# SE423_F28379D.net
KiCad netlist of a schematic drawn in EAGLE
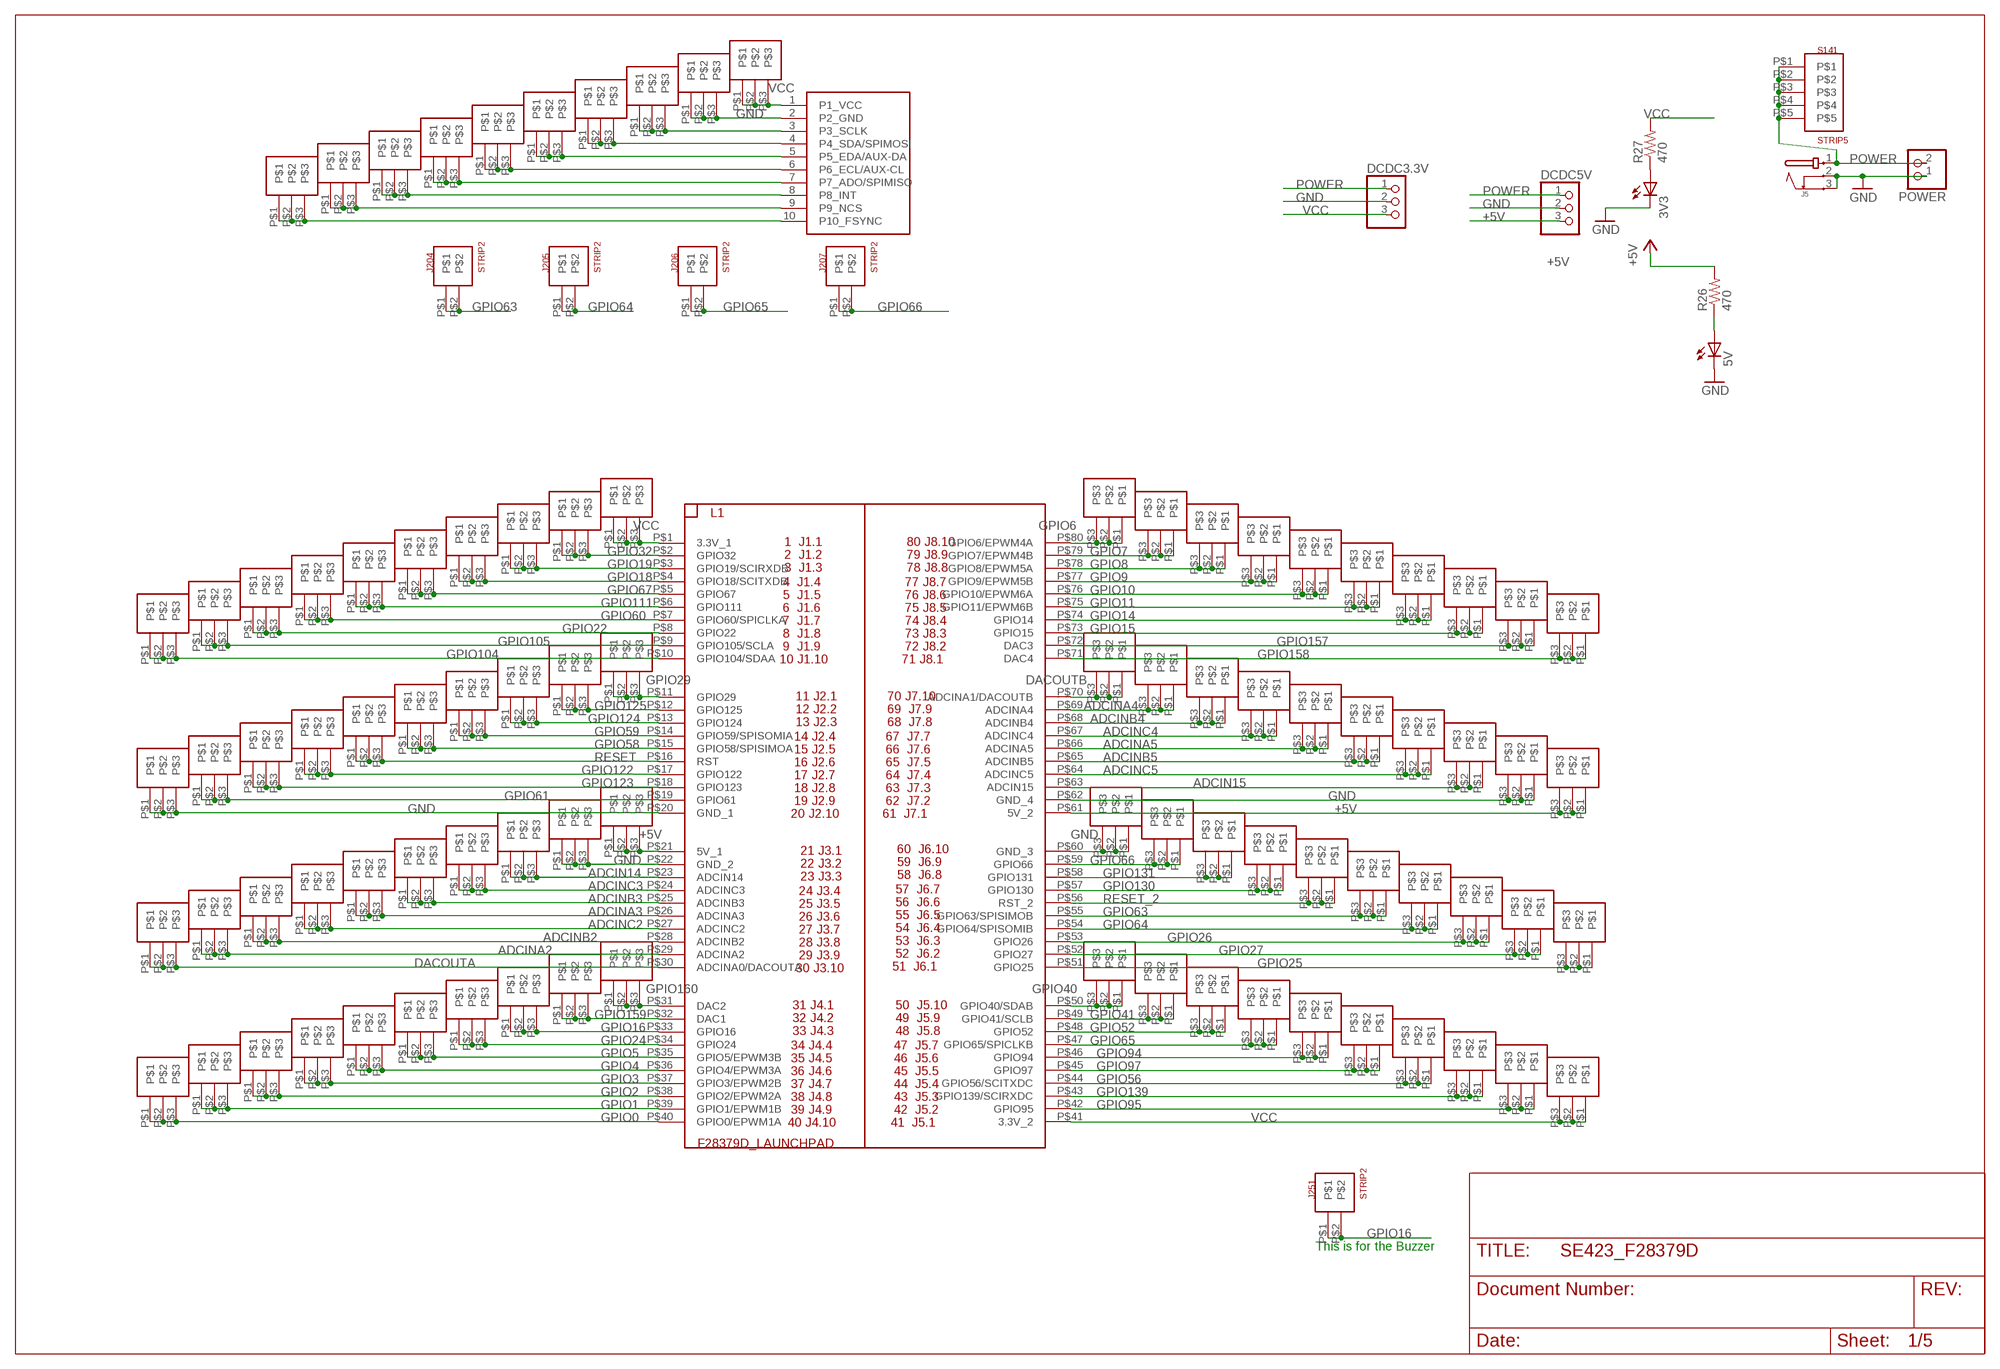
[diagram p0: schematic, sheet 1]
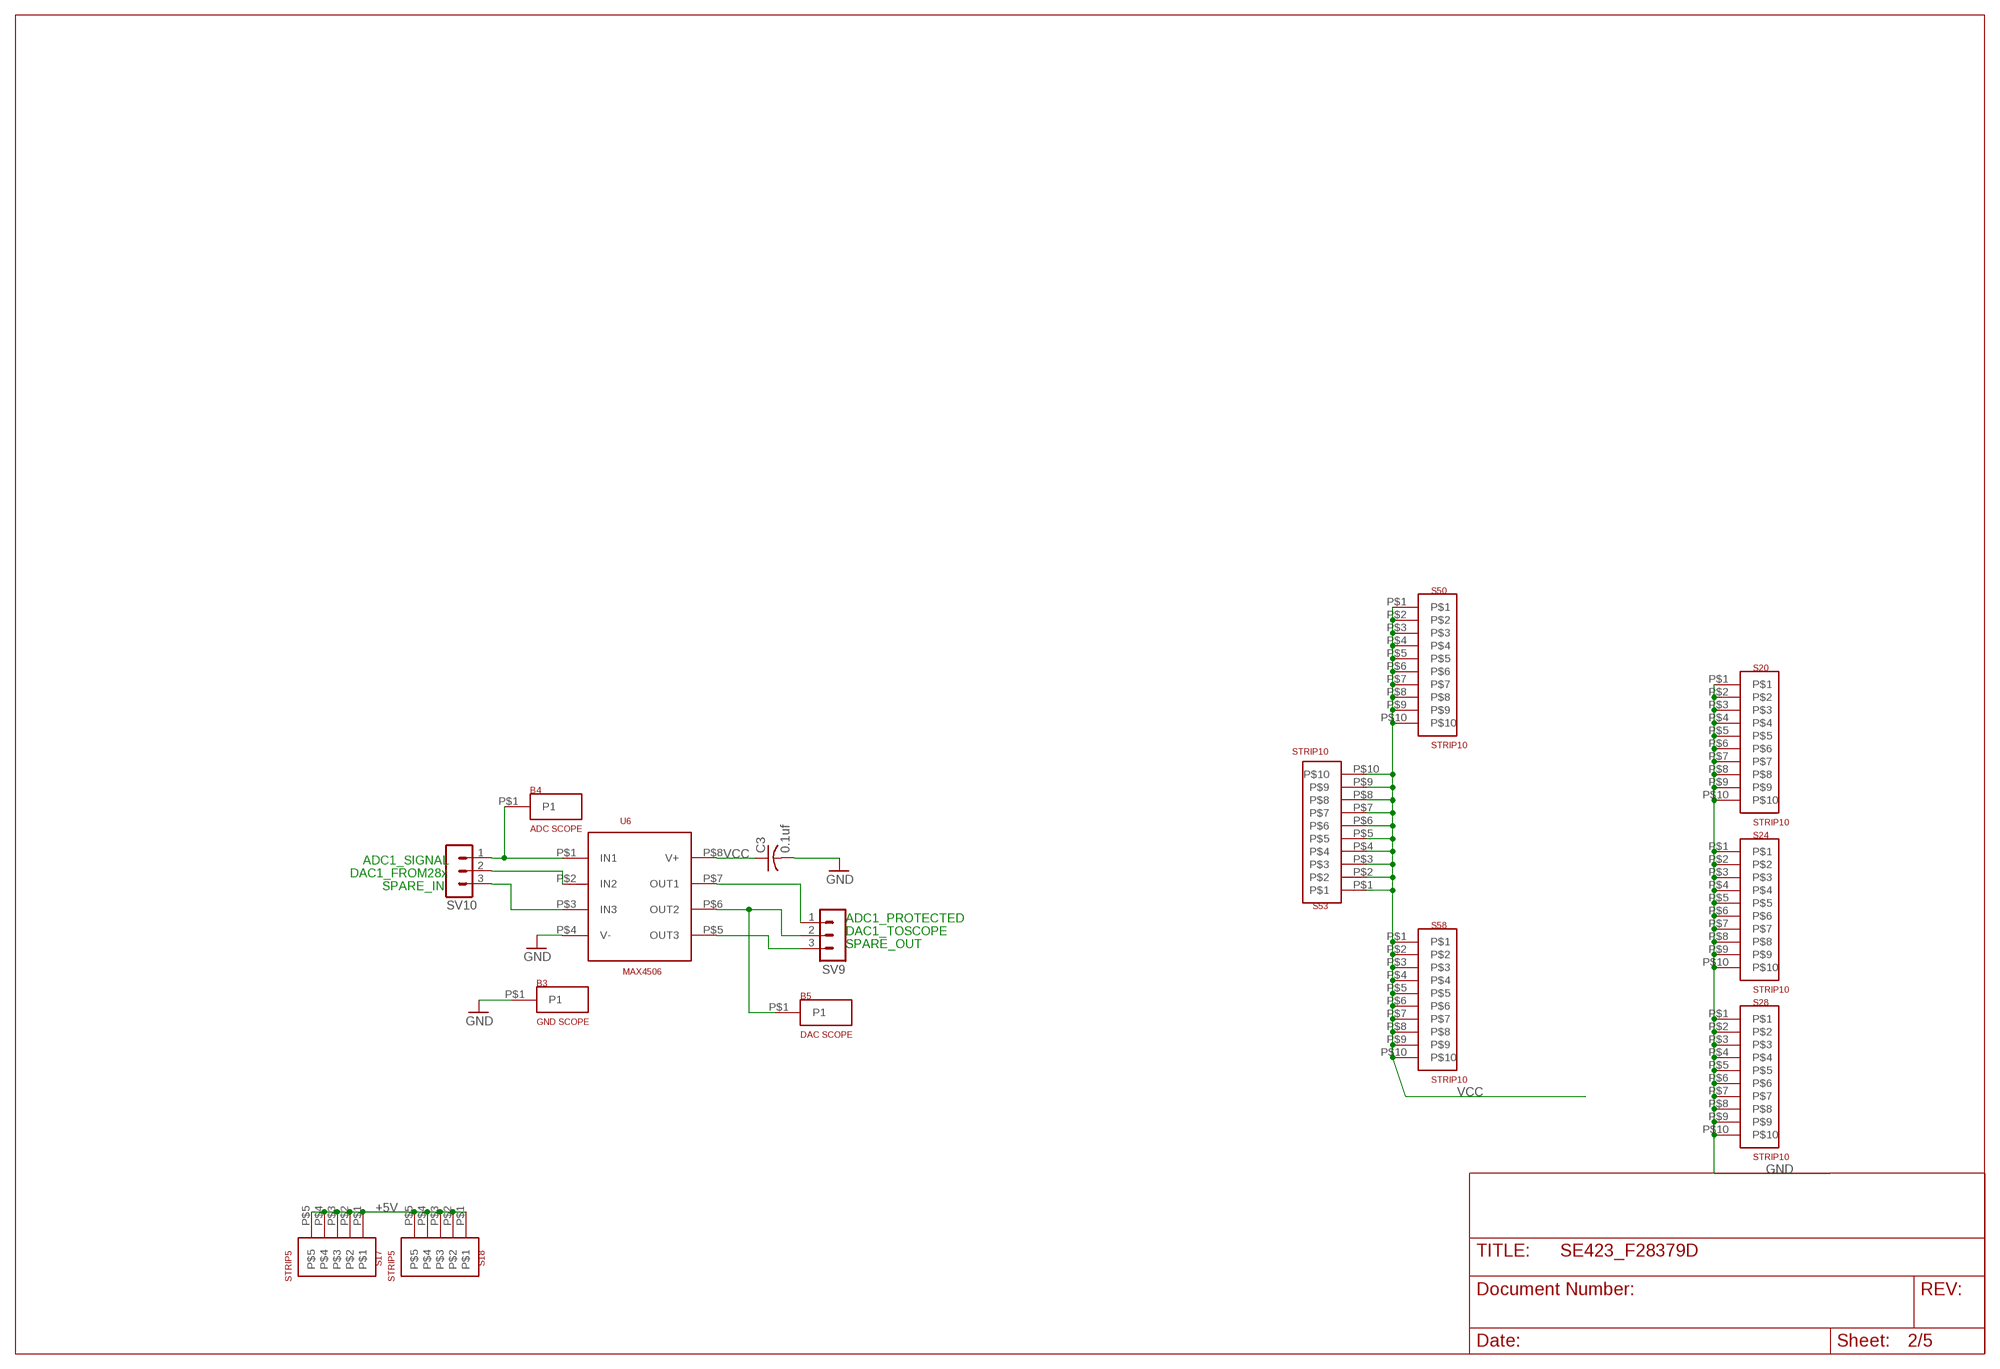
[diagram p1: schematic, sheet 2]
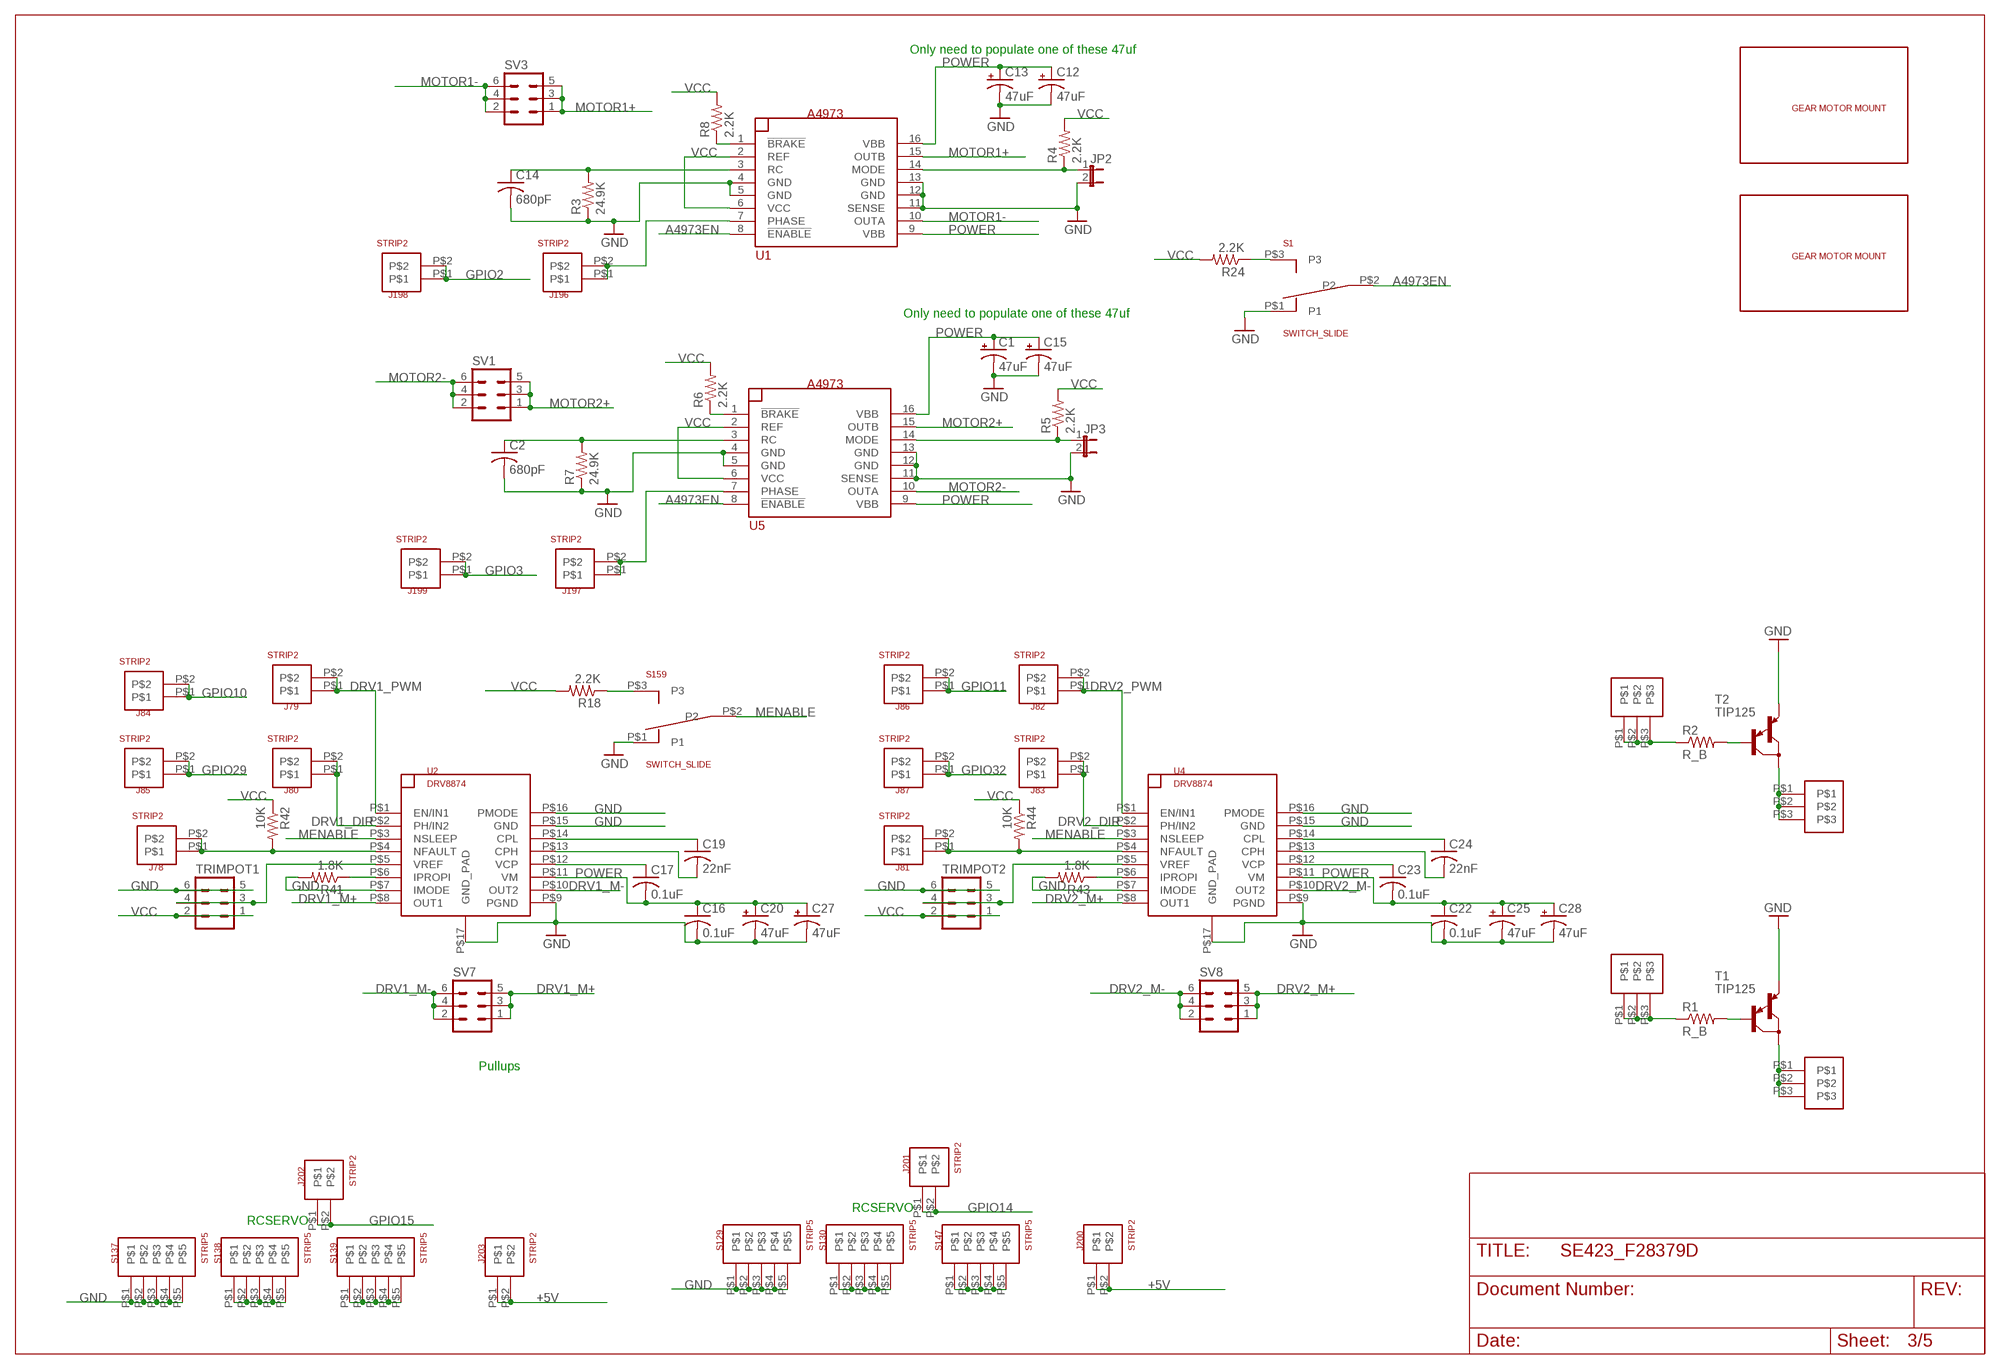
[diagram p2: schematic, sheet 3]
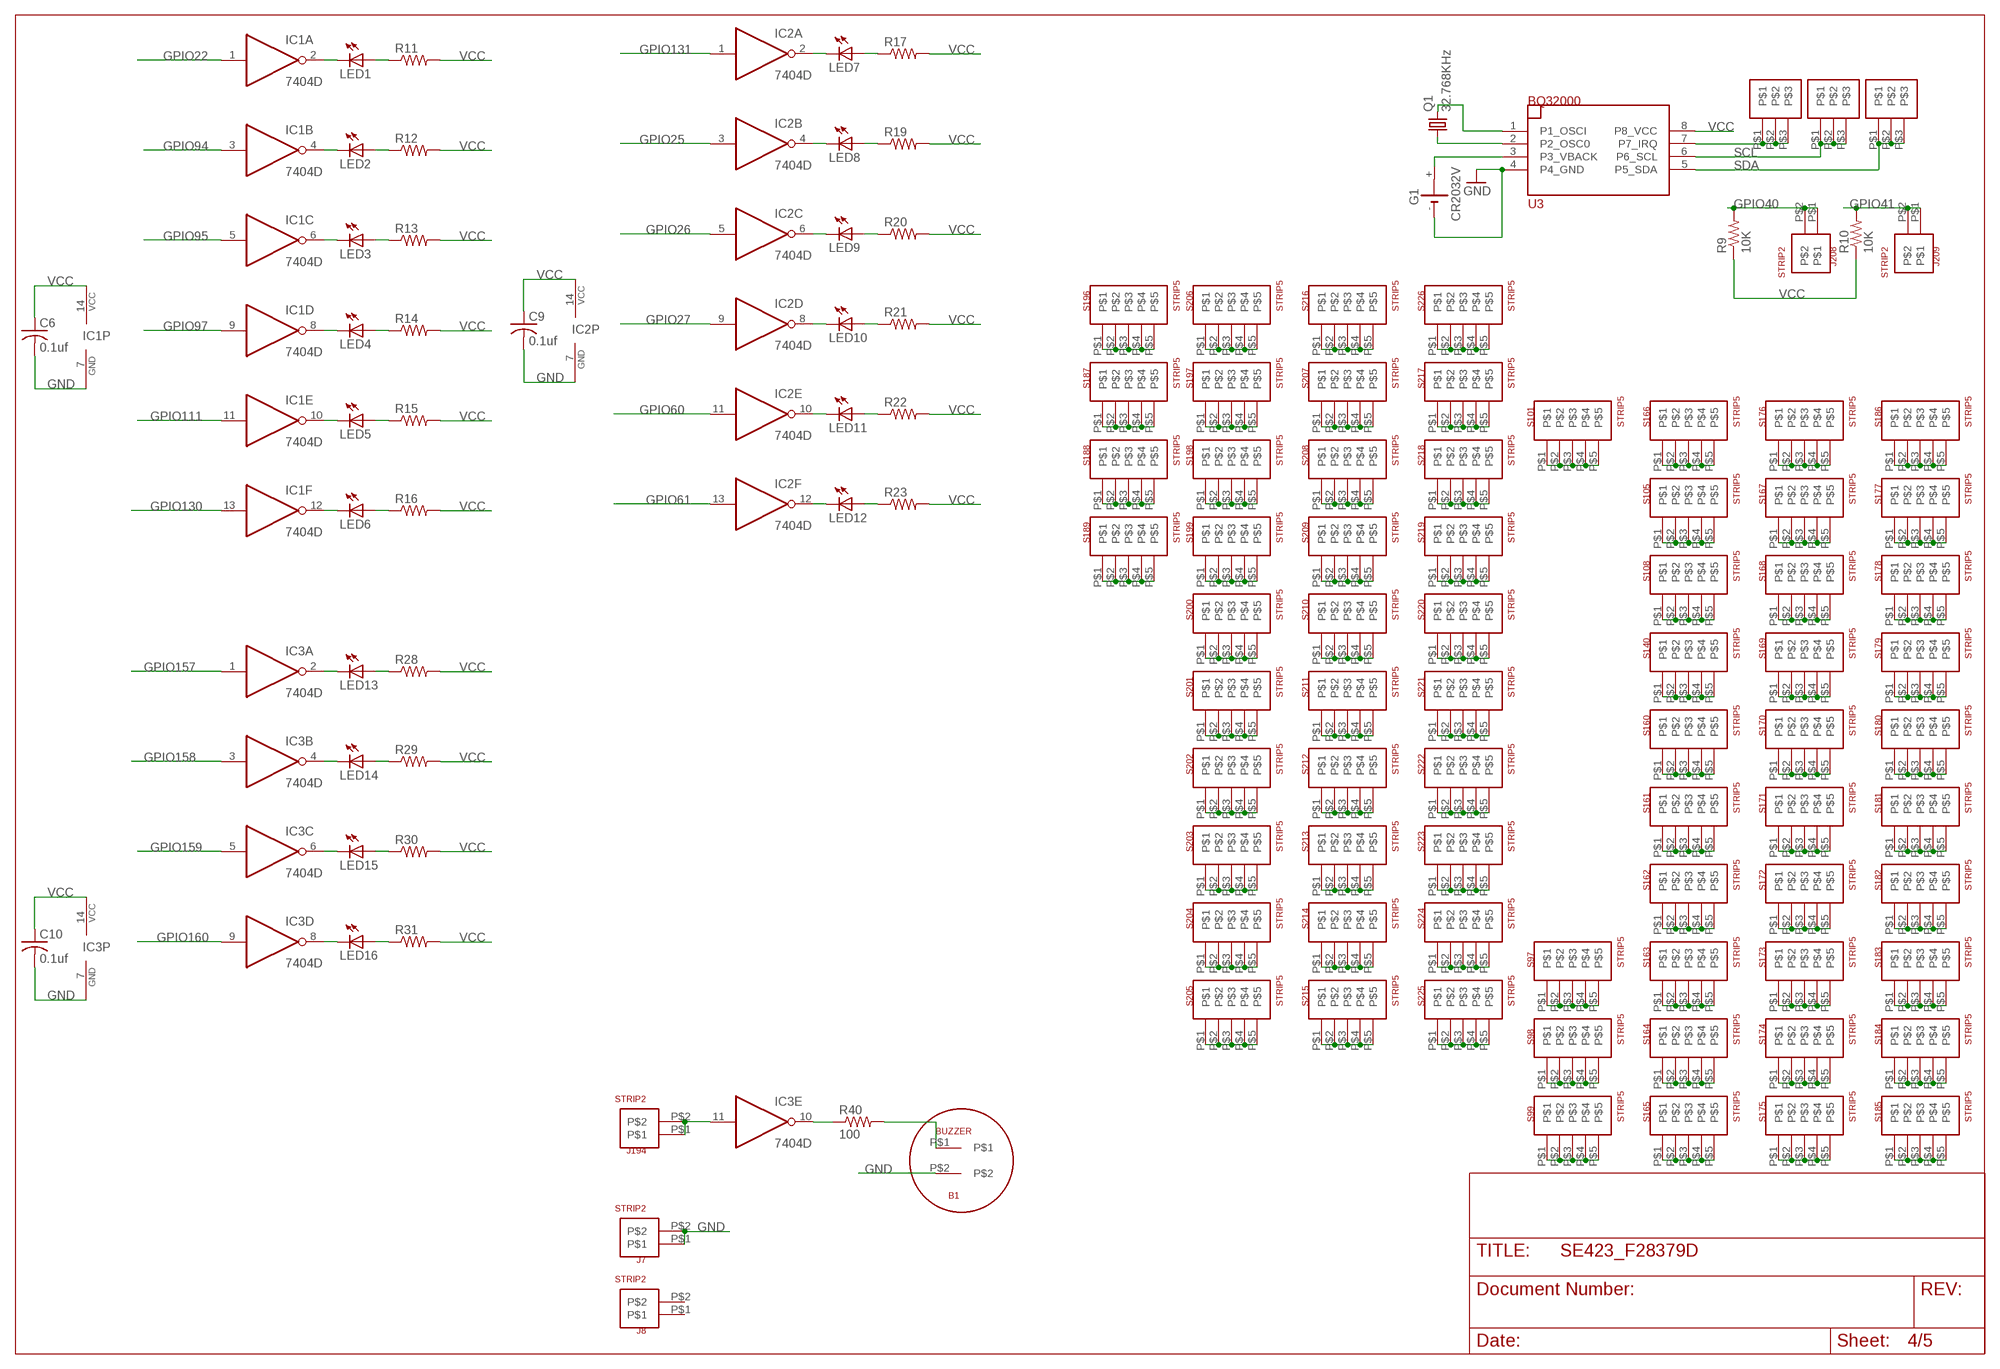
[diagram p3: schematic, sheet 4]
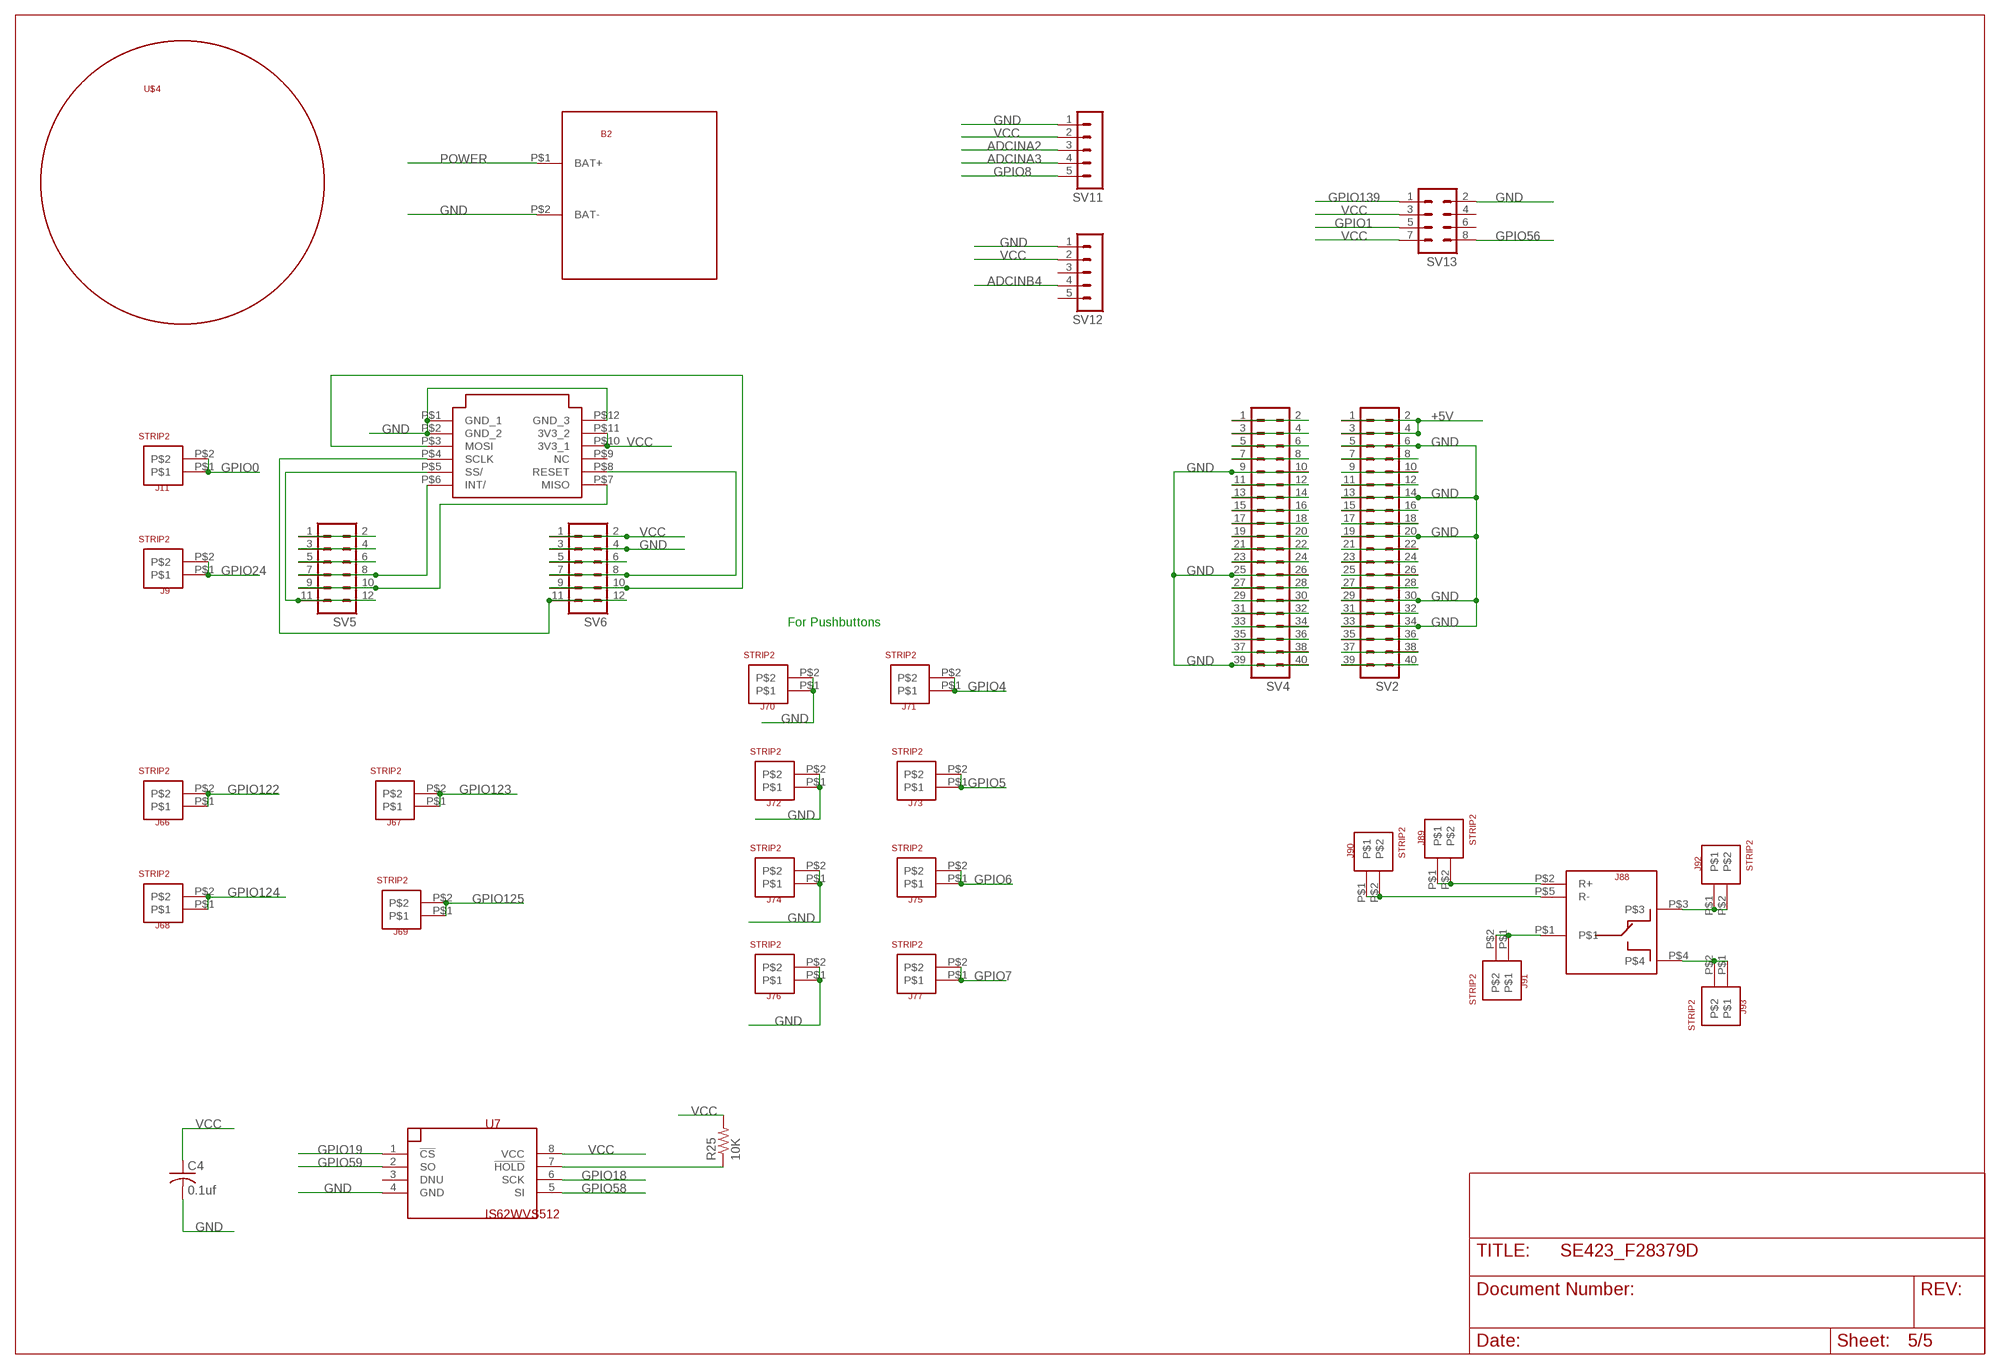
[diagram p4: schematic, sheet 5]

(export (version "E")
  (design (tool "Eeschema 10.0.6"))
  (components
    (comp (ref "B3")
      (value "GND SCOPE")
      (footprint "eagle-import:BANANA_MALE")
      (libsource (lib "eagle-import") (part "BANANA_MALE"))
    )
    (comp (ref "B4")
      (value "ADC SCOPE")
      (footprint "eagle-import:BANANA_MALE")
      (libsource (lib "eagle-import") (part "BANANA_MALE"))
    )
    (comp (ref "B5")
      (value "DAC SCOPE")
      (footprint "eagle-import:BANANA_MALE")
      (libsource (lib "eagle-import") (part "BANANA_MALE"))
    )
    (comp (ref "C3")
      (value "0.1uf")
      (footprint "eagle-import:C1206")
      (libsource (lib "eagle-import") (part "C-USC1206"))
    )
    (comp (ref "S17")
      (value "STRIP5")
      (footprint "eagle-import:STRIP5")
      (libsource (lib "eagle-import") (part "STRIP5"))
    )
    (comp (ref "S18")
      (value "STRIP5")
      (footprint "eagle-import:STRIP5")
      (libsource (lib "eagle-import") (part "STRIP5"))
    )
    (comp (ref "S20")
      (value "STRIP10")
      (footprint "eagle-import:STRIP10")
      (libsource (lib "eagle-import") (part "STRIP10"))
    )
    (comp (ref "S24")
      (value "STRIP10")
      (footprint "eagle-import:STRIP10")
      (libsource (lib "eagle-import") (part "STRIP10"))
    )
    (comp (ref "S28")
      (value "STRIP10")
      (footprint "eagle-import:STRIP10")
      (libsource (lib "eagle-import") (part "STRIP10"))
    )
    (comp (ref "S50")
      (value "STRIP10")
      (footprint "eagle-import:STRIP10")
      (libsource (lib "eagle-import") (part "STRIP10"))
    )
    (comp (ref "S53")
      (value "STRIP10")
      (footprint "eagle-import:STRIP10")
      (libsource (lib "eagle-import") (part "STRIP10"))
    )
    (comp (ref "S58")
      (value "STRIP10")
      (footprint "eagle-import:STRIP10")
      (libsource (lib "eagle-import") (part "STRIP10"))
    )
    (comp (ref "SV9")
      (value "MA03-1")
      (footprint "eagle-import:MA03-1")
      (libsource (lib "eagle-import") (part "MA03-1"))
    )
    (comp (ref "SV10")
      (value "MA03-1")
      (footprint "eagle-import:MA03-1")
      (libsource (lib "eagle-import") (part "MA03-1"))
    )
    (comp (ref "U6")
      (value "MAX4506")
      (footprint "eagle-import:SOIC-8")
      (libsource (lib "eagle-import") (part "MAX4506-SOIC8"))
    )
    (comp (ref "B1")
      (value "BUZZER")
      (footprint "eagle-import:BUZZER")
      (libsource (lib "eagle-import") (part "BUZZER"))
    )
    (comp (ref "C6")
      (value "0.1uf")
      (footprint "eagle-import:C1206")
      (libsource (lib "eagle-import") (part "C-USC1206"))
    )
    (comp (ref "C9")
      (value "0.1uf")
      (footprint "eagle-import:C1206")
      (libsource (lib "eagle-import") (part "C-USC1206"))
    )
    (comp (ref "C10")
      (value "0.1uf")
      (footprint "eagle-import:C1206")
      (libsource (lib "eagle-import") (part "C-USC1206"))
    )
    (comp (ref "G1")
      (value "CR2032V")
      (footprint "eagle-import:CR2032V")
      (libsource (lib "eagle-import") (part "CR2032V"))
    )
    (comp (ref "IC1")
      (value "7404D")
      (footprint "eagle-import:SO14")
      (libsource (lib "eagle-import") (part "7404D"))
    )
    (comp (ref "IC2")
      (value "7404D")
      (footprint "eagle-import:SO14")
      (libsource (lib "eagle-import") (part "7404D"))
    )
    (comp (ref "IC3")
      (value "7404D")
      (footprint "eagle-import:SO14")
      (libsource (lib "eagle-import") (part "7404D"))
    )
    (comp (ref "J1")
      (value "STRIP3")
      (footprint "eagle-import:STRIP3")
      (libsource (lib "eagle-import") (part "STRIP3"))
    )
    (comp (ref "J2")
      (value "STRIP3")
      (footprint "eagle-import:STRIP3")
      (libsource (lib "eagle-import") (part "STRIP3"))
    )
    (comp (ref "J3")
      (value "STRIP3")
      (footprint "eagle-import:STRIP3")
      (libsource (lib "eagle-import") (part "STRIP3"))
    )
    (comp (ref "J7")
      (value "STRIP2")
      (footprint "eagle-import:STRIP2")
      (libsource (lib "eagle-import") (part "STRIP2"))
    )
    (comp (ref "J8")
      (value "STRIP2")
      (footprint "eagle-import:STRIP2")
      (libsource (lib "eagle-import") (part "STRIP2"))
    )
    (comp (ref "J194")
      (value "STRIP2")
      (footprint "eagle-import:STRIP2")
      (libsource (lib "eagle-import") (part "STRIP2"))
    )
    (comp (ref "J208")
      (value "STRIP2")
      (footprint "eagle-import:STRIP2")
      (libsource (lib "eagle-import") (part "STRIP2"))
    )
    (comp (ref "J209")
      (value "STRIP2")
      (footprint "eagle-import:STRIP2")
      (libsource (lib "eagle-import") (part "STRIP2"))
    )
    (comp (ref "LED1")
      (value "LEDCHIPLED_1206")
      (footprint "eagle-import:CHIPLED_1206")
      (libsource (lib "eagle-import") (part "LEDCHIPLED_1206"))
    )
    (comp (ref "LED2")
      (value "LEDCHIPLED_1206")
      (footprint "eagle-import:CHIPLED_1206")
      (libsource (lib "eagle-import") (part "LEDCHIPLED_1206"))
    )
    (comp (ref "LED3")
      (value "LEDCHIPLED_1206")
      (footprint "eagle-import:CHIPLED_1206")
      (libsource (lib "eagle-import") (part "LEDCHIPLED_1206"))
    )
    (comp (ref "LED4")
      (value "LEDCHIPLED_1206")
      (footprint "eagle-import:CHIPLED_1206")
      (libsource (lib "eagle-import") (part "LEDCHIPLED_1206"))
    )
    (comp (ref "LED5")
      (value "LEDCHIPLED_1206")
      (footprint "eagle-import:CHIPLED_1206")
      (libsource (lib "eagle-import") (part "LEDCHIPLED_1206"))
    )
    (comp (ref "LED6")
      (value "LEDCHIPLED_1206")
      (footprint "eagle-import:CHIPLED_1206")
      (libsource (lib "eagle-import") (part "LEDCHIPLED_1206"))
    )
    (comp (ref "LED7")
      (value "LEDCHIPLED_1206")
      (footprint "eagle-import:CHIPLED_1206")
      (libsource (lib "eagle-import") (part "LEDCHIPLED_1206"))
    )
    (comp (ref "LED8")
      (value "LEDCHIPLED_1206")
      (footprint "eagle-import:CHIPLED_1206")
      (libsource (lib "eagle-import") (part "LEDCHIPLED_1206"))
    )
    (comp (ref "LED9")
      (value "LEDCHIPLED_1206")
      (footprint "eagle-import:CHIPLED_1206")
      (libsource (lib "eagle-import") (part "LEDCHIPLED_1206"))
    )
    (comp (ref "LED10")
      (value "LEDCHIPLED_1206")
      (footprint "eagle-import:CHIPLED_1206")
      (libsource (lib "eagle-import") (part "LEDCHIPLED_1206"))
    )
    (comp (ref "LED11")
      (value "LEDCHIPLED_1206")
      (footprint "eagle-import:CHIPLED_1206")
      (libsource (lib "eagle-import") (part "LEDCHIPLED_1206"))
    )
    (comp (ref "LED12")
      (value "LEDCHIPLED_1206")
      (footprint "eagle-import:CHIPLED_1206")
      (libsource (lib "eagle-import") (part "LEDCHIPLED_1206"))
    )
    (comp (ref "LED13")
      (value "LEDCHIPLED_1206")
      (footprint "eagle-import:CHIPLED_1206")
      (libsource (lib "eagle-import") (part "LEDCHIPLED_1206"))
    )
    (comp (ref "LED14")
      (value "LEDCHIPLED_1206")
      (footprint "eagle-import:CHIPLED_1206")
      (libsource (lib "eagle-import") (part "LEDCHIPLED_1206"))
    )
    (comp (ref "LED15")
      (value "LEDCHIPLED_1206")
      (footprint "eagle-import:CHIPLED_1206")
      (libsource (lib "eagle-import") (part "LEDCHIPLED_1206"))
    )
    (comp (ref "LED16")
      (value "LEDCHIPLED_1206")
      (footprint "eagle-import:CHIPLED_1206")
      (libsource (lib "eagle-import") (part "LEDCHIPLED_1206"))
    )
    (comp (ref "Q1")
      (value "32.768KHz")
      (footprint "eagle-import:TC26H")
      (libsource (lib "eagle-import") (part "CRYTALTC26H"))
    )
    (comp (ref "R9")
      (value "10K")
      (footprint "eagle-import:R1206")
      (libsource (lib "eagle-import") (part "R-US_R1206"))
    )
    (comp (ref "R10")
      (value "10K")
      (footprint "eagle-import:R1206")
      (libsource (lib "eagle-import") (part "R-US_R1206"))
    )
    (comp (ref "R11")
      (value "R-US_R1206")
      (footprint "eagle-import:R1206")
      (libsource (lib "eagle-import") (part "R-US_R1206"))
    )
    (comp (ref "R12")
      (value "R-US_R1206")
      (footprint "eagle-import:R1206")
      (libsource (lib "eagle-import") (part "R-US_R1206"))
    )
    (comp (ref "R13")
      (value "R-US_R1206")
      (footprint "eagle-import:R1206")
      (libsource (lib "eagle-import") (part "R-US_R1206"))
    )
    (comp (ref "R14")
      (value "R-US_R1206")
      (footprint "eagle-import:R1206")
      (libsource (lib "eagle-import") (part "R-US_R1206"))
    )
    (comp (ref "R15")
      (value "R-US_R1206")
      (footprint "eagle-import:R1206")
      (libsource (lib "eagle-import") (part "R-US_R1206"))
    )
    (comp (ref "R16")
      (value "R-US_R1206")
      (footprint "eagle-import:R1206")
      (libsource (lib "eagle-import") (part "R-US_R1206"))
    )
    (comp (ref "R17")
      (value "R-US_R1206")
      (footprint "eagle-import:R1206")
      (libsource (lib "eagle-import") (part "R-US_R1206"))
    )
    (comp (ref "R19")
      (value "R-US_R1206")
      (footprint "eagle-import:R1206")
      (libsource (lib "eagle-import") (part "R-US_R1206"))
    )
    (comp (ref "R20")
      (value "R-US_R1206")
      (footprint "eagle-import:R1206")
      (libsource (lib "eagle-import") (part "R-US_R1206"))
    )
    (comp (ref "R21")
      (value "R-US_R1206")
      (footprint "eagle-import:R1206")
      (libsource (lib "eagle-import") (part "R-US_R1206"))
    )
    (comp (ref "R22")
      (value "R-US_R1206")
      (footprint "eagle-import:R1206")
      (libsource (lib "eagle-import") (part "R-US_R1206"))
    )
    (comp (ref "R23")
      (value "R-US_R1206")
      (footprint "eagle-import:R1206")
      (libsource (lib "eagle-import") (part "R-US_R1206"))
    )
    (comp (ref "R28")
      (value "R-US_R1206")
      (footprint "eagle-import:R1206")
      (libsource (lib "eagle-import") (part "R-US_R1206"))
    )
    (comp (ref "R29")
      (value "R-US_R1206")
      (footprint "eagle-import:R1206")
      (libsource (lib "eagle-import") (part "R-US_R1206"))
    )
    (comp (ref "R30")
      (value "R-US_R1206")
      (footprint "eagle-import:R1206")
      (libsource (lib "eagle-import") (part "R-US_R1206"))
    )
    (comp (ref "R31")
      (value "R-US_R1206")
      (footprint "eagle-import:R1206")
      (libsource (lib "eagle-import") (part "R-US_R1206"))
    )
    (comp (ref "R40")
      (value "100")
      (footprint "eagle-import:R1206")
      (libsource (lib "eagle-import") (part "R-US_R1206"))
    )
    (comp (ref "S97")
      (value "STRIP5")
      (footprint "eagle-import:STRIP5")
      (libsource (lib "eagle-import") (part "STRIP5"))
    )
    (comp (ref "S98")
      (value "STRIP5")
      (footprint "eagle-import:STRIP5")
      (libsource (lib "eagle-import") (part "STRIP5"))
    )
    (comp (ref "S99")
      (value "STRIP5")
      (footprint "eagle-import:STRIP5")
      (libsource (lib "eagle-import") (part "STRIP5"))
    )
    (comp (ref "S101")
      (value "STRIP5")
      (footprint "eagle-import:STRIP5")
      (libsource (lib "eagle-import") (part "STRIP5"))
    )
    (comp (ref "S105")
      (value "STRIP5")
      (footprint "eagle-import:STRIP5")
      (libsource (lib "eagle-import") (part "STRIP5"))
    )
    (comp (ref "S108")
      (value "STRIP5")
      (footprint "eagle-import:STRIP5")
      (libsource (lib "eagle-import") (part "STRIP5"))
    )
    (comp (ref "S140")
      (value "STRIP5")
      (footprint "eagle-import:STRIP5")
      (libsource (lib "eagle-import") (part "STRIP5"))
    )
    (comp (ref "S160")
      (value "STRIP5")
      (footprint "eagle-import:STRIP5")
      (libsource (lib "eagle-import") (part "STRIP5"))
    )
    (comp (ref "S161")
      (value "STRIP5")
      (footprint "eagle-import:STRIP5")
      (libsource (lib "eagle-import") (part "STRIP5"))
    )
    (comp (ref "S162")
      (value "STRIP5")
      (footprint "eagle-import:STRIP5")
      (libsource (lib "eagle-import") (part "STRIP5"))
    )
    (comp (ref "S163")
      (value "STRIP5")
      (footprint "eagle-import:STRIP5")
      (libsource (lib "eagle-import") (part "STRIP5"))
    )
    (comp (ref "S164")
      (value "STRIP5")
      (footprint "eagle-import:STRIP5")
      (libsource (lib "eagle-import") (part "STRIP5"))
    )
    (comp (ref "S165")
      (value "STRIP5")
      (footprint "eagle-import:STRIP5")
      (libsource (lib "eagle-import") (part "STRIP5"))
    )
    (comp (ref "S166")
      (value "STRIP5")
      (footprint "eagle-import:STRIP5")
      (libsource (lib "eagle-import") (part "STRIP5"))
    )
    (comp (ref "S167")
      (value "STRIP5")
      (footprint "eagle-import:STRIP5")
      (libsource (lib "eagle-import") (part "STRIP5"))
    )
    (comp (ref "S168")
      (value "STRIP5")
      (footprint "eagle-import:STRIP5")
      (libsource (lib "eagle-import") (part "STRIP5"))
    )
    (comp (ref "S169")
      (value "STRIP5")
      (footprint "eagle-import:STRIP5")
      (libsource (lib "eagle-import") (part "STRIP5"))
    )
    (comp (ref "S170")
      (value "STRIP5")
      (footprint "eagle-import:STRIP5")
      (libsource (lib "eagle-import") (part "STRIP5"))
    )
    (comp (ref "S171")
      (value "STRIP5")
      (footprint "eagle-import:STRIP5")
      (libsource (lib "eagle-import") (part "STRIP5"))
    )
    (comp (ref "S172")
      (value "STRIP5")
      (footprint "eagle-import:STRIP5")
      (libsource (lib "eagle-import") (part "STRIP5"))
    )
    (comp (ref "S173")
      (value "STRIP5")
      (footprint "eagle-import:STRIP5")
      (libsource (lib "eagle-import") (part "STRIP5"))
    )
    (comp (ref "S174")
      (value "STRIP5")
      (footprint "eagle-import:STRIP5")
      (libsource (lib "eagle-import") (part "STRIP5"))
    )
    (comp (ref "S175")
      (value "STRIP5")
      (footprint "eagle-import:STRIP5")
      (libsource (lib "eagle-import") (part "STRIP5"))
    )
    (comp (ref "S176")
      (value "STRIP5")
      (footprint "eagle-import:STRIP5")
      (libsource (lib "eagle-import") (part "STRIP5"))
    )
    (comp (ref "S177")
      (value "STRIP5")
      (footprint "eagle-import:STRIP5")
      (libsource (lib "eagle-import") (part "STRIP5"))
    )
    (comp (ref "S178")
      (value "STRIP5")
      (footprint "eagle-import:STRIP5")
      (libsource (lib "eagle-import") (part "STRIP5"))
    )
    (comp (ref "S179")
      (value "STRIP5")
      (footprint "eagle-import:STRIP5")
      (libsource (lib "eagle-import") (part "STRIP5"))
    )
    (comp (ref "S180")
      (value "STRIP5")
      (footprint "eagle-import:STRIP5")
      (libsource (lib "eagle-import") (part "STRIP5"))
    )
    (comp (ref "S181")
      (value "STRIP5")
      (footprint "eagle-import:STRIP5")
      (libsource (lib "eagle-import") (part "STRIP5"))
    )
    (comp (ref "S182")
      (value "STRIP5")
      (footprint "eagle-import:STRIP5")
      (libsource (lib "eagle-import") (part "STRIP5"))
    )
    (comp (ref "S183")
      (value "STRIP5")
      (footprint "eagle-import:STRIP5")
      (libsource (lib "eagle-import") (part "STRIP5"))
    )
    (comp (ref "S184")
      (value "STRIP5")
      (footprint "eagle-import:STRIP5")
      (libsource (lib "eagle-import") (part "STRIP5"))
    )
    (comp (ref "S185")
      (value "STRIP5")
      (footprint "eagle-import:STRIP5")
      (libsource (lib "eagle-import") (part "STRIP5"))
    )
    (comp (ref "S186")
      (value "STRIP5")
      (footprint "eagle-import:STRIP5")
      (libsource (lib "eagle-import") (part "STRIP5"))
    )
    (comp (ref "S187")
      (value "STRIP5")
      (footprint "eagle-import:STRIP5")
      (libsource (lib "eagle-import") (part "STRIP5"))
    )
    (comp (ref "S188")
      (value "STRIP5")
      (footprint "eagle-import:STRIP5")
      (libsource (lib "eagle-import") (part "STRIP5"))
    )
    (comp (ref "S189")
      (value "STRIP5")
      (footprint "eagle-import:STRIP5")
      (libsource (lib "eagle-import") (part "STRIP5"))
    )
    (comp (ref "S196")
      (value "STRIP5")
      (footprint "eagle-import:STRIP5")
      (libsource (lib "eagle-import") (part "STRIP5"))
    )
    (comp (ref "S197")
      (value "STRIP5")
      (footprint "eagle-import:STRIP5")
      (libsource (lib "eagle-import") (part "STRIP5"))
    )
    (comp (ref "S198")
      (value "STRIP5")
      (footprint "eagle-import:STRIP5")
      (libsource (lib "eagle-import") (part "STRIP5"))
    )
    (comp (ref "S199")
      (value "STRIP5")
      (footprint "eagle-import:STRIP5")
      (libsource (lib "eagle-import") (part "STRIP5"))
    )
    (comp (ref "S200")
      (value "STRIP5")
      (footprint "eagle-import:STRIP5")
      (libsource (lib "eagle-import") (part "STRIP5"))
    )
    (comp (ref "S201")
      (value "STRIP5")
      (footprint "eagle-import:STRIP5")
      (libsource (lib "eagle-import") (part "STRIP5"))
    )
    (comp (ref "S202")
      (value "STRIP5")
      (footprint "eagle-import:STRIP5")
      (libsource (lib "eagle-import") (part "STRIP5"))
    )
    (comp (ref "S203")
      (value "STRIP5")
      (footprint "eagle-import:STRIP5")
      (libsource (lib "eagle-import") (part "STRIP5"))
    )
    (comp (ref "S204")
      (value "STRIP5")
      (footprint "eagle-import:STRIP5")
      (libsource (lib "eagle-import") (part "STRIP5"))
    )
    (comp (ref "S205")
      (value "STRIP5")
      (footprint "eagle-import:STRIP5")
      (libsource (lib "eagle-import") (part "STRIP5"))
    )
    (comp (ref "S206")
      (value "STRIP5")
      (footprint "eagle-import:STRIP5")
      (libsource (lib "eagle-import") (part "STRIP5"))
    )
    (comp (ref "S207")
      (value "STRIP5")
      (footprint "eagle-import:STRIP5")
      (libsource (lib "eagle-import") (part "STRIP5"))
    )
    (comp (ref "S208")
      (value "STRIP5")
      (footprint "eagle-import:STRIP5")
      (libsource (lib "eagle-import") (part "STRIP5"))
    )
    (comp (ref "S209")
      (value "STRIP5")
      (footprint "eagle-import:STRIP5")
      (libsource (lib "eagle-import") (part "STRIP5"))
    )
    (comp (ref "S210")
      (value "STRIP5")
      (footprint "eagle-import:STRIP5")
      (libsource (lib "eagle-import") (part "STRIP5"))
    )
    (comp (ref "S211")
      (value "STRIP5")
      (footprint "eagle-import:STRIP5")
      (libsource (lib "eagle-import") (part "STRIP5"))
    )
    (comp (ref "S212")
      (value "STRIP5")
      (footprint "eagle-import:STRIP5")
      (libsource (lib "eagle-import") (part "STRIP5"))
    )
    (comp (ref "S213")
      (value "STRIP5")
      (footprint "eagle-import:STRIP5")
      (libsource (lib "eagle-import") (part "STRIP5"))
    )
    (comp (ref "S214")
      (value "STRIP5")
      (footprint "eagle-import:STRIP5")
      (libsource (lib "eagle-import") (part "STRIP5"))
    )
    (comp (ref "S215")
      (value "STRIP5")
      (footprint "eagle-import:STRIP5")
      (libsource (lib "eagle-import") (part "STRIP5"))
    )
    (comp (ref "S216")
      (value "STRIP5")
      (footprint "eagle-import:STRIP5")
      (libsource (lib "eagle-import") (part "STRIP5"))
    )
    (comp (ref "S217")
      (value "STRIP5")
      (footprint "eagle-import:STRIP5")
      (libsource (lib "eagle-import") (part "STRIP5"))
    )
    (comp (ref "S218")
      (value "STRIP5")
      (footprint "eagle-import:STRIP5")
      (libsource (lib "eagle-import") (part "STRIP5"))
    )
    (comp (ref "S219")
      (value "STRIP5")
      (footprint "eagle-import:STRIP5")
      (libsource (lib "eagle-import") (part "STRIP5"))
    )
    (comp (ref "S220")
      (value "STRIP5")
      (footprint "eagle-import:STRIP5")
      (libsource (lib "eagle-import") (part "STRIP5"))
    )
    (comp (ref "S221")
      (value "STRIP5")
      (footprint "eagle-import:STRIP5")
      (libsource (lib "eagle-import") (part "STRIP5"))
    )
    (comp (ref "S222")
      (value "STRIP5")
      (footprint "eagle-import:STRIP5")
      (libsource (lib "eagle-import") (part "STRIP5"))
    )
    (comp (ref "S223")
      (value "STRIP5")
      (footprint "eagle-import:STRIP5")
      (libsource (lib "eagle-import") (part "STRIP5"))
    )
    (comp (ref "S224")
      (value "STRIP5")
      (footprint "eagle-import:STRIP5")
      (libsource (lib "eagle-import") (part "STRIP5"))
    )
    (comp (ref "S225")
      (value "STRIP5")
      (footprint "eagle-import:STRIP5")
      (libsource (lib "eagle-import") (part "STRIP5"))
    )
    (comp (ref "S226")
      (value "STRIP5")
      (footprint "eagle-import:STRIP5")
      (libsource (lib "eagle-import") (part "STRIP5"))
    )
    (comp (ref "U3")
      (value "BQ32000")
      (footprint "eagle-import:SO08")
      (libsource (lib "eagle-import") (part "BQ32000"))
    )
    (comp (ref "B2")
      (value "BATTERY_4AA_HOLDER")
      (footprint "eagle-import:BATTERY_4AA_HOLDER")
      (libsource (lib "eagle-import") (part "BATTERY_4AA_HOLDER"))
    )
    (comp (ref "C4")
      (value "0.1uf")
      (footprint "eagle-import:C1206")
      (libsource (lib "eagle-import") (part "C-USC1206"))
    )
    (comp (ref "ETH1")
      (value "USR_ES1_W5500")
      (footprint "eagle-import:USR_ES1_W5500")
      (libsource (lib "eagle-import") (part "USR_ES1_W5500"))
    )
    (comp (ref "J9")
      (value "STRIP2")
      (footprint "eagle-import:STRIP2")
      (libsource (lib "eagle-import") (part "STRIP2"))
    )
    (comp (ref "J11")
      (value "STRIP2")
      (footprint "eagle-import:STRIP2")
      (libsource (lib "eagle-import") (part "STRIP2"))
    )
    (comp (ref "J66")
      (value "STRIP2")
      (footprint "eagle-import:STRIP2")
      (libsource (lib "eagle-import") (part "STRIP2"))
    )
    (comp (ref "J67")
      (value "STRIP2")
      (footprint "eagle-import:STRIP2")
      (libsource (lib "eagle-import") (part "STRIP2"))
    )
    (comp (ref "J68")
      (value "STRIP2")
      (footprint "eagle-import:STRIP2")
      (libsource (lib "eagle-import") (part "STRIP2"))
    )
    (comp (ref "J69")
      (value "STRIP2")
      (footprint "eagle-import:STRIP2")
      (libsource (lib "eagle-import") (part "STRIP2"))
    )
    (comp (ref "J70")
      (value "STRIP2")
      (footprint "eagle-import:STRIP2")
      (libsource (lib "eagle-import") (part "STRIP2"))
    )
    (comp (ref "J71")
      (value "STRIP2")
      (footprint "eagle-import:STRIP2")
      (libsource (lib "eagle-import") (part "STRIP2"))
    )
    (comp (ref "J72")
      (value "STRIP2")
      (footprint "eagle-import:STRIP2")
      (libsource (lib "eagle-import") (part "STRIP2"))
    )
    (comp (ref "J73")
      (value "STRIP2")
      (footprint "eagle-import:STRIP2")
      (libsource (lib "eagle-import") (part "STRIP2"))
    )
    (comp (ref "J74")
      (value "STRIP2")
      (footprint "eagle-import:STRIP2")
      (libsource (lib "eagle-import") (part "STRIP2"))
    )
    (comp (ref "J75")
      (value "STRIP2")
      (footprint "eagle-import:STRIP2")
      (libsource (lib "eagle-import") (part "STRIP2"))
    )
    (comp (ref "J76")
      (value "STRIP2")
      (footprint "eagle-import:STRIP2")
      (libsource (lib "eagle-import") (part "STRIP2"))
    )
    (comp (ref "J77")
      (value "STRIP2")
      (footprint "eagle-import:STRIP2")
      (libsource (lib "eagle-import") (part "STRIP2"))
    )
    (comp (ref "J88")
      (value "RELAY_JQC-3F_5V")
      (footprint "eagle-import:RELAY_JQC-3F_5V")
      (libsource (lib "eagle-import") (part "RELAY_JQC-3F_5V"))
    )
    (comp (ref "J89")
      (value "STRIP2")
      (footprint "eagle-import:STRIP2")
      (libsource (lib "eagle-import") (part "STRIP2"))
    )
    (comp (ref "J90")
      (value "STRIP2")
      (footprint "eagle-import:STRIP2")
      (libsource (lib "eagle-import") (part "STRIP2"))
    )
    (comp (ref "J91")
      (value "STRIP2")
      (footprint "eagle-import:STRIP2")
      (libsource (lib "eagle-import") (part "STRIP2"))
    )
    (comp (ref "J92")
      (value "STRIP2")
      (footprint "eagle-import:STRIP2")
      (libsource (lib "eagle-import") (part "STRIP2"))
    )
    (comp (ref "J93")
      (value "STRIP2")
      (footprint "eagle-import:STRIP2")
      (libsource (lib "eagle-import") (part "STRIP2"))
    )
    (comp (ref "R25")
      (value "10K")
      (footprint "eagle-import:M1206")
      (libsource (lib "eagle-import") (part "R-US_M1206"))
    )
    (comp (ref "SV2")
      (value "MA20-2")
      (footprint "eagle-import:MA20-2")
      (libsource (lib "eagle-import") (part "MA20-2"))
    )
    (comp (ref "SV4")
      (value "MA20-2")
      (footprint "eagle-import:MA20-2")
      (libsource (lib "eagle-import") (part "MA20-2"))
    )
    (comp (ref "SV5")
      (value "MA06-2")
      (footprint "eagle-import:MA06-2")
      (libsource (lib "eagle-import") (part "MA06-2"))
    )
    (comp (ref "SV6")
      (value "MA06-2")
      (footprint "eagle-import:MA06-2")
      (libsource (lib "eagle-import") (part "MA06-2"))
    )
    (comp (ref "SV11")
      (value "MA05-1")
      (footprint "eagle-import:MA05-1")
      (libsource (lib "eagle-import") (part "MA05-1"))
    )
    (comp (ref "SV12")
      (value "MA05-1")
      (footprint "eagle-import:MA05-1")
      (libsource (lib "eagle-import") (part "MA05-1"))
    )
    (comp (ref "SV13")
      (value "MA04-2")
      (footprint "eagle-import:MA04-2")
      (libsource (lib "eagle-import") (part "MA04-2"))
    )
    (comp (ref "U$4")
      (value "CASTERWHEEL")
      (footprint "eagle-import:CASTERWHEEL")
      (libsource (lib "eagle-import") (part "CASTERWHEEL"))
    )
    (comp (ref "U7")
      (value "IS62WVS512")
      (footprint "eagle-import:SO08")
      (libsource (lib "eagle-import") (part "IS62WVS512"))
    )
    (comp (ref "C1")
      (value "47uF")
      (footprint "eagle-import:153CLV-0810")
      (libsource (lib "eagle-import") (part "CPOL-US153CLV-0810"))
    )
    (comp (ref "C2")
      (value "680pF")
      (footprint "eagle-import:C1206")
      (libsource (lib "eagle-import") (part "C-USC1206"))
    )
    (comp (ref "C12")
      (value "47uF")
      (footprint "eagle-import:153CLV-0810")
      (libsource (lib "eagle-import") (part "CPOL-US153CLV-0810"))
    )
    (comp (ref "C13")
      (value "47uF")
      (footprint "eagle-import:153CLV-0810")
      (libsource (lib "eagle-import") (part "CPOL-US153CLV-0810"))
    )
    (comp (ref "C14")
      (value "680pF")
      (footprint "eagle-import:C1206")
      (libsource (lib "eagle-import") (part "C-USC1206"))
    )
    (comp (ref "C15")
      (value "47uF")
      (footprint "eagle-import:153CLV-0810")
      (libsource (lib "eagle-import") (part "CPOL-US153CLV-0810"))
    )
    (comp (ref "C16")
      (value "0.1uF")
      (footprint "eagle-import:C1206")
      (libsource (lib "eagle-import") (part "C-USC1206"))
    )
    (comp (ref "C17")
      (value "0.1uF")
      (footprint "eagle-import:C1206")
      (libsource (lib "eagle-import") (part "C-USC1206"))
    )
    (comp (ref "C19")
      (value "22nF")
      (footprint "eagle-import:C1206")
      (libsource (lib "eagle-import") (part "C-USC1206"))
    )
    (comp (ref "C20")
      (value "47uF")
      (footprint "eagle-import:153CLV-0810")
      (libsource (lib "eagle-import") (part "CPOL-US153CLV-0810"))
    )
    (comp (ref "C22")
      (value "0.1uF")
      (footprint "eagle-import:C1206")
      (libsource (lib "eagle-import") (part "C-USC1206"))
    )
    (comp (ref "C23")
      (value "0.1uF")
      (footprint "eagle-import:C1206")
      (libsource (lib "eagle-import") (part "C-USC1206"))
    )
    (comp (ref "C24")
      (value "22nF")
      (footprint "eagle-import:C1206")
      (libsource (lib "eagle-import") (part "C-USC1206"))
    )
    (comp (ref "C25")
      (value "47uF")
      (footprint "eagle-import:153CLV-0810")
      (libsource (lib "eagle-import") (part "CPOL-US153CLV-0810"))
    )
    (comp (ref "C27")
      (value "47uF")
      (footprint "eagle-import:153CLV-0810")
      (libsource (lib "eagle-import") (part "CPOL-US153CLV-0810"))
    )
    (comp (ref "C28")
      (value "47uF")
      (footprint "eagle-import:153CLV-0810")
      (libsource (lib "eagle-import") (part "CPOL-US153CLV-0810"))
    )
    (comp (ref "J4")
      (value "STRIP3")
      (footprint "eagle-import:STRIP3")
      (libsource (lib "eagle-import") (part "STRIP3"))
    )
    (comp (ref "J6")
      (value "STRIP3")
      (footprint "eagle-import:STRIP3")
      (libsource (lib "eagle-import") (part "STRIP3"))
    )
    (comp (ref "J23")
      (value "STRIP3")
      (footprint "eagle-import:STRIP3")
      (libsource (lib "eagle-import") (part "STRIP3"))
    )
    (comp (ref "J24")
      (value "STRIP3")
      (footprint "eagle-import:STRIP3")
      (libsource (lib "eagle-import") (part "STRIP3"))
    )
    (comp (ref "J78")
      (value "STRIP2")
      (footprint "eagle-import:STRIP2")
      (libsource (lib "eagle-import") (part "STRIP2"))
    )
    (comp (ref "J79")
      (value "STRIP2")
      (footprint "eagle-import:STRIP2")
      (libsource (lib "eagle-import") (part "STRIP2"))
    )
    (comp (ref "J80")
      (value "STRIP2")
      (footprint "eagle-import:STRIP2")
      (libsource (lib "eagle-import") (part "STRIP2"))
    )
    (comp (ref "J81")
      (value "STRIP2")
      (footprint "eagle-import:STRIP2")
      (libsource (lib "eagle-import") (part "STRIP2"))
    )
    (comp (ref "J82")
      (value "STRIP2")
      (footprint "eagle-import:STRIP2")
      (libsource (lib "eagle-import") (part "STRIP2"))
    )
    (comp (ref "J83")
      (value "STRIP2")
      (footprint "eagle-import:STRIP2")
      (libsource (lib "eagle-import") (part "STRIP2"))
    )
    (comp (ref "J84")
      (value "STRIP2")
      (footprint "eagle-import:STRIP2")
      (libsource (lib "eagle-import") (part "STRIP2"))
    )
    (comp (ref "J85")
      (value "STRIP2")
      (footprint "eagle-import:STRIP2")
      (libsource (lib "eagle-import") (part "STRIP2"))
    )
    (comp (ref "J86")
      (value "STRIP2")
      (footprint "eagle-import:STRIP2")
      (libsource (lib "eagle-import") (part "STRIP2"))
    )
    (comp (ref "J87")
      (value "STRIP2")
      (footprint "eagle-import:STRIP2")
      (libsource (lib "eagle-import") (part "STRIP2"))
    )
    (comp (ref "J196")
      (value "STRIP2")
      (footprint "eagle-import:STRIP2")
      (libsource (lib "eagle-import") (part "STRIP2"))
    )
    (comp (ref "J197")
      (value "STRIP2")
      (footprint "eagle-import:STRIP2")
      (libsource (lib "eagle-import") (part "STRIP2"))
    )
    (comp (ref "J198")
      (value "STRIP2")
      (footprint "eagle-import:STRIP2")
      (libsource (lib "eagle-import") (part "STRIP2"))
    )
    (comp (ref "J199")
      (value "STRIP2")
      (footprint "eagle-import:STRIP2")
      (libsource (lib "eagle-import") (part "STRIP2"))
    )
    (comp (ref "J200")
      (value "STRIP2")
      (footprint "eagle-import:STRIP2")
      (libsource (lib "eagle-import") (part "STRIP2"))
    )
    (comp (ref "J201")
      (value "STRIP2")
      (footprint "eagle-import:STRIP2")
      (libsource (lib "eagle-import") (part "STRIP2"))
    )
    (comp (ref "J202")
      (value "STRIP2")
      (footprint "eagle-import:STRIP2")
      (libsource (lib "eagle-import") (part "STRIP2"))
    )
    (comp (ref "J203")
      (value "STRIP2")
      (footprint "eagle-import:STRIP2")
      (libsource (lib "eagle-import") (part "STRIP2"))
    )
    (comp (ref "JP2")
      (value "JP1E")
      (footprint "eagle-import:JP1")
      (libsource (lib "eagle-import") (part "JP1E"))
    )
    (comp (ref "JP3")
      (value "JP1E")
      (footprint "eagle-import:JP1")
      (libsource (lib "eagle-import") (part "JP1E"))
    )
    (comp (ref "R1")
      (value "R_B")
      (footprint "eagle-import:0207_10")
      (libsource (lib "eagle-import") (part "R-US_0207/10"))
    )
    (comp (ref "R2")
      (value "R_B")
      (footprint "eagle-import:0207_10")
      (libsource (lib "eagle-import") (part "R-US_0207/10"))
    )
    (comp (ref "R3")
      (value "24.9K")
      (footprint "eagle-import:M1206")
      (libsource (lib "eagle-import") (part "R-US_M1206"))
    )
    (comp (ref "R4")
      (value "2.2K")
      (footprint "eagle-import:M1206")
      (libsource (lib "eagle-import") (part "R-US_M1206"))
    )
    (comp (ref "R5")
      (value "2.2K")
      (footprint "eagle-import:M1206")
      (libsource (lib "eagle-import") (part "R-US_M1206"))
    )
    (comp (ref "R6")
      (value "2.2K")
      (footprint "eagle-import:M1206")
      (libsource (lib "eagle-import") (part "R-US_M1206"))
    )
    (comp (ref "R7")
      (value "24.9K")
      (footprint "eagle-import:M1206")
      (libsource (lib "eagle-import") (part "R-US_M1206"))
    )
    (comp (ref "R8")
      (value "2.2K")
      (footprint "eagle-import:M1206")
      (libsource (lib "eagle-import") (part "R-US_M1206"))
    )
    (comp (ref "R18")
      (value "2.2K")
      (footprint "eagle-import:M1206")
      (libsource (lib "eagle-import") (part "R-US_M1206"))
    )
    (comp (ref "R24")
      (value "2.2K")
      (footprint "eagle-import:M1206")
      (libsource (lib "eagle-import") (part "R-US_M1206"))
    )
    (comp (ref "R41")
      (value "1.8K")
      (footprint "eagle-import:M1206")
      (libsource (lib "eagle-import") (part "R-US_M1206"))
    )
    (comp (ref "R42")
      (value "10K")
      (footprint "eagle-import:M1206")
      (libsource (lib "eagle-import") (part "R-US_M1206"))
    )
    (comp (ref "R43")
      (value "1.8K")
      (footprint "eagle-import:M1206")
      (libsource (lib "eagle-import") (part "R-US_M1206"))
    )
    (comp (ref "R44")
      (value "10K")
      (footprint "eagle-import:M1206")
      (libsource (lib "eagle-import") (part "R-US_M1206"))
    )
    (comp (ref "S1")
      (value "SWITCH_SLIDE")
      (footprint "eagle-import:SWITCH_SLIDE")
      (libsource (lib "eagle-import") (part "SWITCH_SLIDE"))
    )
    (comp (ref "S129")
      (value "STRIP5")
      (footprint "eagle-import:STRIP5")
      (libsource (lib "eagle-import") (part "STRIP5"))
    )
    (comp (ref "S130")
      (value "STRIP5")
      (footprint "eagle-import:STRIP5")
      (libsource (lib "eagle-import") (part "STRIP5"))
    )
    (comp (ref "S137")
      (value "STRIP5")
      (footprint "eagle-import:STRIP5")
      (libsource (lib "eagle-import") (part "STRIP5"))
    )
    (comp (ref "S138")
      (value "STRIP5")
      (footprint "eagle-import:STRIP5")
      (libsource (lib "eagle-import") (part "STRIP5"))
    )
    (comp (ref "S139")
      (value "STRIP5")
      (footprint "eagle-import:STRIP5")
      (libsource (lib "eagle-import") (part "STRIP5"))
    )
    (comp (ref "S147")
      (value "STRIP5")
      (footprint "eagle-import:STRIP5")
      (libsource (lib "eagle-import") (part "STRIP5"))
    )
    (comp (ref "S159")
      (value "SWITCH_SLIDE")
      (footprint "eagle-import:SWITCH_SLIDE")
      (libsource (lib "eagle-import") (part "SWITCH_SLIDE"))
    )
    (comp (ref "SV1")
      (value "MA03-2")
      (footprint "eagle-import:MA03-2")
      (libsource (lib "eagle-import") (part "MA03-2"))
    )
    (comp (ref "SV3")
      (value "MA03-2")
      (footprint "eagle-import:MA03-2")
      (libsource (lib "eagle-import") (part "MA03-2"))
    )
    (comp (ref "SV7")
      (value "MA03-2")
      (footprint "eagle-import:MA03-2")
      (libsource (lib "eagle-import") (part "MA03-2"))
    )
    (comp (ref "SV8")
      (value "MA03-2")
      (footprint "eagle-import:MA03-2")
      (libsource (lib "eagle-import") (part "MA03-2"))
    )
    (comp (ref "T1")
      (value "TIP125")
      (footprint "eagle-import:TO220")
      (libsource (lib "eagle-import") (part "TIP125"))
    )
    (comp (ref "T2")
      (value "TIP125")
      (footprint "eagle-import:TO220")
      (libsource (lib "eagle-import") (part "TIP125"))
    )
    (comp (ref "TRIMPOT1")
      (value "MA03-2")
      (footprint "eagle-import:MA03-2")
      (libsource (lib "eagle-import") (part "MA03-2"))
    )
    (comp (ref "TRIMPOT2")
      (value "MA03-2")
      (footprint "eagle-import:MA03-2")
      (libsource (lib "eagle-import") (part "MA03-2"))
    )
    (comp (ref "U$2")
      (value "GEARMOTOR_MOUNT")
      (footprint "eagle-import:GEARMOTOR_MOUNT")
      (libsource (lib "eagle-import") (part "GEARMOTOR_MOUNT"))
    )
    (comp (ref "U$3")
      (value "GEARMOTOR_MOUNT")
      (footprint "eagle-import:GEARMOTOR_MOUNT")
      (libsource (lib "eagle-import") (part "GEARMOTOR_MOUNT"))
    )
    (comp (ref "U1")
      (value "A4973")
      (footprint "eagle-import:SO16W")
      (libsource (lib "eagle-import") (part "A3953"))
    )
    (comp (ref "U2")
      (value "DRV8874")
      (footprint "eagle-import:HTSSOP16")
      (libsource (lib "eagle-import") (part "DRV8874"))
    )
    (comp (ref "U4")
      (value "DRV8874")
      (footprint "eagle-import:HTSSOP16")
      (libsource (lib "eagle-import") (part "DRV8874"))
    )
    (comp (ref "U5")
      (value "A4973")
      (footprint "eagle-import:SO16W")
      (libsource (lib "eagle-import") (part "A3953"))
    )
    (comp (ref "3V3")
      (value "LEDCHIPLED_1206")
      (footprint "eagle-import:CHIPLED_1206")
      (libsource (lib "eagle-import") (part "LEDCHIPLED_1206"))
    )
    (comp (ref "5V")
      (value "LEDCHIPLED_1206")
      (footprint "eagle-import:CHIPLED_1206")
      (libsource (lib "eagle-import") (part "LEDCHIPLED_1206"))
    )
    (comp (ref "DCDC3.3V")
      (value "PINHD-1X3")
      (footprint "eagle-import:1X03")
      (libsource (lib "eagle-import") (part "PINHD-1X3"))
    )
    (comp (ref "DCDC5V")
      (value "PINHD-1X3")
      (footprint "eagle-import:1X03")
      (libsource (lib "eagle-import") (part "PINHD-1X3"))
    )
    (comp (ref "J5")
      (value "JACK-PMS")
      (footprint "eagle-import:JACK-PMS")
      (libsource (lib "eagle-import") (part "JACK-PMS"))
    )
    (comp (ref "J10")
      (value "STRIP3")
      (footprint "eagle-import:STRIP3")
      (libsource (lib "eagle-import") (part "STRIP3"))
    )
    (comp (ref "J14")
      (value "STRIP3")
      (footprint "eagle-import:STRIP3")
      (libsource (lib "eagle-import") (part "STRIP3"))
    )
    (comp (ref "J15")
      (value "STRIP3")
      (footprint "eagle-import:STRIP3")
      (libsource (lib "eagle-import") (part "STRIP3"))
    )
    (comp (ref "J16")
      (value "STRIP3")
      (footprint "eagle-import:STRIP3")
      (libsource (lib "eagle-import") (part "STRIP3"))
    )
    (comp (ref "J17")
      (value "STRIP3")
      (footprint "eagle-import:STRIP3")
      (libsource (lib "eagle-import") (part "STRIP3"))
    )
    (comp (ref "J18")
      (value "STRIP3")
      (footprint "eagle-import:STRIP3")
      (libsource (lib "eagle-import") (part "STRIP3"))
    )
    (comp (ref "J19")
      (value "STRIP3")
      (footprint "eagle-import:STRIP3")
      (libsource (lib "eagle-import") (part "STRIP3"))
    )
    (comp (ref "J20")
      (value "STRIP3")
      (footprint "eagle-import:STRIP3")
      (libsource (lib "eagle-import") (part "STRIP3"))
    )
    (comp (ref "J21")
      (value "STRIP3")
      (footprint "eagle-import:STRIP3")
      (libsource (lib "eagle-import") (part "STRIP3"))
    )
    (comp (ref "J28")
      (value "STRIP3")
      (footprint "eagle-import:STRIP3")
      (libsource (lib "eagle-import") (part "STRIP3"))
    )
    (comp (ref "J29")
      (value "STRIP3")
      (footprint "eagle-import:STRIP3")
      (libsource (lib "eagle-import") (part "STRIP3"))
    )
    (comp (ref "J30")
      (value "STRIP3")
      (footprint "eagle-import:STRIP3")
      (libsource (lib "eagle-import") (part "STRIP3"))
    )
    (comp (ref "J31")
      (value "STRIP3")
      (footprint "eagle-import:STRIP3")
      (libsource (lib "eagle-import") (part "STRIP3"))
    )
    (comp (ref "J32")
      (value "STRIP3")
      (footprint "eagle-import:STRIP3")
      (libsource (lib "eagle-import") (part "STRIP3"))
    )
    (comp (ref "J33")
      (value "STRIP3")
      (footprint "eagle-import:STRIP3")
      (libsource (lib "eagle-import") (part "STRIP3"))
    )
    (comp (ref "J98")
      (value "STRIP3")
      (footprint "eagle-import:STRIP3")
      (libsource (lib "eagle-import") (part "STRIP3"))
    )
    (comp (ref "J99")
      (value "STRIP3")
      (footprint "eagle-import:STRIP3")
      (libsource (lib "eagle-import") (part "STRIP3"))
    )
    (comp (ref "J100")
      (value "STRIP3")
      (footprint "eagle-import:STRIP3")
      (libsource (lib "eagle-import") (part "STRIP3"))
    )
    (comp (ref "J101")
      (value "STRIP3")
      (footprint "eagle-import:STRIP3")
      (libsource (lib "eagle-import") (part "STRIP3"))
    )
    (comp (ref "J102")
      (value "STRIP3")
      (footprint "eagle-import:STRIP3")
      (libsource (lib "eagle-import") (part "STRIP3"))
    )
    (comp (ref "J103")
      (value "STRIP3")
      (footprint "eagle-import:STRIP3")
      (libsource (lib "eagle-import") (part "STRIP3"))
    )
    (comp (ref "J104")
      (value "STRIP3")
      (footprint "eagle-import:STRIP3")
      (libsource (lib "eagle-import") (part "STRIP3"))
    )
    (comp (ref "J105")
      (value "STRIP3")
      (footprint "eagle-import:STRIP3")
      (libsource (lib "eagle-import") (part "STRIP3"))
    )
    (comp (ref "J106")
      (value "STRIP3")
      (footprint "eagle-import:STRIP3")
      (libsource (lib "eagle-import") (part "STRIP3"))
    )
    (comp (ref "J107")
      (value "STRIP3")
      (footprint "eagle-import:STRIP3")
      (libsource (lib "eagle-import") (part "STRIP3"))
    )
    (comp (ref "J108")
      (value "STRIP3")
      (footprint "eagle-import:STRIP3")
      (libsource (lib "eagle-import") (part "STRIP3"))
    )
    (comp (ref "J109")
      (value "STRIP3")
      (footprint "eagle-import:STRIP3")
      (libsource (lib "eagle-import") (part "STRIP3"))
    )
    (comp (ref "J110")
      (value "STRIP3")
      (footprint "eagle-import:STRIP3")
      (libsource (lib "eagle-import") (part "STRIP3"))
    )
    (comp (ref "J111")
      (value "STRIP3")
      (footprint "eagle-import:STRIP3")
      (libsource (lib "eagle-import") (part "STRIP3"))
    )
    (comp (ref "J112")
      (value "STRIP3")
      (footprint "eagle-import:STRIP3")
      (libsource (lib "eagle-import") (part "STRIP3"))
    )
    (comp (ref "J113")
      (value "STRIP3")
      (footprint "eagle-import:STRIP3")
      (libsource (lib "eagle-import") (part "STRIP3"))
    )
    (comp (ref "J114")
      (value "STRIP3")
      (footprint "eagle-import:STRIP3")
      (libsource (lib "eagle-import") (part "STRIP3"))
    )
    (comp (ref "J115")
      (value "STRIP3")
      (footprint "eagle-import:STRIP3")
      (libsource (lib "eagle-import") (part "STRIP3"))
    )
    (comp (ref "J116")
      (value "STRIP3")
      (footprint "eagle-import:STRIP3")
      (libsource (lib "eagle-import") (part "STRIP3"))
    )
    (comp (ref "J117")
      (value "STRIP3")
      (footprint "eagle-import:STRIP3")
      (libsource (lib "eagle-import") (part "STRIP3"))
    )
    (comp (ref "J118")
      (value "STRIP3")
      (footprint "eagle-import:STRIP3")
      (libsource (lib "eagle-import") (part "STRIP3"))
    )
    (comp (ref "J119")
      (value "STRIP3")
      (footprint "eagle-import:STRIP3")
      (libsource (lib "eagle-import") (part "STRIP3"))
    )
    (comp (ref "J120")
      (value "STRIP3")
      (footprint "eagle-import:STRIP3")
      (libsource (lib "eagle-import") (part "STRIP3"))
    )
    (comp (ref "J121")
      (value "STRIP3")
      (footprint "eagle-import:STRIP3")
      (libsource (lib "eagle-import") (part "STRIP3"))
    )
    (comp (ref "J122")
      (value "STRIP3")
      (footprint "eagle-import:STRIP3")
      (libsource (lib "eagle-import") (part "STRIP3"))
    )
    (comp (ref "J123")
      (value "STRIP3")
      (footprint "eagle-import:STRIP3")
      (libsource (lib "eagle-import") (part "STRIP3"))
    )
    (comp (ref "J124")
      (value "STRIP3")
      (footprint "eagle-import:STRIP3")
      (libsource (lib "eagle-import") (part "STRIP3"))
    )
    (comp (ref "J125")
      (value "STRIP3")
      (footprint "eagle-import:STRIP3")
      (libsource (lib "eagle-import") (part "STRIP3"))
    )
    (comp (ref "J126")
      (value "STRIP3")
      (footprint "eagle-import:STRIP3")
      (libsource (lib "eagle-import") (part "STRIP3"))
    )
    (comp (ref "J127")
      (value "STRIP3")
      (footprint "eagle-import:STRIP3")
      (libsource (lib "eagle-import") (part "STRIP3"))
    )
    (comp (ref "J128")
      (value "STRIP3")
      (footprint "eagle-import:STRIP3")
      (libsource (lib "eagle-import") (part "STRIP3"))
    )
    (comp (ref "J129")
      (value "STRIP3")
      (footprint "eagle-import:STRIP3")
      (libsource (lib "eagle-import") (part "STRIP3"))
    )
    (comp (ref "J130")
      (value "STRIP3")
      (footprint "eagle-import:STRIP3")
      (libsource (lib "eagle-import") (part "STRIP3"))
    )
    (comp (ref "J131")
      (value "STRIP3")
      (footprint "eagle-import:STRIP3")
      (libsource (lib "eagle-import") (part "STRIP3"))
    )
    (comp (ref "J132")
      (value "STRIP3")
      (footprint "eagle-import:STRIP3")
      (libsource (lib "eagle-import") (part "STRIP3"))
    )
    (comp (ref "J133")
      (value "STRIP3")
      (footprint "eagle-import:STRIP3")
      (libsource (lib "eagle-import") (part "STRIP3"))
    )
    (comp (ref "J134")
      (value "STRIP3")
      (footprint "eagle-import:STRIP3")
      (libsource (lib "eagle-import") (part "STRIP3"))
    )
    (comp (ref "J135")
      (value "STRIP3")
      (footprint "eagle-import:STRIP3")
      (libsource (lib "eagle-import") (part "STRIP3"))
    )
    (comp (ref "J136")
      (value "STRIP3")
      (footprint "eagle-import:STRIP3")
      (libsource (lib "eagle-import") (part "STRIP3"))
    )
    (comp (ref "J137")
      (value "STRIP3")
      (footprint "eagle-import:STRIP3")
      (libsource (lib "eagle-import") (part "STRIP3"))
    )
    (comp (ref "J138")
      (value "STRIP3")
      (footprint "eagle-import:STRIP3")
      (libsource (lib "eagle-import") (part "STRIP3"))
    )
    (comp (ref "J139")
      (value "STRIP3")
      (footprint "eagle-import:STRIP3")
      (libsource (lib "eagle-import") (part "STRIP3"))
    )
    (comp (ref "J140")
      (value "STRIP3")
      (footprint "eagle-import:STRIP3")
      (libsource (lib "eagle-import") (part "STRIP3"))
    )
    (comp (ref "J141")
      (value "STRIP3")
      (footprint "eagle-import:STRIP3")
      (libsource (lib "eagle-import") (part "STRIP3"))
    )
    (comp (ref "J142")
      (value "STRIP3")
      (footprint "eagle-import:STRIP3")
      (libsource (lib "eagle-import") (part "STRIP3"))
    )
    (comp (ref "J143")
      (value "STRIP3")
      (footprint "eagle-import:STRIP3")
      (libsource (lib "eagle-import") (part "STRIP3"))
    )
    (comp (ref "J144")
      (value "STRIP3")
      (footprint "eagle-import:STRIP3")
      (libsource (lib "eagle-import") (part "STRIP3"))
    )
    (comp (ref "J145")
      (value "STRIP3")
      (footprint "eagle-import:STRIP3")
      (libsource (lib "eagle-import") (part "STRIP3"))
    )
    (comp (ref "J146")
      (value "STRIP3")
      (footprint "eagle-import:STRIP3")
      (libsource (lib "eagle-import") (part "STRIP3"))
    )
    (comp (ref "J147")
      (value "STRIP3")
      (footprint "eagle-import:STRIP3")
      (libsource (lib "eagle-import") (part "STRIP3"))
    )
    (comp (ref "J148")
      (value "STRIP3")
      (footprint "eagle-import:STRIP3")
      (libsource (lib "eagle-import") (part "STRIP3"))
    )
    (comp (ref "J149")
      (value "STRIP3")
      (footprint "eagle-import:STRIP3")
      (libsource (lib "eagle-import") (part "STRIP3"))
    )
    (comp (ref "J150")
      (value "STRIP3")
      (footprint "eagle-import:STRIP3")
      (libsource (lib "eagle-import") (part "STRIP3"))
    )
    (comp (ref "J151")
      (value "STRIP3")
      (footprint "eagle-import:STRIP3")
      (libsource (lib "eagle-import") (part "STRIP3"))
    )
    (comp (ref "J152")
      (value "STRIP3")
      (footprint "eagle-import:STRIP3")
      (libsource (lib "eagle-import") (part "STRIP3"))
    )
    (comp (ref "J153")
      (value "STRIP3")
      (footprint "eagle-import:STRIP3")
      (libsource (lib "eagle-import") (part "STRIP3"))
    )
    (comp (ref "J154")
      (value "STRIP3")
      (footprint "eagle-import:STRIP3")
      (libsource (lib "eagle-import") (part "STRIP3"))
    )
    (comp (ref "J155")
      (value "STRIP3")
      (footprint "eagle-import:STRIP3")
      (libsource (lib "eagle-import") (part "STRIP3"))
    )
    (comp (ref "J156")
      (value "STRIP3")
      (footprint "eagle-import:STRIP3")
      (libsource (lib "eagle-import") (part "STRIP3"))
    )
    (comp (ref "J157")
      (value "STRIP3")
      (footprint "eagle-import:STRIP3")
      (libsource (lib "eagle-import") (part "STRIP3"))
    )
    (comp (ref "J158")
      (value "STRIP3")
      (footprint "eagle-import:STRIP3")
      (libsource (lib "eagle-import") (part "STRIP3"))
    )
    (comp (ref "J159")
      (value "STRIP3")
      (footprint "eagle-import:STRIP3")
      (libsource (lib "eagle-import") (part "STRIP3"))
    )
    (comp (ref "J160")
      (value "STRIP3")
      (footprint "eagle-import:STRIP3")
      (libsource (lib "eagle-import") (part "STRIP3"))
    )
    (comp (ref "J161")
      (value "STRIP3")
      (footprint "eagle-import:STRIP3")
      (libsource (lib "eagle-import") (part "STRIP3"))
    )
    (comp (ref "J162")
      (value "STRIP3")
      (footprint "eagle-import:STRIP3")
      (libsource (lib "eagle-import") (part "STRIP3"))
    )
    (comp (ref "J163")
      (value "STRIP3")
      (footprint "eagle-import:STRIP3")
      (libsource (lib "eagle-import") (part "STRIP3"))
    )
    (comp (ref "J164")
      (value "STRIP3")
      (footprint "eagle-import:STRIP3")
      (libsource (lib "eagle-import") (part "STRIP3"))
    )
    (comp (ref "J165")
      (value "STRIP3")
      (footprint "eagle-import:STRIP3")
      (libsource (lib "eagle-import") (part "STRIP3"))
    )
    (comp (ref "J166")
      (value "STRIP3")
      (footprint "eagle-import:STRIP3")
      (libsource (lib "eagle-import") (part "STRIP3"))
    )
    (comp (ref "J167")
      (value "STRIP3")
      (footprint "eagle-import:STRIP3")
      (libsource (lib "eagle-import") (part "STRIP3"))
    )
    (comp (ref "J168")
      (value "STRIP3")
      (footprint "eagle-import:STRIP3")
      (libsource (lib "eagle-import") (part "STRIP3"))
    )
    (comp (ref "J169")
      (value "STRIP3")
      (footprint "eagle-import:STRIP3")
      (libsource (lib "eagle-import") (part "STRIP3"))
    )
    (comp (ref "J170")
      (value "STRIP3")
      (footprint "eagle-import:STRIP3")
      (libsource (lib "eagle-import") (part "STRIP3"))
    )
    (comp (ref "J176")
      (value "STRIP3")
      (footprint "eagle-import:STRIP3")
      (libsource (lib "eagle-import") (part "STRIP3"))
    )
    (comp (ref "J177")
      (value "STRIP3")
      (footprint "eagle-import:STRIP3")
      (libsource (lib "eagle-import") (part "STRIP3"))
    )
    (comp (ref "J204")
      (value "STRIP2")
      (footprint "eagle-import:STRIP2")
      (libsource (lib "eagle-import") (part "STRIP2"))
    )
    (comp (ref "J205")
      (value "STRIP2")
      (footprint "eagle-import:STRIP2")
      (libsource (lib "eagle-import") (part "STRIP2"))
    )
    (comp (ref "J206")
      (value "STRIP2")
      (footprint "eagle-import:STRIP2")
      (libsource (lib "eagle-import") (part "STRIP2"))
    )
    (comp (ref "J207")
      (value "STRIP2")
      (footprint "eagle-import:STRIP2")
      (libsource (lib "eagle-import") (part "STRIP2"))
    )
    (comp (ref "J251")
      (value "STRIP2")
      (footprint "eagle-import:STRIP2")
      (libsource (lib "eagle-import") (part "STRIP2"))
    )
    (comp (ref "L1")
      (value "F28379D_LAUNCHPAD")
      (footprint "eagle-import:F28379D_LAUNCHPAD")
      (libsource (lib "eagle-import") (part "F28379D_LAUNCHPAD"))
    )
    (comp (ref "POWER")
      (value "PINHD-1X2")
      (footprint "eagle-import:1X02")
      (libsource (lib "eagle-import") (part "PINHD-1X2"))
    )
    (comp (ref "R26")
      (value "470")
      (footprint "eagle-import:M1206")
      (libsource (lib "eagle-import") (part "R-US_M1206"))
    )
    (comp (ref "R27")
      (value "470")
      (footprint "eagle-import:M1206")
      (libsource (lib "eagle-import") (part "R-US_M1206"))
    )
    (comp (ref "S141")
      (value "STRIP5")
      (footprint "eagle-import:STRIP5")
      (libsource (lib "eagle-import") (part "STRIP5"))
    )
    (comp (ref "U$1")
      (value "MPU-9250-BB")
      (footprint "eagle-import:MPU-9250-BB")
      (libsource (lib "eagle-import") (part "MPU-9250-BB"))
    )
  )
  (nets
    (net (code "1") (name "+5V") (class "Default")
      (node (ref "DCDC5V") (pin "3") (pinfunction "3_3") (pintype "passive"))
      (node (ref "J103") (pin "P$1") (pinfunction "P$1_P$1") (pintype "bidirectional"))
      (node (ref "J103") (pin "P$2") (pinfunction "P$2_P$2") (pintype "bidirectional"))
      (node (ref "J103") (pin "P$3") (pinfunction "P$3_P$3") (pintype "bidirectional"))
      (node (ref "J152") (pin "P$1") (pinfunction "P$1_P$1") (pintype "bidirectional"))
      (node (ref "J152") (pin "P$2") (pinfunction "P$2_P$2") (pintype "bidirectional"))
      (node (ref "J152") (pin "P$3") (pinfunction "P$3_P$3") (pintype "bidirectional"))
      (node (ref "J200") (pin "P$1") (pinfunction "P$1_P$1") (pintype "bidirectional"))
      (node (ref "J200") (pin "P$2") (pinfunction "P$2_P$2") (pintype "bidirectional"))
      (node (ref "J203") (pin "P$1") (pinfunction "P$1_P$1") (pintype "bidirectional"))
      (node (ref "J203") (pin "P$2") (pinfunction "P$2_P$2") (pintype "bidirectional"))
      (node (ref "L1") (pin "P$21") (pinfunction "5V_1_P$21") (pintype "bidirectional"))
      (node (ref "L1") (pin "P$61") (pinfunction "5V_2_P$61") (pintype "bidirectional"))
      (node (ref "R26") (pin "2") (pinfunction "2_2") (pintype "passive"))
      (node (ref "S17") (pin "P$1") (pinfunction "P$1_P$1") (pintype "bidirectional"))
      (node (ref "S17") (pin "P$2") (pinfunction "P$2_P$2") (pintype "bidirectional"))
      (node (ref "S17") (pin "P$3") (pinfunction "P$3_P$3") (pintype "bidirectional"))
      (node (ref "S17") (pin "P$4") (pinfunction "P$4_P$4") (pintype "bidirectional"))
      (node (ref "S17") (pin "P$5") (pinfunction "P$5_P$5") (pintype "bidirectional"))
      (node (ref "S18") (pin "P$1") (pinfunction "P$1_P$1") (pintype "bidirectional"))
      (node (ref "S18") (pin "P$2") (pinfunction "P$2_P$2") (pintype "bidirectional"))
      (node (ref "S18") (pin "P$3") (pinfunction "P$3_P$3") (pintype "bidirectional"))
      (node (ref "S18") (pin "P$4") (pinfunction "P$4_P$4") (pintype "bidirectional"))
      (node (ref "S18") (pin "P$5") (pinfunction "P$5_P$5") (pintype "bidirectional"))
      (node (ref "SV2") (pin "1") (pinfunction "1_1") (pintype "passive"))
      (node (ref "SV2") (pin "2") (pinfunction "2_2") (pintype "passive"))
      (node (ref "SV2") (pin "3") (pinfunction "3_3") (pintype "passive"))
      (node (ref "SV2") (pin "4") (pinfunction "4_4") (pintype "passive"))
    )
    (net (code "2") (name "A4973EN") (class "Default")
      (node (ref "S1") (pin "P$2") (pinfunction "P2_P$2") (pintype "bidirectional"))
      (node (ref "U1") (pin "8") (pinfunction "~{ENABLE}_8") (pintype "bidirectional"))
      (node (ref "U5") (pin "8") (pinfunction "~{ENABLE}_8") (pintype "bidirectional"))
    )
    (net (code "3") (name "ADCIN14") (class "Default")
      (node (ref "J105") (pin "P$1") (pinfunction "P$1_P$1") (pintype "bidirectional"))
      (node (ref "J105") (pin "P$2") (pinfunction "P$2_P$2") (pintype "bidirectional"))
      (node (ref "J105") (pin "P$3") (pinfunction "P$3_P$3") (pintype "bidirectional"))
      (node (ref "L1") (pin "P$23") (pinfunction "ADCIN14_P$23") (pintype "bidirectional"))
    )
    (net (code "4") (name "ADCIN15") (class "Default")
      (node (ref "J150") (pin "P$1") (pinfunction "P$1_P$1") (pintype "bidirectional"))
      (node (ref "J150") (pin "P$2") (pinfunction "P$2_P$2") (pintype "bidirectional"))
      (node (ref "J150") (pin "P$3") (pinfunction "P$3_P$3") (pintype "bidirectional"))
      (node (ref "L1") (pin "P$63") (pinfunction "ADCIN15_P$63") (pintype "bidirectional"))
    )
    (net (code "5") (name "ADCINA2") (class "Default")
      (node (ref "J111") (pin "P$1") (pinfunction "P$1_P$1") (pintype "bidirectional"))
      (node (ref "J111") (pin "P$2") (pinfunction "P$2_P$2") (pintype "bidirectional"))
      (node (ref "J111") (pin "P$3") (pinfunction "P$3_P$3") (pintype "bidirectional"))
      (node (ref "L1") (pin "P$29") (pinfunction "ADCINA2_P$29") (pintype "bidirectional"))
      (node (ref "SV11") (pin "3") (pinfunction "3_3") (pintype "passive"))
    )
    (net (code "6") (name "ADCINA3") (class "Default")
      (node (ref "J108") (pin "P$1") (pinfunction "P$1_P$1") (pintype "bidirectional"))
      (node (ref "J108") (pin "P$2") (pinfunction "P$2_P$2") (pintype "bidirectional"))
      (node (ref "J108") (pin "P$3") (pinfunction "P$3_P$3") (pintype "bidirectional"))
      (node (ref "L1") (pin "P$26") (pinfunction "ADCINA3_P$26") (pintype "bidirectional"))
      (node (ref "SV11") (pin "4") (pinfunction "4_4") (pintype "passive"))
    )
    (net (code "7") (name "ADCINA4") (class "Default")
      (node (ref "J144") (pin "P$1") (pinfunction "P$1_P$1") (pintype "bidirectional"))
      (node (ref "J144") (pin "P$2") (pinfunction "P$2_P$2") (pintype "bidirectional"))
      (node (ref "J144") (pin "P$3") (pinfunction "P$3_P$3") (pintype "bidirectional"))
      (node (ref "L1") (pin "P$69") (pinfunction "ADCINA4_P$69") (pintype "bidirectional"))
    )
    (net (code "8") (name "ADCINA5") (class "Default")
      (node (ref "J147") (pin "P$1") (pinfunction "P$1_P$1") (pintype "bidirectional"))
      (node (ref "J147") (pin "P$2") (pinfunction "P$2_P$2") (pintype "bidirectional"))
      (node (ref "J147") (pin "P$3") (pinfunction "P$3_P$3") (pintype "bidirectional"))
      (node (ref "L1") (pin "P$66") (pinfunction "ADCINA5_P$66") (pintype "bidirectional"))
    )
    (net (code "9") (name "ADCINB2") (class "Default")
      (node (ref "J110") (pin "P$1") (pinfunction "P$1_P$1") (pintype "bidirectional"))
      (node (ref "J110") (pin "P$2") (pinfunction "P$2_P$2") (pintype "bidirectional"))
      (node (ref "J110") (pin "P$3") (pinfunction "P$3_P$3") (pintype "bidirectional"))
      (node (ref "L1") (pin "P$28") (pinfunction "ADCINB2_P$28") (pintype "bidirectional"))
    )
    (net (code "10") (name "ADCINB3") (class "Default")
      (node (ref "J107") (pin "P$1") (pinfunction "P$1_P$1") (pintype "bidirectional"))
      (node (ref "J107") (pin "P$2") (pinfunction "P$2_P$2") (pintype "bidirectional"))
      (node (ref "J107") (pin "P$3") (pinfunction "P$3_P$3") (pintype "bidirectional"))
      (node (ref "L1") (pin "P$25") (pinfunction "ADCINB3_P$25") (pintype "bidirectional"))
    )
    (net (code "11") (name "ADCINB4") (class "Default")
      (node (ref "J145") (pin "P$1") (pinfunction "P$1_P$1") (pintype "bidirectional"))
      (node (ref "J145") (pin "P$2") (pinfunction "P$2_P$2") (pintype "bidirectional"))
      (node (ref "J145") (pin "P$3") (pinfunction "P$3_P$3") (pintype "bidirectional"))
      (node (ref "L1") (pin "P$68") (pinfunction "ADCINB4_P$68") (pintype "bidirectional"))
      (node (ref "SV12") (pin "4") (pinfunction "4_4") (pintype "passive"))
    )
    (net (code "12") (name "ADCINB5") (class "Default")
      (node (ref "J148") (pin "P$1") (pinfunction "P$1_P$1") (pintype "bidirectional"))
      (node (ref "J148") (pin "P$2") (pinfunction "P$2_P$2") (pintype "bidirectional"))
      (node (ref "J148") (pin "P$3") (pinfunction "P$3_P$3") (pintype "bidirectional"))
      (node (ref "L1") (pin "P$65") (pinfunction "ADCINB5_P$65") (pintype "bidirectional"))
    )
    (net (code "13") (name "ADCINC2") (class "Default")
      (node (ref "J109") (pin "P$1") (pinfunction "P$1_P$1") (pintype "bidirectional"))
      (node (ref "J109") (pin "P$2") (pinfunction "P$2_P$2") (pintype "bidirectional"))
      (node (ref "J109") (pin "P$3") (pinfunction "P$3_P$3") (pintype "bidirectional"))
      (node (ref "L1") (pin "P$27") (pinfunction "ADCINC2_P$27") (pintype "bidirectional"))
    )
    (net (code "14") (name "ADCINC3") (class "Default")
      (node (ref "J106") (pin "P$1") (pinfunction "P$1_P$1") (pintype "bidirectional"))
      (node (ref "J106") (pin "P$2") (pinfunction "P$2_P$2") (pintype "bidirectional"))
      (node (ref "J106") (pin "P$3") (pinfunction "P$3_P$3") (pintype "bidirectional"))
      (node (ref "L1") (pin "P$24") (pinfunction "ADCINC3_P$24") (pintype "bidirectional"))
    )
    (net (code "15") (name "ADCINC4") (class "Default")
      (node (ref "J146") (pin "P$1") (pinfunction "P$1_P$1") (pintype "bidirectional"))
      (node (ref "J146") (pin "P$2") (pinfunction "P$2_P$2") (pintype "bidirectional"))
      (node (ref "J146") (pin "P$3") (pinfunction "P$3_P$3") (pintype "bidirectional"))
      (node (ref "L1") (pin "P$67") (pinfunction "ADCINC4_P$67") (pintype "bidirectional"))
    )
    (net (code "16") (name "ADCINC5") (class "Default")
      (node (ref "J149") (pin "P$1") (pinfunction "P$1_P$1") (pintype "bidirectional"))
      (node (ref "J149") (pin "P$2") (pinfunction "P$2_P$2") (pintype "bidirectional"))
      (node (ref "J149") (pin "P$3") (pinfunction "P$3_P$3") (pintype "bidirectional"))
      (node (ref "L1") (pin "P$64") (pinfunction "ADCINC5_P$64") (pintype "bidirectional"))
    )
    (net (code "17") (name "DACOUTA") (class "Default")
      (node (ref "J112") (pin "P$1") (pinfunction "P$1_P$1") (pintype "bidirectional"))
      (node (ref "J112") (pin "P$2") (pinfunction "P$2_P$2") (pintype "bidirectional"))
      (node (ref "J112") (pin "P$3") (pinfunction "P$3_P$3") (pintype "bidirectional"))
      (node (ref "L1") (pin "P$30") (pinfunction "ADCINA0/DACOUTA_P$30") (pintype "bidirectional"))
    )
    (net (code "18") (name "DACOUTB") (class "Default")
      (node (ref "J143") (pin "P$1") (pinfunction "P$1_P$1") (pintype "bidirectional"))
      (node (ref "J143") (pin "P$2") (pinfunction "P$2_P$2") (pintype "bidirectional"))
      (node (ref "J143") (pin "P$3") (pinfunction "P$3_P$3") (pintype "bidirectional"))
      (node (ref "L1") (pin "P$70") (pinfunction "ADCINA1/DACOUTB_P$70") (pintype "bidirectional"))
    )
    (net (code "19") (name "DRV1_DIR") (class "Default")
      (node (ref "J80") (pin "P$1") (pinfunction "P$1_P$1") (pintype "bidirectional"))
      (node (ref "J80") (pin "P$2") (pinfunction "P$2_P$2") (pintype "bidirectional"))
      (node (ref "U2") (pin "P$2") (pinfunction "PH/IN2_P$2") (pintype "bidirectional"))
    )
    (net (code "20") (name "DRV1_M+") (class "Default")
      (node (ref "SV7") (pin "1") (pinfunction "1_1") (pintype "passive"))
      (node (ref "SV7") (pin "3") (pinfunction "3_3") (pintype "passive"))
      (node (ref "SV7") (pin "5") (pinfunction "5_5") (pintype "passive"))
      (node (ref "U2") (pin "P$8") (pinfunction "OUT1_P$8") (pintype "bidirectional"))
    )
    (net (code "21") (name "DRV1_M-") (class "Default")
      (node (ref "SV7") (pin "2") (pinfunction "2_2") (pintype "passive"))
      (node (ref "SV7") (pin "4") (pinfunction "4_4") (pintype "passive"))
      (node (ref "SV7") (pin "6") (pinfunction "6_6") (pintype "passive"))
      (node (ref "U2") (pin "P$10") (pinfunction "OUT2_P$10") (pintype "bidirectional"))
    )
    (net (code "22") (name "DRV1_PWM") (class "Default")
      (node (ref "J79") (pin "P$1") (pinfunction "P$1_P$1") (pintype "bidirectional"))
      (node (ref "J79") (pin "P$2") (pinfunction "P$2_P$2") (pintype "bidirectional"))
      (node (ref "U2") (pin "P$1") (pinfunction "EN/IN1_P$1") (pintype "bidirectional"))
    )
    (net (code "23") (name "DRV2_DIR") (class "Default")
      (node (ref "J83") (pin "P$1") (pinfunction "P$1_P$1") (pintype "bidirectional"))
      (node (ref "J83") (pin "P$2") (pinfunction "P$2_P$2") (pintype "bidirectional"))
      (node (ref "U4") (pin "P$2") (pinfunction "PH/IN2_P$2") (pintype "bidirectional"))
    )
    (net (code "24") (name "DRV2_M+") (class "Default")
      (node (ref "SV8") (pin "1") (pinfunction "1_1") (pintype "passive"))
      (node (ref "SV8") (pin "3") (pinfunction "3_3") (pintype "passive"))
      (node (ref "SV8") (pin "5") (pinfunction "5_5") (pintype "passive"))
      (node (ref "U4") (pin "P$8") (pinfunction "OUT1_P$8") (pintype "bidirectional"))
    )
    (net (code "25") (name "DRV2_M-") (class "Default")
      (node (ref "SV8") (pin "2") (pinfunction "2_2") (pintype "passive"))
      (node (ref "SV8") (pin "4") (pinfunction "4_4") (pintype "passive"))
      (node (ref "SV8") (pin "6") (pinfunction "6_6") (pintype "passive"))
      (node (ref "U4") (pin "P$10") (pinfunction "OUT2_P$10") (pintype "bidirectional"))
    )
    (net (code "26") (name "DRV2_PWM") (class "Default")
      (node (ref "J82") (pin "P$1") (pinfunction "P$1_P$1") (pintype "bidirectional"))
      (node (ref "J82") (pin "P$2") (pinfunction "P$2_P$2") (pintype "bidirectional"))
      (node (ref "U4") (pin "P$1") (pinfunction "EN/IN1_P$1") (pintype "bidirectional"))
    )
    (net (code "27") (name "GND") (class "Default")
      (node (ref "3V3") (pin "C") (pinfunction "C_C") (pintype "passive"))
      (node (ref "5V") (pin "C") (pinfunction "C_C") (pintype "passive"))
      (node (ref "B1") (pin "P$2") (pinfunction "P$2_P$2") (pintype "bidirectional"))
      (node (ref "B2") (pin "P$2") (pinfunction "BAT-_P$2") (pintype "bidirectional"))
      (node (ref "B3") (pin "P$1") (pinfunction "P1_P$1") (pintype "bidirectional"))
      (node (ref "C1") (pin "-") (pinfunction "-_-") (pintype "passive"))
      (node (ref "C10") (pin "2") (pinfunction "2_2") (pintype "passive"))
      (node (ref "C12") (pin "-") (pinfunction "-_-") (pintype "passive"))
      (node (ref "C13") (pin "-") (pinfunction "-_-") (pintype "passive"))
      (node (ref "C14") (pin "2") (pinfunction "2_2") (pintype "passive"))
      (node (ref "C15") (pin "-") (pinfunction "-_-") (pintype "passive"))
      (node (ref "C16") (pin "2") (pinfunction "2_2") (pintype "passive"))
      (node (ref "C2") (pin "2") (pinfunction "2_2") (pintype "passive"))
      (node (ref "C20") (pin "-") (pinfunction "-_-") (pintype "passive"))
      (node (ref "C22") (pin "2") (pinfunction "2_2") (pintype "passive"))
      (node (ref "C25") (pin "-") (pinfunction "-_-") (pintype "passive"))
      (node (ref "C27") (pin "-") (pinfunction "-_-") (pintype "passive"))
      (node (ref "C28") (pin "-") (pinfunction "-_-") (pintype "passive"))
      (node (ref "C3") (pin "2") (pinfunction "2_2") (pintype "passive"))
      (node (ref "C4") (pin "2") (pinfunction "2_2") (pintype "passive"))
      (node (ref "C6") (pin "2") (pinfunction "2_2") (pintype "passive"))
      (node (ref "C9") (pin "2") (pinfunction "2_2") (pintype "passive"))
      (node (ref "DCDC3.3V") (pin "2") (pinfunction "2_2") (pintype "passive"))
      (node (ref "DCDC5V") (pin "2") (pinfunction "2_2") (pintype "passive"))
      (node (ref "ETH1") (pin "P$1") (pinfunction "GND_1_P$1") (pintype "bidirectional"))
      (node (ref "ETH1") (pin "P$12") (pinfunction "GND_3_P$12") (pintype "bidirectional"))
      (node (ref "ETH1") (pin "P$2") (pinfunction "GND_2_P$2") (pintype "bidirectional"))
      (node (ref "G1") (pin "-") (pinfunction "-_-") (pintype "passive"))
      (node (ref "IC1") (pin "7") (pinfunction "GND_7") (pintype "power_in"))
      (node (ref "IC2") (pin "7") (pinfunction "GND_7") (pintype "power_in"))
      (node (ref "IC3") (pin "7") (pinfunction "GND_7") (pintype "power_in"))
      (node (ref "J102") (pin "P$1") (pinfunction "P$1_P$1") (pintype "bidirectional"))
      (node (ref "J102") (pin "P$2") (pinfunction "P$2_P$2") (pintype "bidirectional"))
      (node (ref "J102") (pin "P$3") (pinfunction "P$3_P$3") (pintype "bidirectional"))
      (node (ref "J104") (pin "P$1") (pinfunction "P$1_P$1") (pintype "bidirectional"))
      (node (ref "J104") (pin "P$2") (pinfunction "P$2_P$2") (pintype "bidirectional"))
      (node (ref "J104") (pin "P$3") (pinfunction "P$3_P$3") (pintype "bidirectional"))
      (node (ref "J124") (pin "P$1") (pinfunction "P$1_P$1") (pintype "bidirectional"))
      (node (ref "J124") (pin "P$2") (pinfunction "P$2_P$2") (pintype "bidirectional"))
      (node (ref "J124") (pin "P$3") (pinfunction "P$3_P$3") (pintype "bidirectional"))
      (node (ref "J151") (pin "P$1") (pinfunction "P$1_P$1") (pintype "bidirectional"))
      (node (ref "J151") (pin "P$2") (pinfunction "P$2_P$2") (pintype "bidirectional"))
      (node (ref "J151") (pin "P$3") (pinfunction "P$3_P$3") (pintype "bidirectional"))
      (node (ref "J153") (pin "P$1") (pinfunction "P$1_P$1") (pintype "bidirectional"))
      (node (ref "J153") (pin "P$2") (pinfunction "P$2_P$2") (pintype "bidirectional"))
      (node (ref "J153") (pin "P$3") (pinfunction "P$3_P$3") (pintype "bidirectional"))
      (node (ref "J5") (pin "2") (pinfunction "2_2") (pintype "passive"))
      (node (ref "J5") (pin "3") (pinfunction "3_3") (pintype "passive"))
      (node (ref "J7") (pin "P$1") (pinfunction "P$1_P$1") (pintype "bidirectional"))
      (node (ref "J7") (pin "P$2") (pinfunction "P$2_P$2") (pintype "bidirectional"))
      (node (ref "J70") (pin "P$1") (pinfunction "P$1_P$1") (pintype "bidirectional"))
      (node (ref "J70") (pin "P$2") (pinfunction "P$2_P$2") (pintype "bidirectional"))
      (node (ref "J72") (pin "P$1") (pinfunction "P$1_P$1") (pintype "bidirectional"))
      (node (ref "J72") (pin "P$2") (pinfunction "P$2_P$2") (pintype "bidirectional"))
      (node (ref "J74") (pin "P$1") (pinfunction "P$1_P$1") (pintype "bidirectional"))
      (node (ref "J74") (pin "P$2") (pinfunction "P$2_P$2") (pintype "bidirectional"))
      (node (ref "J76") (pin "P$1") (pinfunction "P$1_P$1") (pintype "bidirectional"))
      (node (ref "J76") (pin "P$2") (pinfunction "P$2_P$2") (pintype "bidirectional"))
      (node (ref "JP2") (pin "2") (pinfunction "2_2") (pintype "passive"))
      (node (ref "JP3") (pin "2") (pinfunction "2_2") (pintype "passive"))
      (node (ref "L1") (pin "P$20") (pinfunction "GND_1_P$20") (pintype "bidirectional"))
      (node (ref "L1") (pin "P$22") (pinfunction "GND_2_P$22") (pintype "bidirectional"))
      (node (ref "L1") (pin "P$60") (pinfunction "GND_3_P$60") (pintype "bidirectional"))
      (node (ref "L1") (pin "P$62") (pinfunction "GND_4_P$62") (pintype "bidirectional"))
      (node (ref "POWER") (pin "1") (pinfunction "1_1") (pintype "passive"))
      (node (ref "R3") (pin "1") (pinfunction "1_1") (pintype "passive"))
      (node (ref "R41") (pin "2") (pinfunction "2_2") (pintype "passive"))
      (node (ref "R43") (pin "2") (pinfunction "2_2") (pintype "passive"))
      (node (ref "R7") (pin "1") (pinfunction "1_1") (pintype "passive"))
      (node (ref "S1") (pin "P$1") (pinfunction "P1_P$1") (pintype "bidirectional"))
      (node (ref "S129") (pin "P$1") (pinfunction "P$1_P$1") (pintype "bidirectional"))
      (node (ref "S129") (pin "P$2") (pinfunction "P$2_P$2") (pintype "bidirectional"))
      (node (ref "S129") (pin "P$3") (pinfunction "P$3_P$3") (pintype "bidirectional"))
      (node (ref "S129") (pin "P$4") (pinfunction "P$4_P$4") (pintype "bidirectional"))
      (node (ref "S129") (pin "P$5") (pinfunction "P$5_P$5") (pintype "bidirectional"))
      (node (ref "S137") (pin "P$1") (pinfunction "P$1_P$1") (pintype "bidirectional"))
      (node (ref "S137") (pin "P$2") (pinfunction "P$2_P$2") (pintype "bidirectional"))
      (node (ref "S137") (pin "P$3") (pinfunction "P$3_P$3") (pintype "bidirectional"))
      (node (ref "S137") (pin "P$4") (pinfunction "P$4_P$4") (pintype "bidirectional"))
      (node (ref "S137") (pin "P$5") (pinfunction "P$5_P$5") (pintype "bidirectional"))
      (node (ref "S159") (pin "P$1") (pinfunction "P1_P$1") (pintype "bidirectional"))
      (node (ref "S20") (pin "P$1") (pinfunction "P$1_P$1") (pintype "bidirectional"))
      (node (ref "S20") (pin "P$10") (pinfunction "P$10_P$10") (pintype "bidirectional"))
      (node (ref "S20") (pin "P$2") (pinfunction "P$2_P$2") (pintype "bidirectional"))
      (node (ref "S20") (pin "P$3") (pinfunction "P$3_P$3") (pintype "bidirectional"))
      (node (ref "S20") (pin "P$4") (pinfunction "P$4_P$4") (pintype "bidirectional"))
      (node (ref "S20") (pin "P$5") (pinfunction "P$5_P$5") (pintype "bidirectional"))
      (node (ref "S20") (pin "P$6") (pinfunction "P$6_P$6") (pintype "bidirectional"))
      (node (ref "S20") (pin "P$7") (pinfunction "P$7_P$7") (pintype "bidirectional"))
      (node (ref "S20") (pin "P$8") (pinfunction "P$8_P$8") (pintype "bidirectional"))
      (node (ref "S20") (pin "P$9") (pinfunction "P$9_P$9") (pintype "bidirectional"))
      (node (ref "S24") (pin "P$1") (pinfunction "P$1_P$1") (pintype "bidirectional"))
      (node (ref "S24") (pin "P$10") (pinfunction "P$10_P$10") (pintype "bidirectional"))
      (node (ref "S24") (pin "P$2") (pinfunction "P$2_P$2") (pintype "bidirectional"))
      (node (ref "S24") (pin "P$3") (pinfunction "P$3_P$3") (pintype "bidirectional"))
      (node (ref "S24") (pin "P$4") (pinfunction "P$4_P$4") (pintype "bidirectional"))
      (node (ref "S24") (pin "P$5") (pinfunction "P$5_P$5") (pintype "bidirectional"))
      (node (ref "S24") (pin "P$6") (pinfunction "P$6_P$6") (pintype "bidirectional"))
      (node (ref "S24") (pin "P$7") (pinfunction "P$7_P$7") (pintype "bidirectional"))
      (node (ref "S24") (pin "P$8") (pinfunction "P$8_P$8") (pintype "bidirectional"))
      (node (ref "S24") (pin "P$9") (pinfunction "P$9_P$9") (pintype "bidirectional"))
      (node (ref "S28") (pin "P$1") (pinfunction "P$1_P$1") (pintype "bidirectional"))
      (node (ref "S28") (pin "P$10") (pinfunction "P$10_P$10") (pintype "bidirectional"))
      (node (ref "S28") (pin "P$2") (pinfunction "P$2_P$2") (pintype "bidirectional"))
      (node (ref "S28") (pin "P$3") (pinfunction "P$3_P$3") (pintype "bidirectional"))
      (node (ref "S28") (pin "P$4") (pinfunction "P$4_P$4") (pintype "bidirectional"))
      (node (ref "S28") (pin "P$5") (pinfunction "P$5_P$5") (pintype "bidirectional"))
      (node (ref "S28") (pin "P$6") (pinfunction "P$6_P$6") (pintype "bidirectional"))
      (node (ref "S28") (pin "P$7") (pinfunction "P$7_P$7") (pintype "bidirectional"))
      (node (ref "S28") (pin "P$8") (pinfunction "P$8_P$8") (pintype "bidirectional"))
      (node (ref "S28") (pin "P$9") (pinfunction "P$9_P$9") (pintype "bidirectional"))
      (node (ref "SV11") (pin "1") (pinfunction "1_1") (pintype "passive"))
      (node (ref "SV12") (pin "1") (pinfunction "1_1") (pintype "passive"))
      (node (ref "SV13") (pin "2") (pinfunction "2_2") (pintype "passive"))
      (node (ref "SV2") (pin "13") (pinfunction "13_13") (pintype "passive"))
      (node (ref "SV2") (pin "14") (pinfunction "14_14") (pintype "passive"))
      (node (ref "SV2") (pin "19") (pinfunction "19_19") (pintype "passive"))
      (node (ref "SV2") (pin "20") (pinfunction "20_20") (pintype "passive"))
      (node (ref "SV2") (pin "29") (pinfunction "29_29") (pintype "passive"))
      (node (ref "SV2") (pin "30") (pinfunction "30_30") (pintype "passive"))
      (node (ref "SV2") (pin "33") (pinfunction "33_33") (pintype "passive"))
      (node (ref "SV2") (pin "34") (pinfunction "34_34") (pintype "passive"))
      (node (ref "SV2") (pin "5") (pinfunction "5_5") (pintype "passive"))
      (node (ref "SV2") (pin "6") (pinfunction "6_6") (pintype "passive"))
      (node (ref "SV4") (pin "10") (pinfunction "10_10") (pintype "passive"))
      (node (ref "SV4") (pin "25") (pinfunction "25_25") (pintype "passive"))
      (node (ref "SV4") (pin "26") (pinfunction "26_26") (pintype "passive"))
      (node (ref "SV4") (pin "39") (pinfunction "39_39") (pintype "passive"))
      (node (ref "SV4") (pin "40") (pinfunction "40_40") (pintype "passive"))
      (node (ref "SV4") (pin "9") (pinfunction "9_9") (pintype "passive"))
      (node (ref "SV6") (pin "3") (pinfunction "3_3") (pintype "passive"))
      (node (ref "SV6") (pin "4") (pinfunction "4_4") (pintype "passive"))
      (node (ref "T1") (pin "3") (pinfunction "E_3") (pintype "passive"))
      (node (ref "T2") (pin "3") (pinfunction "E_3") (pintype "passive"))
      (node (ref "TRIMPOT1") (pin "5") (pinfunction "5_5") (pintype "passive"))
      (node (ref "TRIMPOT1") (pin "6") (pinfunction "6_6") (pintype "passive"))
      (node (ref "TRIMPOT2") (pin "5") (pinfunction "5_5") (pintype "passive"))
      (node (ref "TRIMPOT2") (pin "6") (pinfunction "6_6") (pintype "passive"))
      (node (ref "U$1") (pin "2") (pinfunction "P2_GND_2") (pintype "bidirectional"))
      (node (ref "U1") (pin "11") (pinfunction "SENSE_11") (pintype "bidirectional"))
      (node (ref "U1") (pin "12") (pinfunction "GND_12") (pintype "bidirectional"))
      (node (ref "U1") (pin "13") (pinfunction "GND_13") (pintype "bidirectional"))
      (node (ref "U1") (pin "4") (pinfunction "GND_4") (pintype "bidirectional"))
      (node (ref "U1") (pin "5") (pinfunction "GND_5") (pintype "bidirectional"))
      (node (ref "U2") (pin "P$15") (pinfunction "GND_P$15") (pintype "bidirectional"))
      (node (ref "U2") (pin "P$16") (pinfunction "PMODE_P$16") (pintype "bidirectional"))
      (node (ref "U2") (pin "P$17") (pinfunction "GND_PAD_P$17") (pintype "bidirectional"))
      (node (ref "U2") (pin "P$7") (pinfunction "IMODE_P$7") (pintype "bidirectional"))
      (node (ref "U2") (pin "P$9") (pinfunction "PGND_P$9") (pintype "bidirectional"))
      (node (ref "U3") (pin "4") (pinfunction "P4_GND_4") (pintype "bidirectional"))
      (node (ref "U4") (pin "P$15") (pinfunction "GND_P$15") (pintype "bidirectional"))
      (node (ref "U4") (pin "P$16") (pinfunction "PMODE_P$16") (pintype "bidirectional"))
      (node (ref "U4") (pin "P$17") (pinfunction "GND_PAD_P$17") (pintype "bidirectional"))
      (node (ref "U4") (pin "P$7") (pinfunction "IMODE_P$7") (pintype "bidirectional"))
      (node (ref "U4") (pin "P$9") (pinfunction "PGND_P$9") (pintype "bidirectional"))
      (node (ref "U5") (pin "11") (pinfunction "SENSE_11") (pintype "bidirectional"))
      (node (ref "U5") (pin "12") (pinfunction "GND_12") (pintype "bidirectional"))
      (node (ref "U5") (pin "13") (pinfunction "GND_13") (pintype "bidirectional"))
      (node (ref "U5") (pin "4") (pinfunction "GND_4") (pintype "bidirectional"))
      (node (ref "U5") (pin "5") (pinfunction "GND_5") (pintype "bidirectional"))
      (node (ref "U6") (pin "P$4") (pinfunction "V-_P$4") (pintype "bidirectional"))
      (node (ref "U7") (pin "4") (pinfunction "GND_4") (pintype "bidirectional"))
    )
    (net (code "28") (name "GPIO0") (class "Default")
      (node (ref "J11") (pin "P$1") (pinfunction "P$1_P$1") (pintype "bidirectional"))
      (node (ref "J11") (pin "P$2") (pinfunction "P$2_P$2") (pintype "bidirectional"))
      (node (ref "J122") (pin "P$1") (pinfunction "P$1_P$1") (pintype "bidirectional"))
      (node (ref "J122") (pin "P$2") (pinfunction "P$2_P$2") (pintype "bidirectional"))
      (node (ref "J122") (pin "P$3") (pinfunction "P$3_P$3") (pintype "bidirectional"))
      (node (ref "L1") (pin "P$40") (pinfunction "GPIO0/EPWM1A_P$40") (pintype "bidirectional"))
    )
    (net (code "29") (name "GPIO1") (class "Default")
      (node (ref "J121") (pin "P$1") (pinfunction "P$1_P$1") (pintype "bidirectional"))
      (node (ref "J121") (pin "P$2") (pinfunction "P$2_P$2") (pintype "bidirectional"))
      (node (ref "J121") (pin "P$3") (pinfunction "P$3_P$3") (pintype "bidirectional"))
      (node (ref "L1") (pin "P$39") (pinfunction "GPIO1/EPWM1B_P$39") (pintype "bidirectional"))
      (node (ref "SV13") (pin "5") (pinfunction "5_5") (pintype "passive"))
    )
    (net (code "30") (name "GPIO2") (class "Default")
      (node (ref "J120") (pin "P$1") (pinfunction "P$1_P$1") (pintype "bidirectional"))
      (node (ref "J120") (pin "P$2") (pinfunction "P$2_P$2") (pintype "bidirectional"))
      (node (ref "J120") (pin "P$3") (pinfunction "P$3_P$3") (pintype "bidirectional"))
      (node (ref "J198") (pin "P$1") (pinfunction "P$1_P$1") (pintype "bidirectional"))
      (node (ref "J198") (pin "P$2") (pinfunction "P$2_P$2") (pintype "bidirectional"))
      (node (ref "L1") (pin "P$38") (pinfunction "GPIO2/EPWM2A_P$38") (pintype "bidirectional"))
    )
    (net (code "31") (name "GPIO3") (class "Default")
      (node (ref "J119") (pin "P$1") (pinfunction "P$1_P$1") (pintype "bidirectional"))
      (node (ref "J119") (pin "P$2") (pinfunction "P$2_P$2") (pintype "bidirectional"))
      (node (ref "J119") (pin "P$3") (pinfunction "P$3_P$3") (pintype "bidirectional"))
      (node (ref "J199") (pin "P$1") (pinfunction "P$1_P$1") (pintype "bidirectional"))
      (node (ref "J199") (pin "P$2") (pinfunction "P$2_P$2") (pintype "bidirectional"))
      (node (ref "L1") (pin "P$37") (pinfunction "GPIO3/EPWM2B_P$37") (pintype "bidirectional"))
    )
    (net (code "32") (name "GPIO4") (class "Default")
      (node (ref "J118") (pin "P$1") (pinfunction "P$1_P$1") (pintype "bidirectional"))
      (node (ref "J118") (pin "P$2") (pinfunction "P$2_P$2") (pintype "bidirectional"))
      (node (ref "J118") (pin "P$3") (pinfunction "P$3_P$3") (pintype "bidirectional"))
      (node (ref "J71") (pin "P$1") (pinfunction "P$1_P$1") (pintype "bidirectional"))
      (node (ref "J71") (pin "P$2") (pinfunction "P$2_P$2") (pintype "bidirectional"))
      (node (ref "L1") (pin "P$36") (pinfunction "GPIO4/EPWM3A_P$36") (pintype "bidirectional"))
    )
    (net (code "33") (name "GPIO5") (class "Default")
      (node (ref "J117") (pin "P$1") (pinfunction "P$1_P$1") (pintype "bidirectional"))
      (node (ref "J117") (pin "P$2") (pinfunction "P$2_P$2") (pintype "bidirectional"))
      (node (ref "J117") (pin "P$3") (pinfunction "P$3_P$3") (pintype "bidirectional"))
      (node (ref "J73") (pin "P$1") (pinfunction "P$1_P$1") (pintype "bidirectional"))
      (node (ref "J73") (pin "P$2") (pinfunction "P$2_P$2") (pintype "bidirectional"))
      (node (ref "L1") (pin "P$35") (pinfunction "GPIO5/EPWM3B_P$35") (pintype "bidirectional"))
    )
    (net (code "34") (name "GPIO6") (class "Default")
      (node (ref "J133") (pin "P$1") (pinfunction "P$1_P$1") (pintype "bidirectional"))
      (node (ref "J133") (pin "P$2") (pinfunction "P$2_P$2") (pintype "bidirectional"))
      (node (ref "J133") (pin "P$3") (pinfunction "P$3_P$3") (pintype "bidirectional"))
      (node (ref "J75") (pin "P$1") (pinfunction "P$1_P$1") (pintype "bidirectional"))
      (node (ref "J75") (pin "P$2") (pinfunction "P$2_P$2") (pintype "bidirectional"))
      (node (ref "L1") (pin "P$80") (pinfunction "GPIO6/EPWM4A_P$80") (pintype "bidirectional"))
    )
    (net (code "35") (name "GPIO7") (class "Default")
      (node (ref "J134") (pin "P$1") (pinfunction "P$1_P$1") (pintype "bidirectional"))
      (node (ref "J134") (pin "P$2") (pinfunction "P$2_P$2") (pintype "bidirectional"))
      (node (ref "J134") (pin "P$3") (pinfunction "P$3_P$3") (pintype "bidirectional"))
      (node (ref "J77") (pin "P$1") (pinfunction "P$1_P$1") (pintype "bidirectional"))
      (node (ref "J77") (pin "P$2") (pinfunction "P$2_P$2") (pintype "bidirectional"))
      (node (ref "L1") (pin "P$79") (pinfunction "GPIO7/EPWM4B_P$79") (pintype "bidirectional"))
    )
    (net (code "36") (name "GPIO8") (class "Default")
      (node (ref "J135") (pin "P$1") (pinfunction "P$1_P$1") (pintype "bidirectional"))
      (node (ref "J135") (pin "P$2") (pinfunction "P$2_P$2") (pintype "bidirectional"))
      (node (ref "J135") (pin "P$3") (pinfunction "P$3_P$3") (pintype "bidirectional"))
      (node (ref "L1") (pin "P$78") (pinfunction "GPIO8/EPWM5A_P$78") (pintype "bidirectional"))
      (node (ref "SV11") (pin "5") (pinfunction "5_5") (pintype "passive"))
    )
    (net (code "37") (name "GPIO9") (class "Default")
      (node (ref "J136") (pin "P$1") (pinfunction "P$1_P$1") (pintype "bidirectional"))
      (node (ref "J136") (pin "P$2") (pinfunction "P$2_P$2") (pintype "bidirectional"))
      (node (ref "J136") (pin "P$3") (pinfunction "P$3_P$3") (pintype "bidirectional"))
      (node (ref "L1") (pin "P$77") (pinfunction "GPIO9/EPWM5B_P$77") (pintype "bidirectional"))
    )
    (net (code "38") (name "GPIO10") (class "Default")
      (node (ref "J137") (pin "P$1") (pinfunction "P$1_P$1") (pintype "bidirectional"))
      (node (ref "J137") (pin "P$2") (pinfunction "P$2_P$2") (pintype "bidirectional"))
      (node (ref "J137") (pin "P$3") (pinfunction "P$3_P$3") (pintype "bidirectional"))
      (node (ref "J84") (pin "P$1") (pinfunction "P$1_P$1") (pintype "bidirectional"))
      (node (ref "J84") (pin "P$2") (pinfunction "P$2_P$2") (pintype "bidirectional"))
      (node (ref "L1") (pin "P$76") (pinfunction "GPIO10/EPWM6A_P$76") (pintype "bidirectional"))
    )
    (net (code "39") (name "GPIO11") (class "Default")
      (node (ref "J138") (pin "P$1") (pinfunction "P$1_P$1") (pintype "bidirectional"))
      (node (ref "J138") (pin "P$2") (pinfunction "P$2_P$2") (pintype "bidirectional"))
      (node (ref "J138") (pin "P$3") (pinfunction "P$3_P$3") (pintype "bidirectional"))
      (node (ref "J86") (pin "P$1") (pinfunction "P$1_P$1") (pintype "bidirectional"))
      (node (ref "J86") (pin "P$2") (pinfunction "P$2_P$2") (pintype "bidirectional"))
      (node (ref "L1") (pin "P$75") (pinfunction "GPIO11/EPWM6B_P$75") (pintype "bidirectional"))
    )
    (net (code "40") (name "GPIO14") (class "Default")
      (node (ref "J139") (pin "P$1") (pinfunction "P$1_P$1") (pintype "bidirectional"))
      (node (ref "J139") (pin "P$2") (pinfunction "P$2_P$2") (pintype "bidirectional"))
      (node (ref "J139") (pin "P$3") (pinfunction "P$3_P$3") (pintype "bidirectional"))
      (node (ref "J201") (pin "P$1") (pinfunction "P$1_P$1") (pintype "bidirectional"))
      (node (ref "J201") (pin "P$2") (pinfunction "P$2_P$2") (pintype "bidirectional"))
      (node (ref "L1") (pin "P$74") (pinfunction "GPIO14_P$74") (pintype "bidirectional"))
    )
    (net (code "41") (name "GPIO15") (class "Default")
      (node (ref "J140") (pin "P$1") (pinfunction "P$1_P$1") (pintype "bidirectional"))
      (node (ref "J140") (pin "P$2") (pinfunction "P$2_P$2") (pintype "bidirectional"))
      (node (ref "J140") (pin "P$3") (pinfunction "P$3_P$3") (pintype "bidirectional"))
      (node (ref "J202") (pin "P$1") (pinfunction "P$1_P$1") (pintype "bidirectional"))
      (node (ref "J202") (pin "P$2") (pinfunction "P$2_P$2") (pintype "bidirectional"))
      (node (ref "L1") (pin "P$73") (pinfunction "GPIO15_P$73") (pintype "bidirectional"))
    )
    (net (code "42") (name "GPIO16") (class "Default")
      (node (ref "J115") (pin "P$1") (pinfunction "P$1_P$1") (pintype "bidirectional"))
      (node (ref "J115") (pin "P$2") (pinfunction "P$2_P$2") (pintype "bidirectional"))
      (node (ref "J115") (pin "P$3") (pinfunction "P$3_P$3") (pintype "bidirectional"))
      (node (ref "J251") (pin "P$1") (pinfunction "P$1_P$1") (pintype "bidirectional"))
      (node (ref "J251") (pin "P$2") (pinfunction "P$2_P$2") (pintype "bidirectional"))
      (node (ref "L1") (pin "P$33") (pinfunction "GPIO16_P$33") (pintype "bidirectional"))
    )
    (net (code "43") (name "GPIO18") (class "Default")
      (node (ref "J16") (pin "P$1") (pinfunction "P$1_P$1") (pintype "bidirectional"))
      (node (ref "J16") (pin "P$2") (pinfunction "P$2_P$2") (pintype "bidirectional"))
      (node (ref "J16") (pin "P$3") (pinfunction "P$3_P$3") (pintype "bidirectional"))
      (node (ref "L1") (pin "P$4") (pinfunction "GPIO18/SCITXDB_P$4") (pintype "bidirectional"))
      (node (ref "U7") (pin "6") (pinfunction "SCK_6") (pintype "bidirectional"))
    )
    (net (code "44") (name "GPIO19") (class "Default")
      (node (ref "J15") (pin "P$1") (pinfunction "P$1_P$1") (pintype "bidirectional"))
      (node (ref "J15") (pin "P$2") (pinfunction "P$2_P$2") (pintype "bidirectional"))
      (node (ref "J15") (pin "P$3") (pinfunction "P$3_P$3") (pintype "bidirectional"))
      (node (ref "L1") (pin "P$3") (pinfunction "GPIO19/SCIRXDB_P$3") (pintype "bidirectional"))
      (node (ref "U7") (pin "1") (pinfunction "~{CS}_1") (pintype "bidirectional"))
    )
    (net (code "45") (name "GPIO22") (class "Default")
      (node (ref "IC1") (pin "1") (pinfunction "I_1") (pintype "input"))
      (node (ref "J20") (pin "P$1") (pinfunction "P$1_P$1") (pintype "bidirectional"))
      (node (ref "J20") (pin "P$2") (pinfunction "P$2_P$2") (pintype "bidirectional"))
      (node (ref "J20") (pin "P$3") (pinfunction "P$3_P$3") (pintype "bidirectional"))
      (node (ref "L1") (pin "P$8") (pinfunction "GPIO22_P$8") (pintype "bidirectional"))
    )
    (net (code "46") (name "GPIO24") (class "Default")
      (node (ref "J116") (pin "P$1") (pinfunction "P$1_P$1") (pintype "bidirectional"))
      (node (ref "J116") (pin "P$2") (pinfunction "P$2_P$2") (pintype "bidirectional"))
      (node (ref "J116") (pin "P$3") (pinfunction "P$3_P$3") (pintype "bidirectional"))
      (node (ref "J9") (pin "P$1") (pinfunction "P$1_P$1") (pintype "bidirectional"))
      (node (ref "J9") (pin "P$2") (pinfunction "P$2_P$2") (pintype "bidirectional"))
      (node (ref "L1") (pin "P$34") (pinfunction "GPIO24_P$34") (pintype "bidirectional"))
    )
    (net (code "47") (name "GPIO25") (class "Default")
      (node (ref "IC2") (pin "3") (pinfunction "I_3") (pintype "input"))
      (node (ref "J162") (pin "P$1") (pinfunction "P$1_P$1") (pintype "bidirectional"))
      (node (ref "J162") (pin "P$2") (pinfunction "P$2_P$2") (pintype "bidirectional"))
      (node (ref "J162") (pin "P$3") (pinfunction "P$3_P$3") (pintype "bidirectional"))
      (node (ref "L1") (pin "P$51") (pinfunction "GPIO25_P$51") (pintype "bidirectional"))
    )
    (net (code "48") (name "GPIO26") (class "Default")
      (node (ref "IC2") (pin "5") (pinfunction "I_5") (pintype "input"))
      (node (ref "J160") (pin "P$1") (pinfunction "P$1_P$1") (pintype "bidirectional"))
      (node (ref "J160") (pin "P$2") (pinfunction "P$2_P$2") (pintype "bidirectional"))
      (node (ref "J160") (pin "P$3") (pinfunction "P$3_P$3") (pintype "bidirectional"))
      (node (ref "L1") (pin "P$53") (pinfunction "GPIO26_P$53") (pintype "bidirectional"))
    )
    (net (code "49") (name "GPIO27") (class "Default")
      (node (ref "IC2") (pin "9") (pinfunction "I_9") (pintype "input"))
      (node (ref "J161") (pin "P$1") (pinfunction "P$1_P$1") (pintype "bidirectional"))
      (node (ref "J161") (pin "P$2") (pinfunction "P$2_P$2") (pintype "bidirectional"))
      (node (ref "J161") (pin "P$3") (pinfunction "P$3_P$3") (pintype "bidirectional"))
      (node (ref "L1") (pin "P$52") (pinfunction "GPIO27_P$52") (pintype "bidirectional"))
    )
    (net (code "50") (name "GPIO29") (class "Default")
      (node (ref "J29") (pin "P$1") (pinfunction "P$1_P$1") (pintype "bidirectional"))
      (node (ref "J29") (pin "P$2") (pinfunction "P$2_P$2") (pintype "bidirectional"))
      (node (ref "J29") (pin "P$3") (pinfunction "P$3_P$3") (pintype "bidirectional"))
      (node (ref "J85") (pin "P$1") (pinfunction "P$1_P$1") (pintype "bidirectional"))
      (node (ref "J85") (pin "P$2") (pinfunction "P$2_P$2") (pintype "bidirectional"))
      (node (ref "L1") (pin "P$11") (pinfunction "GPIO29_P$11") (pintype "bidirectional"))
    )
    (net (code "51") (name "GPIO32") (class "Default")
      (node (ref "J14") (pin "P$1") (pinfunction "P$1_P$1") (pintype "bidirectional"))
      (node (ref "J14") (pin "P$2") (pinfunction "P$2_P$2") (pintype "bidirectional"))
      (node (ref "J14") (pin "P$3") (pinfunction "P$3_P$3") (pintype "bidirectional"))
      (node (ref "J87") (pin "P$1") (pinfunction "P$1_P$1") (pintype "bidirectional"))
      (node (ref "J87") (pin "P$2") (pinfunction "P$2_P$2") (pintype "bidirectional"))
      (node (ref "L1") (pin "P$2") (pinfunction "GPIO32_P$2") (pintype "bidirectional"))
    )
    (net (code "52") (name "GPIO40") (class "Default")
      (node (ref "J163") (pin "P$1") (pinfunction "P$1_P$1") (pintype "bidirectional"))
      (node (ref "J163") (pin "P$2") (pinfunction "P$2_P$2") (pintype "bidirectional"))
      (node (ref "J163") (pin "P$3") (pinfunction "P$3_P$3") (pintype "bidirectional"))
      (node (ref "J208") (pin "P$1") (pinfunction "P$1_P$1") (pintype "bidirectional"))
      (node (ref "J208") (pin "P$2") (pinfunction "P$2_P$2") (pintype "bidirectional"))
      (node (ref "L1") (pin "P$50") (pinfunction "GPIO40/SDAB_P$50") (pintype "bidirectional"))
      (node (ref "R9") (pin "2") (pinfunction "2_2") (pintype "passive"))
    )
    (net (code "53") (name "GPIO41") (class "Default")
      (node (ref "J164") (pin "P$1") (pinfunction "P$1_P$1") (pintype "bidirectional"))
      (node (ref "J164") (pin "P$2") (pinfunction "P$2_P$2") (pintype "bidirectional"))
      (node (ref "J164") (pin "P$3") (pinfunction "P$3_P$3") (pintype "bidirectional"))
      (node (ref "J209") (pin "P$1") (pinfunction "P$1_P$1") (pintype "bidirectional"))
      (node (ref "J209") (pin "P$2") (pinfunction "P$2_P$2") (pintype "bidirectional"))
      (node (ref "L1") (pin "P$49") (pinfunction "GPIO41/SCLB_P$49") (pintype "bidirectional"))
      (node (ref "R10") (pin "2") (pinfunction "2_2") (pintype "passive"))
    )
    (net (code "54") (name "GPIO52") (class "Default")
      (node (ref "J165") (pin "P$1") (pinfunction "P$1_P$1") (pintype "bidirectional"))
      (node (ref "J165") (pin "P$2") (pinfunction "P$2_P$2") (pintype "bidirectional"))
      (node (ref "J165") (pin "P$3") (pinfunction "P$3_P$3") (pintype "bidirectional"))
      (node (ref "L1") (pin "P$48") (pinfunction "GPIO52_P$48") (pintype "bidirectional"))
    )
    (net (code "55") (name "GPIO56") (class "Default")
      (node (ref "J169") (pin "P$1") (pinfunction "P$1_P$1") (pintype "bidirectional"))
      (node (ref "J169") (pin "P$2") (pinfunction "P$2_P$2") (pintype "bidirectional"))
      (node (ref "J169") (pin "P$3") (pinfunction "P$3_P$3") (pintype "bidirectional"))
      (node (ref "L1") (pin "P$44") (pinfunction "GPIO56/SCITXDC_P$44") (pintype "bidirectional"))
      (node (ref "SV13") (pin "8") (pinfunction "8_8") (pintype "passive"))
    )
    (net (code "56") (name "GPIO58") (class "Default")
      (node (ref "J33") (pin "P$1") (pinfunction "P$1_P$1") (pintype "bidirectional"))
      (node (ref "J33") (pin "P$2") (pinfunction "P$2_P$2") (pintype "bidirectional"))
      (node (ref "J33") (pin "P$3") (pinfunction "P$3_P$3") (pintype "bidirectional"))
      (node (ref "L1") (pin "P$15") (pinfunction "GPIO58/SPISIMOA_P$15") (pintype "bidirectional"))
      (node (ref "U7") (pin "5") (pinfunction "SI_5") (pintype "bidirectional"))
    )
    (net (code "57") (name "GPIO59") (class "Default")
      (node (ref "J32") (pin "P$1") (pinfunction "P$1_P$1") (pintype "bidirectional"))
      (node (ref "J32") (pin "P$2") (pinfunction "P$2_P$2") (pintype "bidirectional"))
      (node (ref "J32") (pin "P$3") (pinfunction "P$3_P$3") (pintype "bidirectional"))
      (node (ref "L1") (pin "P$14") (pinfunction "GPIO59/SPISOMIA_P$14") (pintype "bidirectional"))
      (node (ref "U7") (pin "2") (pinfunction "SO_2") (pintype "bidirectional"))
    )
    (net (code "58") (name "GPIO60") (class "Default")
      (node (ref "IC2") (pin "11") (pinfunction "I_11") (pintype "input"))
      (node (ref "J19") (pin "P$1") (pinfunction "P$1_P$1") (pintype "bidirectional"))
      (node (ref "J19") (pin "P$2") (pinfunction "P$2_P$2") (pintype "bidirectional"))
      (node (ref "J19") (pin "P$3") (pinfunction "P$3_P$3") (pintype "bidirectional"))
      (node (ref "L1") (pin "P$7") (pinfunction "GPIO60/SPICLKA_P$7") (pintype "bidirectional"))
    )
    (net (code "59") (name "GPIO61") (class "Default")
      (node (ref "IC2") (pin "13") (pinfunction "I_13") (pintype "input"))
      (node (ref "J101") (pin "P$1") (pinfunction "P$1_P$1") (pintype "bidirectional"))
      (node (ref "J101") (pin "P$2") (pinfunction "P$2_P$2") (pintype "bidirectional"))
      (node (ref "J101") (pin "P$3") (pinfunction "P$3_P$3") (pintype "bidirectional"))
      (node (ref "L1") (pin "P$19") (pinfunction "GPIO61_P$19") (pintype "bidirectional"))
    )
    (net (code "60") (name "GPIO63") (class "Default")
      (node (ref "J158") (pin "P$1") (pinfunction "P$1_P$1") (pintype "bidirectional"))
      (node (ref "J158") (pin "P$2") (pinfunction "P$2_P$2") (pintype "bidirectional"))
      (node (ref "J158") (pin "P$3") (pinfunction "P$3_P$3") (pintype "bidirectional"))
      (node (ref "J204") (pin "P$1") (pinfunction "P$1_P$1") (pintype "bidirectional"))
      (node (ref "J204") (pin "P$2") (pinfunction "P$2_P$2") (pintype "bidirectional"))
      (node (ref "L1") (pin "P$55") (pinfunction "GPIO63/SPISIMOB_P$55") (pintype "bidirectional"))
    )
    (net (code "61") (name "GPIO64") (class "Default")
      (node (ref "J159") (pin "P$1") (pinfunction "P$1_P$1") (pintype "bidirectional"))
      (node (ref "J159") (pin "P$2") (pinfunction "P$2_P$2") (pintype "bidirectional"))
      (node (ref "J159") (pin "P$3") (pinfunction "P$3_P$3") (pintype "bidirectional"))
      (node (ref "J205") (pin "P$1") (pinfunction "P$1_P$1") (pintype "bidirectional"))
      (node (ref "J205") (pin "P$2") (pinfunction "P$2_P$2") (pintype "bidirectional"))
      (node (ref "L1") (pin "P$54") (pinfunction "GPIO64/SPISOMIB_P$54") (pintype "bidirectional"))
    )
    (net (code "62") (name "GPIO65") (class "Default")
      (node (ref "J166") (pin "P$1") (pinfunction "P$1_P$1") (pintype "bidirectional"))
      (node (ref "J166") (pin "P$2") (pinfunction "P$2_P$2") (pintype "bidirectional"))
      (node (ref "J166") (pin "P$3") (pinfunction "P$3_P$3") (pintype "bidirectional"))
      (node (ref "J206") (pin "P$1") (pinfunction "P$1_P$1") (pintype "bidirectional"))
      (node (ref "J206") (pin "P$2") (pinfunction "P$2_P$2") (pintype "bidirectional"))
      (node (ref "L1") (pin "P$47") (pinfunction "GPIO65/SPICLKB_P$47") (pintype "bidirectional"))
    )
    (net (code "63") (name "GPIO66") (class "Default")
      (node (ref "J154") (pin "P$1") (pinfunction "P$1_P$1") (pintype "bidirectional"))
      (node (ref "J154") (pin "P$2") (pinfunction "P$2_P$2") (pintype "bidirectional"))
      (node (ref "J154") (pin "P$3") (pinfunction "P$3_P$3") (pintype "bidirectional"))
      (node (ref "J207") (pin "P$1") (pinfunction "P$1_P$1") (pintype "bidirectional"))
      (node (ref "J207") (pin "P$2") (pinfunction "P$2_P$2") (pintype "bidirectional"))
      (node (ref "L1") (pin "P$59") (pinfunction "GPIO66_P$59") (pintype "bidirectional"))
    )
    (net (code "64") (name "GPIO67") (class "Default")
      (node (ref "J17") (pin "P$1") (pinfunction "P$1_P$1") (pintype "bidirectional"))
      (node (ref "J17") (pin "P$2") (pinfunction "P$2_P$2") (pintype "bidirectional"))
      (node (ref "J17") (pin "P$3") (pinfunction "P$3_P$3") (pintype "bidirectional"))
      (node (ref "L1") (pin "P$5") (pinfunction "GPIO67_P$5") (pintype "bidirectional"))
    )
    (net (code "65") (name "GPIO94") (class "Default")
      (node (ref "IC1") (pin "3") (pinfunction "I_3") (pintype "input"))
      (node (ref "J167") (pin "P$1") (pinfunction "P$1_P$1") (pintype "bidirectional"))
      (node (ref "J167") (pin "P$2") (pinfunction "P$2_P$2") (pintype "bidirectional"))
      (node (ref "J167") (pin "P$3") (pinfunction "P$3_P$3") (pintype "bidirectional"))
      (node (ref "L1") (pin "P$46") (pinfunction "GPIO94_P$46") (pintype "bidirectional"))
    )
    (net (code "66") (name "GPIO95") (class "Default")
      (node (ref "IC1") (pin "5") (pinfunction "I_5") (pintype "input"))
      (node (ref "J176") (pin "P$1") (pinfunction "P$1_P$1") (pintype "bidirectional"))
      (node (ref "J176") (pin "P$2") (pinfunction "P$2_P$2") (pintype "bidirectional"))
      (node (ref "J176") (pin "P$3") (pinfunction "P$3_P$3") (pintype "bidirectional"))
      (node (ref "L1") (pin "P$42") (pinfunction "GPIO95_P$42") (pintype "bidirectional"))
    )
    (net (code "67") (name "GPIO97") (class "Default")
      (node (ref "IC1") (pin "9") (pinfunction "I_9") (pintype "input"))
      (node (ref "J168") (pin "P$1") (pinfunction "P$1_P$1") (pintype "bidirectional"))
      (node (ref "J168") (pin "P$2") (pinfunction "P$2_P$2") (pintype "bidirectional"))
      (node (ref "J168") (pin "P$3") (pinfunction "P$3_P$3") (pintype "bidirectional"))
      (node (ref "L1") (pin "P$45") (pinfunction "GPIO97_P$45") (pintype "bidirectional"))
    )
    (net (code "68") (name "GPIO104") (class "Default")
      (node (ref "J28") (pin "P$1") (pinfunction "P$1_P$1") (pintype "bidirectional"))
      (node (ref "J28") (pin "P$2") (pinfunction "P$2_P$2") (pintype "bidirectional"))
      (node (ref "J28") (pin "P$3") (pinfunction "P$3_P$3") (pintype "bidirectional"))
      (node (ref "L1") (pin "P$10") (pinfunction "GPIO104/SDAA_P$10") (pintype "bidirectional"))
    )
    (net (code "69") (name "GPIO105") (class "Default")
      (node (ref "J21") (pin "P$1") (pinfunction "P$1_P$1") (pintype "bidirectional"))
      (node (ref "J21") (pin "P$2") (pinfunction "P$2_P$2") (pintype "bidirectional"))
      (node (ref "J21") (pin "P$3") (pinfunction "P$3_P$3") (pintype "bidirectional"))
      (node (ref "L1") (pin "P$9") (pinfunction "GPIO105/SCLA_P$9") (pintype "bidirectional"))
    )
    (net (code "70") (name "GPIO111") (class "Default")
      (node (ref "IC1") (pin "11") (pinfunction "I_11") (pintype "input"))
      (node (ref "J18") (pin "P$1") (pinfunction "P$1_P$1") (pintype "bidirectional"))
      (node (ref "J18") (pin "P$2") (pinfunction "P$2_P$2") (pintype "bidirectional"))
      (node (ref "J18") (pin "P$3") (pinfunction "P$3_P$3") (pintype "bidirectional"))
      (node (ref "L1") (pin "P$6") (pinfunction "GPIO111_P$6") (pintype "bidirectional"))
    )
    (net (code "71") (name "GPIO122") (class "Default")
      (node (ref "J66") (pin "P$1") (pinfunction "P$1_P$1") (pintype "bidirectional"))
      (node (ref "J66") (pin "P$2") (pinfunction "P$2_P$2") (pintype "bidirectional"))
      (node (ref "J99") (pin "P$1") (pinfunction "P$1_P$1") (pintype "bidirectional"))
      (node (ref "J99") (pin "P$2") (pinfunction "P$2_P$2") (pintype "bidirectional"))
      (node (ref "J99") (pin "P$3") (pinfunction "P$3_P$3") (pintype "bidirectional"))
      (node (ref "L1") (pin "P$17") (pinfunction "GPIO122_P$17") (pintype "bidirectional"))
    )
    (net (code "72") (name "GPIO123") (class "Default")
      (node (ref "J100") (pin "P$1") (pinfunction "P$1_P$1") (pintype "bidirectional"))
      (node (ref "J100") (pin "P$2") (pinfunction "P$2_P$2") (pintype "bidirectional"))
      (node (ref "J100") (pin "P$3") (pinfunction "P$3_P$3") (pintype "bidirectional"))
      (node (ref "J67") (pin "P$1") (pinfunction "P$1_P$1") (pintype "bidirectional"))
      (node (ref "J67") (pin "P$2") (pinfunction "P$2_P$2") (pintype "bidirectional"))
      (node (ref "L1") (pin "P$18") (pinfunction "GPIO123_P$18") (pintype "bidirectional"))
    )
    (net (code "73") (name "GPIO124") (class "Default")
      (node (ref "J31") (pin "P$1") (pinfunction "P$1_P$1") (pintype "bidirectional"))
      (node (ref "J31") (pin "P$2") (pinfunction "P$2_P$2") (pintype "bidirectional"))
      (node (ref "J31") (pin "P$3") (pinfunction "P$3_P$3") (pintype "bidirectional"))
      (node (ref "J68") (pin "P$1") (pinfunction "P$1_P$1") (pintype "bidirectional"))
      (node (ref "J68") (pin "P$2") (pinfunction "P$2_P$2") (pintype "bidirectional"))
      (node (ref "L1") (pin "P$13") (pinfunction "GPIO124_P$13") (pintype "bidirectional"))
    )
    (net (code "74") (name "GPIO125") (class "Default")
      (node (ref "J30") (pin "P$1") (pinfunction "P$1_P$1") (pintype "bidirectional"))
      (node (ref "J30") (pin "P$2") (pinfunction "P$2_P$2") (pintype "bidirectional"))
      (node (ref "J30") (pin "P$3") (pinfunction "P$3_P$3") (pintype "bidirectional"))
      (node (ref "J69") (pin "P$1") (pinfunction "P$1_P$1") (pintype "bidirectional"))
      (node (ref "J69") (pin "P$2") (pinfunction "P$2_P$2") (pintype "bidirectional"))
      (node (ref "L1") (pin "P$12") (pinfunction "GPIO125_P$12") (pintype "bidirectional"))
    )
    (net (code "75") (name "GPIO130") (class "Default")
      (node (ref "IC1") (pin "13") (pinfunction "I_13") (pintype "input"))
      (node (ref "J156") (pin "P$1") (pinfunction "P$1_P$1") (pintype "bidirectional"))
      (node (ref "J156") (pin "P$2") (pinfunction "P$2_P$2") (pintype "bidirectional"))
      (node (ref "J156") (pin "P$3") (pinfunction "P$3_P$3") (pintype "bidirectional"))
      (node (ref "L1") (pin "P$57") (pinfunction "GPIO130_P$57") (pintype "bidirectional"))
    )
    (net (code "76") (name "GPIO131") (class "Default")
      (node (ref "IC2") (pin "1") (pinfunction "I_1") (pintype "input"))
      (node (ref "J155") (pin "P$1") (pinfunction "P$1_P$1") (pintype "bidirectional"))
      (node (ref "J155") (pin "P$2") (pinfunction "P$2_P$2") (pintype "bidirectional"))
      (node (ref "J155") (pin "P$3") (pinfunction "P$3_P$3") (pintype "bidirectional"))
      (node (ref "L1") (pin "P$58") (pinfunction "GPIO131_P$58") (pintype "bidirectional"))
    )
    (net (code "77") (name "GPIO139") (class "Default")
      (node (ref "J170") (pin "P$1") (pinfunction "P$1_P$1") (pintype "bidirectional"))
      (node (ref "J170") (pin "P$2") (pinfunction "P$2_P$2") (pintype "bidirectional"))
      (node (ref "J170") (pin "P$3") (pinfunction "P$3_P$3") (pintype "bidirectional"))
      (node (ref "L1") (pin "P$43") (pinfunction "GPIO139/SCIRXDC_P$43") (pintype "bidirectional"))
      (node (ref "SV13") (pin "1") (pinfunction "1_1") (pintype "passive"))
    )
    (net (code "78") (name "GPIO157") (class "Default")
      (node (ref "IC3") (pin "1") (pinfunction "I_1") (pintype "input"))
      (node (ref "J141") (pin "P$1") (pinfunction "P$1_P$1") (pintype "bidirectional"))
      (node (ref "J141") (pin "P$2") (pinfunction "P$2_P$2") (pintype "bidirectional"))
      (node (ref "J141") (pin "P$3") (pinfunction "P$3_P$3") (pintype "bidirectional"))
      (node (ref "L1") (pin "P$72") (pinfunction "DAC3_P$72") (pintype "bidirectional"))
    )
    (net (code "79") (name "GPIO158") (class "Default")
      (node (ref "IC3") (pin "3") (pinfunction "I_3") (pintype "input"))
      (node (ref "J142") (pin "P$1") (pinfunction "P$1_P$1") (pintype "bidirectional"))
      (node (ref "J142") (pin "P$2") (pinfunction "P$2_P$2") (pintype "bidirectional"))
      (node (ref "J142") (pin "P$3") (pinfunction "P$3_P$3") (pintype "bidirectional"))
      (node (ref "L1") (pin "P$71") (pinfunction "DAC4_P$71") (pintype "bidirectional"))
    )
    (net (code "80") (name "GPIO159") (class "Default")
      (node (ref "IC3") (pin "5") (pinfunction "I_5") (pintype "input"))
      (node (ref "J114") (pin "P$1") (pinfunction "P$1_P$1") (pintype "bidirectional"))
      (node (ref "J114") (pin "P$2") (pinfunction "P$2_P$2") (pintype "bidirectional"))
      (node (ref "J114") (pin "P$3") (pinfunction "P$3_P$3") (pintype "bidirectional"))
      (node (ref "L1") (pin "P$32") (pinfunction "DAC1_P$32") (pintype "bidirectional"))
    )
    (net (code "81") (name "GPIO160") (class "Default")
      (node (ref "IC3") (pin "9") (pinfunction "I_9") (pintype "input"))
      (node (ref "J113") (pin "P$1") (pinfunction "P$1_P$1") (pintype "bidirectional"))
      (node (ref "J113") (pin "P$2") (pinfunction "P$2_P$2") (pintype "bidirectional"))
      (node (ref "J113") (pin "P$3") (pinfunction "P$3_P$3") (pintype "bidirectional"))
      (node (ref "L1") (pin "P$31") (pinfunction "DAC2_P$31") (pintype "bidirectional"))
    )
    (net (code "82") (name "MENABLE") (class "Default")
      (node (ref "S159") (pin "P$2") (pinfunction "P2_P$2") (pintype "bidirectional"))
      (node (ref "U2") (pin "P$3") (pinfunction "NSLEEP_P$3") (pintype "bidirectional"))
      (node (ref "U4") (pin "P$3") (pinfunction "NSLEEP_P$3") (pintype "bidirectional"))
    )
    (net (code "83") (name "MOTOR1+") (class "Default")
      (node (ref "SV3") (pin "1") (pinfunction "1_1") (pintype "passive"))
      (node (ref "SV3") (pin "3") (pinfunction "3_3") (pintype "passive"))
      (node (ref "SV3") (pin "5") (pinfunction "5_5") (pintype "passive"))
      (node (ref "U1") (pin "15") (pinfunction "OUTB_15") (pintype "bidirectional"))
    )
    (net (code "84") (name "MOTOR1-") (class "Default")
      (node (ref "SV3") (pin "2") (pinfunction "2_2") (pintype "passive"))
      (node (ref "SV3") (pin "4") (pinfunction "4_4") (pintype "passive"))
      (node (ref "SV3") (pin "6") (pinfunction "6_6") (pintype "passive"))
      (node (ref "U1") (pin "10") (pinfunction "OUTA_10") (pintype "bidirectional"))
    )
    (net (code "85") (name "MOTOR2+") (class "Default")
      (node (ref "SV1") (pin "1") (pinfunction "1_1") (pintype "passive"))
      (node (ref "SV1") (pin "3") (pinfunction "3_3") (pintype "passive"))
      (node (ref "SV1") (pin "5") (pinfunction "5_5") (pintype "passive"))
      (node (ref "U5") (pin "15") (pinfunction "OUTB_15") (pintype "bidirectional"))
    )
    (net (code "86") (name "MOTOR2-") (class "Default")
      (node (ref "SV1") (pin "2") (pinfunction "2_2") (pintype "passive"))
      (node (ref "SV1") (pin "4") (pinfunction "4_4") (pintype "passive"))
      (node (ref "SV1") (pin "6") (pinfunction "6_6") (pintype "passive"))
      (node (ref "U5") (pin "10") (pinfunction "OUTA_10") (pintype "bidirectional"))
    )
    (net (code "87") (name "Net-(3V3-PadA)") (class "Default")
      (node (ref "3V3") (pin "A") (pinfunction "A_A") (pintype "passive"))
      (node (ref "R27") (pin "1") (pinfunction "1_1") (pintype "passive"))
    )
    (net (code "88") (name "Net-(5V-PadA)") (class "Default")
      (node (ref "5V") (pin "A") (pinfunction "A_A") (pintype "passive"))
      (node (ref "R26") (pin "1") (pinfunction "1_1") (pintype "passive"))
    )
    (net (code "89") (name "Net-(B1-PadP$1)") (class "Default")
      (node (ref "B1") (pin "P$1") (pinfunction "P$1_P$1") (pintype "bidirectional"))
      (node (ref "R40") (pin "2") (pinfunction "2_2") (pintype "passive"))
    )
    (net (code "90") (name "Net-(B4-P1)") (class "Default")
      (node (ref "B4") (pin "P$1") (pinfunction "P1_P$1") (pintype "bidirectional"))
      (node (ref "SV10") (pin "1") (pinfunction "1_1") (pintype "passive"))
      (node (ref "U6") (pin "P$1") (pinfunction "IN1_P$1") (pintype "bidirectional"))
    )
    (net (code "91") (name "Net-(B5-P1)") (class "Default")
      (node (ref "B5") (pin "P$1") (pinfunction "P1_P$1") (pintype "bidirectional"))
      (node (ref "SV9") (pin "2") (pinfunction "2_2") (pintype "passive"))
      (node (ref "U6") (pin "P$6") (pinfunction "OUT2_P$6") (pintype "bidirectional"))
    )
    (net (code "92") (name "Net-(ETH1-INT{slash})") (class "Default")
      (node (ref "ETH1") (pin "P$6") (pinfunction "INT/_P$6") (pintype "bidirectional"))
      (node (ref "SV5") (pin "7") (pinfunction "7_7") (pintype "passive"))
      (node (ref "SV5") (pin "8") (pinfunction "8_8") (pintype "passive"))
    )
    (net (code "93") (name "Net-(ETH1-MISO)") (class "Default")
      (node (ref "ETH1") (pin "P$7") (pinfunction "MISO_P$7") (pintype "bidirectional"))
      (node (ref "SV5") (pin "10") (pinfunction "10_10") (pintype "passive"))
      (node (ref "SV5") (pin "9") (pinfunction "9_9") (pintype "passive"))
    )
    (net (code "94") (name "Net-(ETH1-MOSI)") (class "Default")
      (node (ref "ETH1") (pin "P$3") (pinfunction "MOSI_P$3") (pintype "bidirectional"))
      (node (ref "SV6") (pin "10") (pinfunction "10_10") (pintype "passive"))
      (node (ref "SV6") (pin "9") (pinfunction "9_9") (pintype "passive"))
    )
    (net (code "95") (name "Net-(ETH1-RESET)") (class "Default")
      (node (ref "ETH1") (pin "P$8") (pinfunction "RESET_P$8") (pintype "bidirectional"))
      (node (ref "SV6") (pin "7") (pinfunction "7_7") (pintype "passive"))
      (node (ref "SV6") (pin "8") (pinfunction "8_8") (pintype "passive"))
    )
    (net (code "96") (name "Net-(ETH1-SCLK)") (class "Default")
      (node (ref "ETH1") (pin "P$4") (pinfunction "SCLK_P$4") (pintype "bidirectional"))
      (node (ref "SV6") (pin "11") (pinfunction "11_11") (pintype "passive"))
      (node (ref "SV6") (pin "12") (pinfunction "12_12") (pintype "passive"))
    )
    (net (code "97") (name "Net-(ETH1-SS{slash})") (class "Default")
      (node (ref "ETH1") (pin "P$5") (pinfunction "SS/_P$5") (pintype "bidirectional"))
      (node (ref "SV5") (pin "11") (pinfunction "11_11") (pintype "passive"))
      (node (ref "SV5") (pin "12") (pinfunction "12_12") (pintype "passive"))
    )
    (net (code "98") (name "Net-(IC1A-O)") (class "Default")
      (node (ref "IC1") (pin "2") (pinfunction "O_2") (pintype "output"))
      (node (ref "LED1") (pin "C") (pinfunction "C_C") (pintype "passive"))
    )
    (net (code "99") (name "Net-(IC1B-O)") (class "Default")
      (node (ref "IC1") (pin "4") (pinfunction "O_4") (pintype "output"))
      (node (ref "LED2") (pin "C") (pinfunction "C_C") (pintype "passive"))
    )
    (net (code "100") (name "Net-(IC1C-O)") (class "Default")
      (node (ref "IC1") (pin "6") (pinfunction "O_6") (pintype "output"))
      (node (ref "LED3") (pin "C") (pinfunction "C_C") (pintype "passive"))
    )
    (net (code "101") (name "Net-(IC1D-O)") (class "Default")
      (node (ref "IC1") (pin "8") (pinfunction "O_8") (pintype "output"))
      (node (ref "LED4") (pin "C") (pinfunction "C_C") (pintype "passive"))
    )
    (net (code "102") (name "Net-(IC1E-O)") (class "Default")
      (node (ref "IC1") (pin "10") (pinfunction "O_10") (pintype "output"))
      (node (ref "LED5") (pin "C") (pinfunction "C_C") (pintype "passive"))
    )
    (net (code "103") (name "Net-(IC1F-O)") (class "Default")
      (node (ref "IC1") (pin "12") (pinfunction "O_12") (pintype "output"))
      (node (ref "LED6") (pin "C") (pinfunction "C_C") (pintype "passive"))
    )
    (net (code "104") (name "Net-(IC2A-O)") (class "Default")
      (node (ref "IC2") (pin "2") (pinfunction "O_2") (pintype "output"))
      (node (ref "LED7") (pin "C") (pinfunction "C_C") (pintype "passive"))
    )
    (net (code "105") (name "Net-(IC2B-O)") (class "Default")
      (node (ref "IC2") (pin "4") (pinfunction "O_4") (pintype "output"))
      (node (ref "LED8") (pin "C") (pinfunction "C_C") (pintype "passive"))
    )
    (net (code "106") (name "Net-(IC2C-O)") (class "Default")
      (node (ref "IC2") (pin "6") (pinfunction "O_6") (pintype "output"))
      (node (ref "LED9") (pin "C") (pinfunction "C_C") (pintype "passive"))
    )
    (net (code "107") (name "Net-(IC2D-O)") (class "Default")
      (node (ref "IC2") (pin "8") (pinfunction "O_8") (pintype "output"))
      (node (ref "LED10") (pin "C") (pinfunction "C_C") (pintype "passive"))
    )
    (net (code "108") (name "Net-(IC2E-O)") (class "Default")
      (node (ref "IC2") (pin "10") (pinfunction "O_10") (pintype "output"))
      (node (ref "LED11") (pin "C") (pinfunction "C_C") (pintype "passive"))
    )
    (net (code "109") (name "Net-(IC2F-O)") (class "Default")
      (node (ref "IC2") (pin "12") (pinfunction "O_12") (pintype "output"))
      (node (ref "LED12") (pin "C") (pinfunction "C_C") (pintype "passive"))
    )
    (net (code "110") (name "Net-(IC3A-O)") (class "Default")
      (node (ref "IC3") (pin "2") (pinfunction "O_2") (pintype "output"))
      (node (ref "LED13") (pin "C") (pinfunction "C_C") (pintype "passive"))
    )
    (net (code "111") (name "Net-(IC3B-O)") (class "Default")
      (node (ref "IC3") (pin "4") (pinfunction "O_4") (pintype "output"))
      (node (ref "LED14") (pin "C") (pinfunction "C_C") (pintype "passive"))
    )
    (net (code "112") (name "Net-(IC3C-O)") (class "Default")
      (node (ref "IC3") (pin "6") (pinfunction "O_6") (pintype "output"))
      (node (ref "LED15") (pin "C") (pinfunction "C_C") (pintype "passive"))
    )
    (net (code "113") (name "Net-(IC3D-O)") (class "Default")
      (node (ref "IC3") (pin "8") (pinfunction "O_8") (pintype "output"))
      (node (ref "LED16") (pin "C") (pinfunction "C_C") (pintype "passive"))
    )
    (net (code "114") (name "Net-(IC3E-I)") (class "Default")
      (node (ref "IC3") (pin "11") (pinfunction "I_11") (pintype "input"))
      (node (ref "J194") (pin "P$1") (pinfunction "P$1_P$1") (pintype "bidirectional"))
      (node (ref "J194") (pin "P$2") (pinfunction "P$2_P$2") (pintype "bidirectional"))
    )
    (net (code "115") (name "Net-(IC3E-O)") (class "Default")
      (node (ref "IC3") (pin "10") (pinfunction "O_10") (pintype "output"))
      (node (ref "R40") (pin "1") (pinfunction "1_1") (pintype "passive"))
    )
    (net (code "116") (name "Net-(J6-PadP$1)") (class "Default")
      (node (ref "J6") (pin "P$1") (pinfunction "P$1_P$1") (pintype "bidirectional"))
      (node (ref "J6") (pin "P$2") (pinfunction "P$2_P$2") (pintype "bidirectional"))
      (node (ref "J6") (pin "P$3") (pinfunction "P$3_P$3") (pintype "bidirectional"))
      (node (ref "R1") (pin "1") (pinfunction "1_1") (pintype "passive"))
    )
    (net (code "117") (name "Net-(J24-PadP$1)") (class "Default")
      (node (ref "J24") (pin "P$1") (pinfunction "P$1_P$1") (pintype "bidirectional"))
      (node (ref "J24") (pin "P$2") (pinfunction "P$2_P$2") (pintype "bidirectional"))
      (node (ref "J24") (pin "P$3") (pinfunction "P$3_P$3") (pintype "bidirectional"))
      (node (ref "R2") (pin "1") (pinfunction "1_1") (pintype "passive"))
    )
    (net (code "118") (name "Net-(J88-PadP$1)") (class "Default")
      (node (ref "J88") (pin "P$1") (pinfunction "P$1_P$1") (pintype "bidirectional"))
      (node (ref "J91") (pin "P$1") (pinfunction "P$1_P$1") (pintype "bidirectional"))
      (node (ref "J91") (pin "P$2") (pinfunction "P$2_P$2") (pintype "bidirectional"))
    )
    (net (code "119") (name "Net-(J88-PadP$3)") (class "Default")
      (node (ref "J88") (pin "P$3") (pinfunction "P$3_P$3") (pintype "bidirectional"))
      (node (ref "J92") (pin "P$1") (pinfunction "P$1_P$1") (pintype "bidirectional"))
      (node (ref "J92") (pin "P$2") (pinfunction "P$2_P$2") (pintype "bidirectional"))
    )
    (net (code "120") (name "Net-(J88-PadP$4)") (class "Default")
      (node (ref "J88") (pin "P$4") (pinfunction "P$4_P$4") (pintype "bidirectional"))
      (node (ref "J93") (pin "P$1") (pinfunction "P$1_P$1") (pintype "bidirectional"))
      (node (ref "J93") (pin "P$2") (pinfunction "P$2_P$2") (pintype "bidirectional"))
    )
    (net (code "121") (name "Net-(J88-R+)") (class "Default")
      (node (ref "J88") (pin "P$2") (pinfunction "R+_P$2") (pintype "bidirectional"))
      (node (ref "J89") (pin "P$1") (pinfunction "P$1_P$1") (pintype "bidirectional"))
      (node (ref "J89") (pin "P$2") (pinfunction "P$2_P$2") (pintype "bidirectional"))
    )
    (net (code "122") (name "Net-(J88-R-)") (class "Default")
      (node (ref "J88") (pin "P$5") (pinfunction "R-_P$5") (pintype "bidirectional"))
      (node (ref "J90") (pin "P$1") (pinfunction "P$1_P$1") (pintype "bidirectional"))
      (node (ref "J90") (pin "P$2") (pinfunction "P$2_P$2") (pintype "bidirectional"))
    )
    (net (code "123") (name "Net-(LED1-PadA)") (class "Default")
      (node (ref "LED1") (pin "A") (pinfunction "A_A") (pintype "passive"))
      (node (ref "R11") (pin "1") (pinfunction "1_1") (pintype "passive"))
    )
    (net (code "124") (name "Net-(LED2-PadA)") (class "Default")
      (node (ref "LED2") (pin "A") (pinfunction "A_A") (pintype "passive"))
      (node (ref "R12") (pin "1") (pinfunction "1_1") (pintype "passive"))
    )
    (net (code "125") (name "Net-(LED3-PadA)") (class "Default")
      (node (ref "LED3") (pin "A") (pinfunction "A_A") (pintype "passive"))
      (node (ref "R13") (pin "1") (pinfunction "1_1") (pintype "passive"))
    )
    (net (code "126") (name "Net-(LED4-PadA)") (class "Default")
      (node (ref "LED4") (pin "A") (pinfunction "A_A") (pintype "passive"))
      (node (ref "R14") (pin "1") (pinfunction "1_1") (pintype "passive"))
    )
    (net (code "127") (name "Net-(LED5-PadA)") (class "Default")
      (node (ref "LED5") (pin "A") (pinfunction "A_A") (pintype "passive"))
      (node (ref "R15") (pin "1") (pinfunction "1_1") (pintype "passive"))
    )
    (net (code "128") (name "Net-(LED6-PadA)") (class "Default")
      (node (ref "LED6") (pin "A") (pinfunction "A_A") (pintype "passive"))
      (node (ref "R16") (pin "1") (pinfunction "1_1") (pintype "passive"))
    )
    (net (code "129") (name "Net-(LED7-PadA)") (class "Default")
      (node (ref "LED7") (pin "A") (pinfunction "A_A") (pintype "passive"))
      (node (ref "R17") (pin "1") (pinfunction "1_1") (pintype "passive"))
    )
    (net (code "130") (name "Net-(LED8-PadA)") (class "Default")
      (node (ref "LED8") (pin "A") (pinfunction "A_A") (pintype "passive"))
      (node (ref "R19") (pin "1") (pinfunction "1_1") (pintype "passive"))
    )
    (net (code "131") (name "Net-(LED9-PadA)") (class "Default")
      (node (ref "LED9") (pin "A") (pinfunction "A_A") (pintype "passive"))
      (node (ref "R20") (pin "1") (pinfunction "1_1") (pintype "passive"))
    )
    (net (code "132") (name "Net-(LED10-PadA)") (class "Default")
      (node (ref "LED10") (pin "A") (pinfunction "A_A") (pintype "passive"))
      (node (ref "R21") (pin "1") (pinfunction "1_1") (pintype "passive"))
    )
    (net (code "133") (name "Net-(LED11-PadA)") (class "Default")
      (node (ref "LED11") (pin "A") (pinfunction "A_A") (pintype "passive"))
      (node (ref "R22") (pin "1") (pinfunction "1_1") (pintype "passive"))
    )
    (net (code "134") (name "Net-(LED12-PadA)") (class "Default")
      (node (ref "LED12") (pin "A") (pinfunction "A_A") (pintype "passive"))
      (node (ref "R23") (pin "1") (pinfunction "1_1") (pintype "passive"))
    )
    (net (code "135") (name "Net-(LED13-PadA)") (class "Default")
      (node (ref "LED13") (pin "A") (pinfunction "A_A") (pintype "passive"))
      (node (ref "R28") (pin "1") (pinfunction "1_1") (pintype "passive"))
    )
    (net (code "136") (name "Net-(LED14-PadA)") (class "Default")
      (node (ref "LED14") (pin "A") (pinfunction "A_A") (pintype "passive"))
      (node (ref "R29") (pin "1") (pinfunction "1_1") (pintype "passive"))
    )
    (net (code "137") (name "Net-(LED15-PadA)") (class "Default")
      (node (ref "LED15") (pin "A") (pinfunction "A_A") (pintype "passive"))
      (node (ref "R30") (pin "1") (pinfunction "1_1") (pintype "passive"))
    )
    (net (code "138") (name "Net-(LED16-PadA)") (class "Default")
      (node (ref "LED16") (pin "A") (pinfunction "A_A") (pintype "passive"))
      (node (ref "R31") (pin "1") (pinfunction "1_1") (pintype "passive"))
    )
    (net (code "139") (name "Net-(S1-P3)") (class "Default")
      (node (ref "R24") (pin "1") (pinfunction "1_1") (pintype "passive"))
      (node (ref "S1") (pin "P$3") (pinfunction "P3_P$3") (pintype "bidirectional"))
    )
    (net (code "140") (name "Net-(S97-PadP$1)") (class "Default")
      (node (ref "S97") (pin "P$1") (pinfunction "P$1_P$1") (pintype "bidirectional"))
      (node (ref "S97") (pin "P$2") (pinfunction "P$2_P$2") (pintype "bidirectional"))
      (node (ref "S97") (pin "P$3") (pinfunction "P$3_P$3") (pintype "bidirectional"))
      (node (ref "S97") (pin "P$4") (pinfunction "P$4_P$4") (pintype "bidirectional"))
      (node (ref "S97") (pin "P$5") (pinfunction "P$5_P$5") (pintype "bidirectional"))
    )
    (net (code "141") (name "Net-(S98-PadP$1)") (class "Default")
      (node (ref "S98") (pin "P$1") (pinfunction "P$1_P$1") (pintype "bidirectional"))
      (node (ref "S98") (pin "P$2") (pinfunction "P$2_P$2") (pintype "bidirectional"))
      (node (ref "S98") (pin "P$3") (pinfunction "P$3_P$3") (pintype "bidirectional"))
      (node (ref "S98") (pin "P$4") (pinfunction "P$4_P$4") (pintype "bidirectional"))
      (node (ref "S98") (pin "P$5") (pinfunction "P$5_P$5") (pintype "bidirectional"))
    )
    (net (code "142") (name "Net-(S99-PadP$1)") (class "Default")
      (node (ref "S99") (pin "P$1") (pinfunction "P$1_P$1") (pintype "bidirectional"))
      (node (ref "S99") (pin "P$2") (pinfunction "P$2_P$2") (pintype "bidirectional"))
      (node (ref "S99") (pin "P$3") (pinfunction "P$3_P$3") (pintype "bidirectional"))
      (node (ref "S99") (pin "P$4") (pinfunction "P$4_P$4") (pintype "bidirectional"))
      (node (ref "S99") (pin "P$5") (pinfunction "P$5_P$5") (pintype "bidirectional"))
    )
    (net (code "143") (name "Net-(S101-PadP$1)") (class "Default")
      (node (ref "S101") (pin "P$1") (pinfunction "P$1_P$1") (pintype "bidirectional"))
      (node (ref "S101") (pin "P$2") (pinfunction "P$2_P$2") (pintype "bidirectional"))
      (node (ref "S101") (pin "P$3") (pinfunction "P$3_P$3") (pintype "bidirectional"))
      (node (ref "S101") (pin "P$4") (pinfunction "P$4_P$4") (pintype "bidirectional"))
      (node (ref "S101") (pin "P$5") (pinfunction "P$5_P$5") (pintype "bidirectional"))
    )
    (net (code "144") (name "Net-(S105-PadP$1)") (class "Default")
      (node (ref "S105") (pin "P$1") (pinfunction "P$1_P$1") (pintype "bidirectional"))
      (node (ref "S105") (pin "P$2") (pinfunction "P$2_P$2") (pintype "bidirectional"))
      (node (ref "S105") (pin "P$3") (pinfunction "P$3_P$3") (pintype "bidirectional"))
      (node (ref "S105") (pin "P$4") (pinfunction "P$4_P$4") (pintype "bidirectional"))
      (node (ref "S105") (pin "P$5") (pinfunction "P$5_P$5") (pintype "bidirectional"))
    )
    (net (code "145") (name "Net-(S108-PadP$1)") (class "Default")
      (node (ref "S108") (pin "P$1") (pinfunction "P$1_P$1") (pintype "bidirectional"))
      (node (ref "S108") (pin "P$2") (pinfunction "P$2_P$2") (pintype "bidirectional"))
      (node (ref "S108") (pin "P$3") (pinfunction "P$3_P$3") (pintype "bidirectional"))
      (node (ref "S108") (pin "P$4") (pinfunction "P$4_P$4") (pintype "bidirectional"))
      (node (ref "S108") (pin "P$5") (pinfunction "P$5_P$5") (pintype "bidirectional"))
    )
    (net (code "146") (name "Net-(S130-PadP$1)") (class "Default")
      (node (ref "S130") (pin "P$1") (pinfunction "P$1_P$1") (pintype "bidirectional"))
      (node (ref "S130") (pin "P$2") (pinfunction "P$2_P$2") (pintype "bidirectional"))
      (node (ref "S130") (pin "P$3") (pinfunction "P$3_P$3") (pintype "bidirectional"))
      (node (ref "S130") (pin "P$4") (pinfunction "P$4_P$4") (pintype "bidirectional"))
      (node (ref "S130") (pin "P$5") (pinfunction "P$5_P$5") (pintype "bidirectional"))
    )
    (net (code "147") (name "Net-(S138-PadP$1)") (class "Default")
      (node (ref "S138") (pin "P$1") (pinfunction "P$1_P$1") (pintype "bidirectional"))
      (node (ref "S138") (pin "P$2") (pinfunction "P$2_P$2") (pintype "bidirectional"))
      (node (ref "S138") (pin "P$3") (pinfunction "P$3_P$3") (pintype "bidirectional"))
      (node (ref "S138") (pin "P$4") (pinfunction "P$4_P$4") (pintype "bidirectional"))
      (node (ref "S138") (pin "P$5") (pinfunction "P$5_P$5") (pintype "bidirectional"))
    )
    (net (code "148") (name "Net-(S139-PadP$1)") (class "Default")
      (node (ref "S139") (pin "P$1") (pinfunction "P$1_P$1") (pintype "bidirectional"))
      (node (ref "S139") (pin "P$2") (pinfunction "P$2_P$2") (pintype "bidirectional"))
      (node (ref "S139") (pin "P$3") (pinfunction "P$3_P$3") (pintype "bidirectional"))
      (node (ref "S139") (pin "P$4") (pinfunction "P$4_P$4") (pintype "bidirectional"))
      (node (ref "S139") (pin "P$5") (pinfunction "P$5_P$5") (pintype "bidirectional"))
    )
    (net (code "149") (name "Net-(S140-PadP$1)") (class "Default")
      (node (ref "S140") (pin "P$1") (pinfunction "P$1_P$1") (pintype "bidirectional"))
      (node (ref "S140") (pin "P$2") (pinfunction "P$2_P$2") (pintype "bidirectional"))
      (node (ref "S140") (pin "P$3") (pinfunction "P$3_P$3") (pintype "bidirectional"))
      (node (ref "S140") (pin "P$4") (pinfunction "P$4_P$4") (pintype "bidirectional"))
      (node (ref "S140") (pin "P$5") (pinfunction "P$5_P$5") (pintype "bidirectional"))
    )
    (net (code "150") (name "Net-(S147-PadP$1)") (class "Default")
      (node (ref "S147") (pin "P$1") (pinfunction "P$1_P$1") (pintype "bidirectional"))
      (node (ref "S147") (pin "P$2") (pinfunction "P$2_P$2") (pintype "bidirectional"))
      (node (ref "S147") (pin "P$3") (pinfunction "P$3_P$3") (pintype "bidirectional"))
      (node (ref "S147") (pin "P$4") (pinfunction "P$4_P$4") (pintype "bidirectional"))
      (node (ref "S147") (pin "P$5") (pinfunction "P$5_P$5") (pintype "bidirectional"))
    )
    (net (code "151") (name "Net-(S159-P3)") (class "Default")
      (node (ref "R18") (pin "1") (pinfunction "1_1") (pintype "passive"))
      (node (ref "S159") (pin "P$3") (pinfunction "P3_P$3") (pintype "bidirectional"))
    )
    (net (code "152") (name "Net-(S160-PadP$1)") (class "Default")
      (node (ref "S160") (pin "P$1") (pinfunction "P$1_P$1") (pintype "bidirectional"))
      (node (ref "S160") (pin "P$2") (pinfunction "P$2_P$2") (pintype "bidirectional"))
      (node (ref "S160") (pin "P$3") (pinfunction "P$3_P$3") (pintype "bidirectional"))
      (node (ref "S160") (pin "P$4") (pinfunction "P$4_P$4") (pintype "bidirectional"))
      (node (ref "S160") (pin "P$5") (pinfunction "P$5_P$5") (pintype "bidirectional"))
    )
    (net (code "153") (name "Net-(S161-PadP$1)") (class "Default")
      (node (ref "S161") (pin "P$1") (pinfunction "P$1_P$1") (pintype "bidirectional"))
      (node (ref "S161") (pin "P$2") (pinfunction "P$2_P$2") (pintype "bidirectional"))
      (node (ref "S161") (pin "P$3") (pinfunction "P$3_P$3") (pintype "bidirectional"))
      (node (ref "S161") (pin "P$4") (pinfunction "P$4_P$4") (pintype "bidirectional"))
      (node (ref "S161") (pin "P$5") (pinfunction "P$5_P$5") (pintype "bidirectional"))
    )
    (net (code "154") (name "Net-(S162-PadP$1)") (class "Default")
      (node (ref "S162") (pin "P$1") (pinfunction "P$1_P$1") (pintype "bidirectional"))
      (node (ref "S162") (pin "P$2") (pinfunction "P$2_P$2") (pintype "bidirectional"))
      (node (ref "S162") (pin "P$3") (pinfunction "P$3_P$3") (pintype "bidirectional"))
      (node (ref "S162") (pin "P$4") (pinfunction "P$4_P$4") (pintype "bidirectional"))
      (node (ref "S162") (pin "P$5") (pinfunction "P$5_P$5") (pintype "bidirectional"))
    )
    (net (code "155") (name "Net-(S163-PadP$1)") (class "Default")
      (node (ref "S163") (pin "P$1") (pinfunction "P$1_P$1") (pintype "bidirectional"))
      (node (ref "S163") (pin "P$2") (pinfunction "P$2_P$2") (pintype "bidirectional"))
      (node (ref "S163") (pin "P$3") (pinfunction "P$3_P$3") (pintype "bidirectional"))
      (node (ref "S163") (pin "P$4") (pinfunction "P$4_P$4") (pintype "bidirectional"))
      (node (ref "S163") (pin "P$5") (pinfunction "P$5_P$5") (pintype "bidirectional"))
    )
    (net (code "156") (name "Net-(S164-PadP$1)") (class "Default")
      (node (ref "S164") (pin "P$1") (pinfunction "P$1_P$1") (pintype "bidirectional"))
      (node (ref "S164") (pin "P$2") (pinfunction "P$2_P$2") (pintype "bidirectional"))
      (node (ref "S164") (pin "P$3") (pinfunction "P$3_P$3") (pintype "bidirectional"))
      (node (ref "S164") (pin "P$4") (pinfunction "P$4_P$4") (pintype "bidirectional"))
      (node (ref "S164") (pin "P$5") (pinfunction "P$5_P$5") (pintype "bidirectional"))
    )
    (net (code "157") (name "Net-(S165-PadP$1)") (class "Default")
      (node (ref "S165") (pin "P$1") (pinfunction "P$1_P$1") (pintype "bidirectional"))
      (node (ref "S165") (pin "P$2") (pinfunction "P$2_P$2") (pintype "bidirectional"))
      (node (ref "S165") (pin "P$3") (pinfunction "P$3_P$3") (pintype "bidirectional"))
      (node (ref "S165") (pin "P$4") (pinfunction "P$4_P$4") (pintype "bidirectional"))
      (node (ref "S165") (pin "P$5") (pinfunction "P$5_P$5") (pintype "bidirectional"))
    )
    (net (code "158") (name "Net-(S166-PadP$1)") (class "Default")
      (node (ref "S166") (pin "P$1") (pinfunction "P$1_P$1") (pintype "bidirectional"))
      (node (ref "S166") (pin "P$2") (pinfunction "P$2_P$2") (pintype "bidirectional"))
      (node (ref "S166") (pin "P$3") (pinfunction "P$3_P$3") (pintype "bidirectional"))
      (node (ref "S166") (pin "P$4") (pinfunction "P$4_P$4") (pintype "bidirectional"))
      (node (ref "S166") (pin "P$5") (pinfunction "P$5_P$5") (pintype "bidirectional"))
    )
    (net (code "159") (name "Net-(S167-PadP$1)") (class "Default")
      (node (ref "S167") (pin "P$1") (pinfunction "P$1_P$1") (pintype "bidirectional"))
      (node (ref "S167") (pin "P$2") (pinfunction "P$2_P$2") (pintype "bidirectional"))
      (node (ref "S167") (pin "P$3") (pinfunction "P$3_P$3") (pintype "bidirectional"))
      (node (ref "S167") (pin "P$4") (pinfunction "P$4_P$4") (pintype "bidirectional"))
      (node (ref "S167") (pin "P$5") (pinfunction "P$5_P$5") (pintype "bidirectional"))
    )
    (net (code "160") (name "Net-(S168-PadP$1)") (class "Default")
      (node (ref "S168") (pin "P$1") (pinfunction "P$1_P$1") (pintype "bidirectional"))
      (node (ref "S168") (pin "P$2") (pinfunction "P$2_P$2") (pintype "bidirectional"))
      (node (ref "S168") (pin "P$3") (pinfunction "P$3_P$3") (pintype "bidirectional"))
      (node (ref "S168") (pin "P$4") (pinfunction "P$4_P$4") (pintype "bidirectional"))
      (node (ref "S168") (pin "P$5") (pinfunction "P$5_P$5") (pintype "bidirectional"))
    )
    (net (code "161") (name "Net-(S169-PadP$1)") (class "Default")
      (node (ref "S169") (pin "P$1") (pinfunction "P$1_P$1") (pintype "bidirectional"))
      (node (ref "S169") (pin "P$2") (pinfunction "P$2_P$2") (pintype "bidirectional"))
      (node (ref "S169") (pin "P$3") (pinfunction "P$3_P$3") (pintype "bidirectional"))
      (node (ref "S169") (pin "P$4") (pinfunction "P$4_P$4") (pintype "bidirectional"))
      (node (ref "S169") (pin "P$5") (pinfunction "P$5_P$5") (pintype "bidirectional"))
    )
    (net (code "162") (name "Net-(S170-PadP$1)") (class "Default")
      (node (ref "S170") (pin "P$1") (pinfunction "P$1_P$1") (pintype "bidirectional"))
      (node (ref "S170") (pin "P$2") (pinfunction "P$2_P$2") (pintype "bidirectional"))
      (node (ref "S170") (pin "P$3") (pinfunction "P$3_P$3") (pintype "bidirectional"))
      (node (ref "S170") (pin "P$4") (pinfunction "P$4_P$4") (pintype "bidirectional"))
      (node (ref "S170") (pin "P$5") (pinfunction "P$5_P$5") (pintype "bidirectional"))
    )
    (net (code "163") (name "Net-(S171-PadP$1)") (class "Default")
      (node (ref "S171") (pin "P$1") (pinfunction "P$1_P$1") (pintype "bidirectional"))
      (node (ref "S171") (pin "P$2") (pinfunction "P$2_P$2") (pintype "bidirectional"))
      (node (ref "S171") (pin "P$3") (pinfunction "P$3_P$3") (pintype "bidirectional"))
      (node (ref "S171") (pin "P$4") (pinfunction "P$4_P$4") (pintype "bidirectional"))
      (node (ref "S171") (pin "P$5") (pinfunction "P$5_P$5") (pintype "bidirectional"))
    )
    (net (code "164") (name "Net-(S172-PadP$1)") (class "Default")
      (node (ref "S172") (pin "P$1") (pinfunction "P$1_P$1") (pintype "bidirectional"))
      (node (ref "S172") (pin "P$2") (pinfunction "P$2_P$2") (pintype "bidirectional"))
      (node (ref "S172") (pin "P$3") (pinfunction "P$3_P$3") (pintype "bidirectional"))
      (node (ref "S172") (pin "P$4") (pinfunction "P$4_P$4") (pintype "bidirectional"))
      (node (ref "S172") (pin "P$5") (pinfunction "P$5_P$5") (pintype "bidirectional"))
    )
    (net (code "165") (name "Net-(S173-PadP$1)") (class "Default")
      (node (ref "S173") (pin "P$1") (pinfunction "P$1_P$1") (pintype "bidirectional"))
      (node (ref "S173") (pin "P$2") (pinfunction "P$2_P$2") (pintype "bidirectional"))
      (node (ref "S173") (pin "P$3") (pinfunction "P$3_P$3") (pintype "bidirectional"))
      (node (ref "S173") (pin "P$4") (pinfunction "P$4_P$4") (pintype "bidirectional"))
      (node (ref "S173") (pin "P$5") (pinfunction "P$5_P$5") (pintype "bidirectional"))
    )
    (net (code "166") (name "Net-(S174-PadP$1)") (class "Default")
      (node (ref "S174") (pin "P$1") (pinfunction "P$1_P$1") (pintype "bidirectional"))
      (node (ref "S174") (pin "P$2") (pinfunction "P$2_P$2") (pintype "bidirectional"))
      (node (ref "S174") (pin "P$3") (pinfunction "P$3_P$3") (pintype "bidirectional"))
      (node (ref "S174") (pin "P$4") (pinfunction "P$4_P$4") (pintype "bidirectional"))
      (node (ref "S174") (pin "P$5") (pinfunction "P$5_P$5") (pintype "bidirectional"))
    )
    (net (code "167") (name "Net-(S175-PadP$1)") (class "Default")
      (node (ref "S175") (pin "P$1") (pinfunction "P$1_P$1") (pintype "bidirectional"))
      (node (ref "S175") (pin "P$2") (pinfunction "P$2_P$2") (pintype "bidirectional"))
      (node (ref "S175") (pin "P$3") (pinfunction "P$3_P$3") (pintype "bidirectional"))
      (node (ref "S175") (pin "P$4") (pinfunction "P$4_P$4") (pintype "bidirectional"))
      (node (ref "S175") (pin "P$5") (pinfunction "P$5_P$5") (pintype "bidirectional"))
    )
    (net (code "168") (name "Net-(S176-PadP$1)") (class "Default")
      (node (ref "S176") (pin "P$1") (pinfunction "P$1_P$1") (pintype "bidirectional"))
      (node (ref "S176") (pin "P$2") (pinfunction "P$2_P$2") (pintype "bidirectional"))
      (node (ref "S176") (pin "P$3") (pinfunction "P$3_P$3") (pintype "bidirectional"))
      (node (ref "S176") (pin "P$4") (pinfunction "P$4_P$4") (pintype "bidirectional"))
      (node (ref "S176") (pin "P$5") (pinfunction "P$5_P$5") (pintype "bidirectional"))
    )
    (net (code "169") (name "Net-(S177-PadP$1)") (class "Default")
      (node (ref "S177") (pin "P$1") (pinfunction "P$1_P$1") (pintype "bidirectional"))
      (node (ref "S177") (pin "P$2") (pinfunction "P$2_P$2") (pintype "bidirectional"))
      (node (ref "S177") (pin "P$3") (pinfunction "P$3_P$3") (pintype "bidirectional"))
      (node (ref "S177") (pin "P$4") (pinfunction "P$4_P$4") (pintype "bidirectional"))
      (node (ref "S177") (pin "P$5") (pinfunction "P$5_P$5") (pintype "bidirectional"))
    )
    (net (code "170") (name "Net-(S178-PadP$1)") (class "Default")
      (node (ref "S178") (pin "P$1") (pinfunction "P$1_P$1") (pintype "bidirectional"))
      (node (ref "S178") (pin "P$2") (pinfunction "P$2_P$2") (pintype "bidirectional"))
      (node (ref "S178") (pin "P$3") (pinfunction "P$3_P$3") (pintype "bidirectional"))
      (node (ref "S178") (pin "P$4") (pinfunction "P$4_P$4") (pintype "bidirectional"))
      (node (ref "S178") (pin "P$5") (pinfunction "P$5_P$5") (pintype "bidirectional"))
    )
    (net (code "171") (name "Net-(S179-PadP$1)") (class "Default")
      (node (ref "S179") (pin "P$1") (pinfunction "P$1_P$1") (pintype "bidirectional"))
      (node (ref "S179") (pin "P$2") (pinfunction "P$2_P$2") (pintype "bidirectional"))
      (node (ref "S179") (pin "P$3") (pinfunction "P$3_P$3") (pintype "bidirectional"))
      (node (ref "S179") (pin "P$4") (pinfunction "P$4_P$4") (pintype "bidirectional"))
      (node (ref "S179") (pin "P$5") (pinfunction "P$5_P$5") (pintype "bidirectional"))
    )
    (net (code "172") (name "Net-(S180-PadP$1)") (class "Default")
      (node (ref "S180") (pin "P$1") (pinfunction "P$1_P$1") (pintype "bidirectional"))
      (node (ref "S180") (pin "P$2") (pinfunction "P$2_P$2") (pintype "bidirectional"))
      (node (ref "S180") (pin "P$3") (pinfunction "P$3_P$3") (pintype "bidirectional"))
      (node (ref "S180") (pin "P$4") (pinfunction "P$4_P$4") (pintype "bidirectional"))
      (node (ref "S180") (pin "P$5") (pinfunction "P$5_P$5") (pintype "bidirectional"))
    )
    (net (code "173") (name "Net-(S181-PadP$1)") (class "Default")
      (node (ref "S181") (pin "P$1") (pinfunction "P$1_P$1") (pintype "bidirectional"))
      (node (ref "S181") (pin "P$2") (pinfunction "P$2_P$2") (pintype "bidirectional"))
      (node (ref "S181") (pin "P$3") (pinfunction "P$3_P$3") (pintype "bidirectional"))
      (node (ref "S181") (pin "P$4") (pinfunction "P$4_P$4") (pintype "bidirectional"))
      (node (ref "S181") (pin "P$5") (pinfunction "P$5_P$5") (pintype "bidirectional"))
    )
    (net (code "174") (name "Net-(S182-PadP$1)") (class "Default")
      (node (ref "S182") (pin "P$1") (pinfunction "P$1_P$1") (pintype "bidirectional"))
      (node (ref "S182") (pin "P$2") (pinfunction "P$2_P$2") (pintype "bidirectional"))
      (node (ref "S182") (pin "P$3") (pinfunction "P$3_P$3") (pintype "bidirectional"))
      (node (ref "S182") (pin "P$4") (pinfunction "P$4_P$4") (pintype "bidirectional"))
      (node (ref "S182") (pin "P$5") (pinfunction "P$5_P$5") (pintype "bidirectional"))
    )
    (net (code "175") (name "Net-(S183-PadP$1)") (class "Default")
      (node (ref "S183") (pin "P$1") (pinfunction "P$1_P$1") (pintype "bidirectional"))
      (node (ref "S183") (pin "P$2") (pinfunction "P$2_P$2") (pintype "bidirectional"))
      (node (ref "S183") (pin "P$3") (pinfunction "P$3_P$3") (pintype "bidirectional"))
      (node (ref "S183") (pin "P$4") (pinfunction "P$4_P$4") (pintype "bidirectional"))
      (node (ref "S183") (pin "P$5") (pinfunction "P$5_P$5") (pintype "bidirectional"))
    )
    (net (code "176") (name "Net-(S184-PadP$1)") (class "Default")
      (node (ref "S184") (pin "P$1") (pinfunction "P$1_P$1") (pintype "bidirectional"))
      (node (ref "S184") (pin "P$2") (pinfunction "P$2_P$2") (pintype "bidirectional"))
      (node (ref "S184") (pin "P$3") (pinfunction "P$3_P$3") (pintype "bidirectional"))
      (node (ref "S184") (pin "P$4") (pinfunction "P$4_P$4") (pintype "bidirectional"))
      (node (ref "S184") (pin "P$5") (pinfunction "P$5_P$5") (pintype "bidirectional"))
    )
    (net (code "177") (name "Net-(S185-PadP$1)") (class "Default")
      (node (ref "S185") (pin "P$1") (pinfunction "P$1_P$1") (pintype "bidirectional"))
      (node (ref "S185") (pin "P$2") (pinfunction "P$2_P$2") (pintype "bidirectional"))
      (node (ref "S185") (pin "P$3") (pinfunction "P$3_P$3") (pintype "bidirectional"))
      (node (ref "S185") (pin "P$4") (pinfunction "P$4_P$4") (pintype "bidirectional"))
      (node (ref "S185") (pin "P$5") (pinfunction "P$5_P$5") (pintype "bidirectional"))
    )
    (net (code "178") (name "Net-(S186-PadP$1)") (class "Default")
      (node (ref "S186") (pin "P$1") (pinfunction "P$1_P$1") (pintype "bidirectional"))
      (node (ref "S186") (pin "P$2") (pinfunction "P$2_P$2") (pintype "bidirectional"))
      (node (ref "S186") (pin "P$3") (pinfunction "P$3_P$3") (pintype "bidirectional"))
      (node (ref "S186") (pin "P$4") (pinfunction "P$4_P$4") (pintype "bidirectional"))
      (node (ref "S186") (pin "P$5") (pinfunction "P$5_P$5") (pintype "bidirectional"))
    )
    (net (code "179") (name "Net-(S187-PadP$1)") (class "Default")
      (node (ref "S187") (pin "P$1") (pinfunction "P$1_P$1") (pintype "bidirectional"))
      (node (ref "S187") (pin "P$2") (pinfunction "P$2_P$2") (pintype "bidirectional"))
      (node (ref "S187") (pin "P$3") (pinfunction "P$3_P$3") (pintype "bidirectional"))
      (node (ref "S187") (pin "P$4") (pinfunction "P$4_P$4") (pintype "bidirectional"))
      (node (ref "S187") (pin "P$5") (pinfunction "P$5_P$5") (pintype "bidirectional"))
    )
    (net (code "180") (name "Net-(S188-PadP$1)") (class "Default")
      (node (ref "S188") (pin "P$1") (pinfunction "P$1_P$1") (pintype "bidirectional"))
      (node (ref "S188") (pin "P$2") (pinfunction "P$2_P$2") (pintype "bidirectional"))
      (node (ref "S188") (pin "P$3") (pinfunction "P$3_P$3") (pintype "bidirectional"))
      (node (ref "S188") (pin "P$4") (pinfunction "P$4_P$4") (pintype "bidirectional"))
      (node (ref "S188") (pin "P$5") (pinfunction "P$5_P$5") (pintype "bidirectional"))
    )
    (net (code "181") (name "Net-(S189-PadP$1)") (class "Default")
      (node (ref "S189") (pin "P$1") (pinfunction "P$1_P$1") (pintype "bidirectional"))
      (node (ref "S189") (pin "P$2") (pinfunction "P$2_P$2") (pintype "bidirectional"))
      (node (ref "S189") (pin "P$3") (pinfunction "P$3_P$3") (pintype "bidirectional"))
      (node (ref "S189") (pin "P$4") (pinfunction "P$4_P$4") (pintype "bidirectional"))
      (node (ref "S189") (pin "P$5") (pinfunction "P$5_P$5") (pintype "bidirectional"))
    )
    (net (code "182") (name "Net-(S196-PadP$1)") (class "Default")
      (node (ref "S196") (pin "P$1") (pinfunction "P$1_P$1") (pintype "bidirectional"))
      (node (ref "S196") (pin "P$2") (pinfunction "P$2_P$2") (pintype "bidirectional"))
      (node (ref "S196") (pin "P$3") (pinfunction "P$3_P$3") (pintype "bidirectional"))
      (node (ref "S196") (pin "P$4") (pinfunction "P$4_P$4") (pintype "bidirectional"))
      (node (ref "S196") (pin "P$5") (pinfunction "P$5_P$5") (pintype "bidirectional"))
    )
    (net (code "183") (name "Net-(S197-PadP$1)") (class "Default")
      (node (ref "S197") (pin "P$1") (pinfunction "P$1_P$1") (pintype "bidirectional"))
      (node (ref "S197") (pin "P$2") (pinfunction "P$2_P$2") (pintype "bidirectional"))
      (node (ref "S197") (pin "P$3") (pinfunction "P$3_P$3") (pintype "bidirectional"))
      (node (ref "S197") (pin "P$4") (pinfunction "P$4_P$4") (pintype "bidirectional"))
      (node (ref "S197") (pin "P$5") (pinfunction "P$5_P$5") (pintype "bidirectional"))
    )
    (net (code "184") (name "Net-(S198-PadP$1)") (class "Default")
      (node (ref "S198") (pin "P$1") (pinfunction "P$1_P$1") (pintype "bidirectional"))
      (node (ref "S198") (pin "P$2") (pinfunction "P$2_P$2") (pintype "bidirectional"))
      (node (ref "S198") (pin "P$3") (pinfunction "P$3_P$3") (pintype "bidirectional"))
      (node (ref "S198") (pin "P$4") (pinfunction "P$4_P$4") (pintype "bidirectional"))
      (node (ref "S198") (pin "P$5") (pinfunction "P$5_P$5") (pintype "bidirectional"))
    )
    (net (code "185") (name "Net-(S199-PadP$1)") (class "Default")
      (node (ref "S199") (pin "P$1") (pinfunction "P$1_P$1") (pintype "bidirectional"))
      (node (ref "S199") (pin "P$2") (pinfunction "P$2_P$2") (pintype "bidirectional"))
      (node (ref "S199") (pin "P$3") (pinfunction "P$3_P$3") (pintype "bidirectional"))
      (node (ref "S199") (pin "P$4") (pinfunction "P$4_P$4") (pintype "bidirectional"))
      (node (ref "S199") (pin "P$5") (pinfunction "P$5_P$5") (pintype "bidirectional"))
    )
    (net (code "186") (name "Net-(S200-PadP$1)") (class "Default")
      (node (ref "S200") (pin "P$1") (pinfunction "P$1_P$1") (pintype "bidirectional"))
      (node (ref "S200") (pin "P$2") (pinfunction "P$2_P$2") (pintype "bidirectional"))
      (node (ref "S200") (pin "P$3") (pinfunction "P$3_P$3") (pintype "bidirectional"))
      (node (ref "S200") (pin "P$4") (pinfunction "P$4_P$4") (pintype "bidirectional"))
      (node (ref "S200") (pin "P$5") (pinfunction "P$5_P$5") (pintype "bidirectional"))
    )
    (net (code "187") (name "Net-(S201-PadP$1)") (class "Default")
      (node (ref "S201") (pin "P$1") (pinfunction "P$1_P$1") (pintype "bidirectional"))
      (node (ref "S201") (pin "P$2") (pinfunction "P$2_P$2") (pintype "bidirectional"))
      (node (ref "S201") (pin "P$3") (pinfunction "P$3_P$3") (pintype "bidirectional"))
      (node (ref "S201") (pin "P$4") (pinfunction "P$4_P$4") (pintype "bidirectional"))
      (node (ref "S201") (pin "P$5") (pinfunction "P$5_P$5") (pintype "bidirectional"))
    )
    (net (code "188") (name "Net-(S202-PadP$1)") (class "Default")
      (node (ref "S202") (pin "P$1") (pinfunction "P$1_P$1") (pintype "bidirectional"))
      (node (ref "S202") (pin "P$2") (pinfunction "P$2_P$2") (pintype "bidirectional"))
      (node (ref "S202") (pin "P$3") (pinfunction "P$3_P$3") (pintype "bidirectional"))
      (node (ref "S202") (pin "P$4") (pinfunction "P$4_P$4") (pintype "bidirectional"))
      (node (ref "S202") (pin "P$5") (pinfunction "P$5_P$5") (pintype "bidirectional"))
    )
    (net (code "189") (name "Net-(S203-PadP$1)") (class "Default")
      (node (ref "S203") (pin "P$1") (pinfunction "P$1_P$1") (pintype "bidirectional"))
      (node (ref "S203") (pin "P$2") (pinfunction "P$2_P$2") (pintype "bidirectional"))
      (node (ref "S203") (pin "P$3") (pinfunction "P$3_P$3") (pintype "bidirectional"))
      (node (ref "S203") (pin "P$4") (pinfunction "P$4_P$4") (pintype "bidirectional"))
      (node (ref "S203") (pin "P$5") (pinfunction "P$5_P$5") (pintype "bidirectional"))
    )
    (net (code "190") (name "Net-(S204-PadP$1)") (class "Default")
      (node (ref "S204") (pin "P$1") (pinfunction "P$1_P$1") (pintype "bidirectional"))
      (node (ref "S204") (pin "P$2") (pinfunction "P$2_P$2") (pintype "bidirectional"))
      (node (ref "S204") (pin "P$3") (pinfunction "P$3_P$3") (pintype "bidirectional"))
      (node (ref "S204") (pin "P$4") (pinfunction "P$4_P$4") (pintype "bidirectional"))
      (node (ref "S204") (pin "P$5") (pinfunction "P$5_P$5") (pintype "bidirectional"))
    )
    (net (code "191") (name "Net-(S205-PadP$1)") (class "Default")
      (node (ref "S205") (pin "P$1") (pinfunction "P$1_P$1") (pintype "bidirectional"))
      (node (ref "S205") (pin "P$2") (pinfunction "P$2_P$2") (pintype "bidirectional"))
      (node (ref "S205") (pin "P$3") (pinfunction "P$3_P$3") (pintype "bidirectional"))
      (node (ref "S205") (pin "P$4") (pinfunction "P$4_P$4") (pintype "bidirectional"))
      (node (ref "S205") (pin "P$5") (pinfunction "P$5_P$5") (pintype "bidirectional"))
    )
    (net (code "192") (name "Net-(S206-PadP$1)") (class "Default")
      (node (ref "S206") (pin "P$1") (pinfunction "P$1_P$1") (pintype "bidirectional"))
      (node (ref "S206") (pin "P$2") (pinfunction "P$2_P$2") (pintype "bidirectional"))
      (node (ref "S206") (pin "P$3") (pinfunction "P$3_P$3") (pintype "bidirectional"))
      (node (ref "S206") (pin "P$4") (pinfunction "P$4_P$4") (pintype "bidirectional"))
      (node (ref "S206") (pin "P$5") (pinfunction "P$5_P$5") (pintype "bidirectional"))
    )
    (net (code "193") (name "Net-(S207-PadP$1)") (class "Default")
      (node (ref "S207") (pin "P$1") (pinfunction "P$1_P$1") (pintype "bidirectional"))
      (node (ref "S207") (pin "P$2") (pinfunction "P$2_P$2") (pintype "bidirectional"))
      (node (ref "S207") (pin "P$3") (pinfunction "P$3_P$3") (pintype "bidirectional"))
      (node (ref "S207") (pin "P$4") (pinfunction "P$4_P$4") (pintype "bidirectional"))
      (node (ref "S207") (pin "P$5") (pinfunction "P$5_P$5") (pintype "bidirectional"))
    )
    (net (code "194") (name "Net-(S208-PadP$1)") (class "Default")
      (node (ref "S208") (pin "P$1") (pinfunction "P$1_P$1") (pintype "bidirectional"))
      (node (ref "S208") (pin "P$2") (pinfunction "P$2_P$2") (pintype "bidirectional"))
      (node (ref "S208") (pin "P$3") (pinfunction "P$3_P$3") (pintype "bidirectional"))
      (node (ref "S208") (pin "P$4") (pinfunction "P$4_P$4") (pintype "bidirectional"))
      (node (ref "S208") (pin "P$5") (pinfunction "P$5_P$5") (pintype "bidirectional"))
    )
    (net (code "195") (name "Net-(S209-PadP$1)") (class "Default")
      (node (ref "S209") (pin "P$1") (pinfunction "P$1_P$1") (pintype "bidirectional"))
      (node (ref "S209") (pin "P$2") (pinfunction "P$2_P$2") (pintype "bidirectional"))
      (node (ref "S209") (pin "P$3") (pinfunction "P$3_P$3") (pintype "bidirectional"))
      (node (ref "S209") (pin "P$4") (pinfunction "P$4_P$4") (pintype "bidirectional"))
      (node (ref "S209") (pin "P$5") (pinfunction "P$5_P$5") (pintype "bidirectional"))
    )
    (net (code "196") (name "Net-(S210-PadP$1)") (class "Default")
      (node (ref "S210") (pin "P$1") (pinfunction "P$1_P$1") (pintype "bidirectional"))
      (node (ref "S210") (pin "P$2") (pinfunction "P$2_P$2") (pintype "bidirectional"))
      (node (ref "S210") (pin "P$3") (pinfunction "P$3_P$3") (pintype "bidirectional"))
      (node (ref "S210") (pin "P$4") (pinfunction "P$4_P$4") (pintype "bidirectional"))
      (node (ref "S210") (pin "P$5") (pinfunction "P$5_P$5") (pintype "bidirectional"))
    )
    (net (code "197") (name "Net-(S211-PadP$1)") (class "Default")
      (node (ref "S211") (pin "P$1") (pinfunction "P$1_P$1") (pintype "bidirectional"))
      (node (ref "S211") (pin "P$2") (pinfunction "P$2_P$2") (pintype "bidirectional"))
      (node (ref "S211") (pin "P$3") (pinfunction "P$3_P$3") (pintype "bidirectional"))
      (node (ref "S211") (pin "P$4") (pinfunction "P$4_P$4") (pintype "bidirectional"))
      (node (ref "S211") (pin "P$5") (pinfunction "P$5_P$5") (pintype "bidirectional"))
    )
    (net (code "198") (name "Net-(S212-PadP$1)") (class "Default")
      (node (ref "S212") (pin "P$1") (pinfunction "P$1_P$1") (pintype "bidirectional"))
      (node (ref "S212") (pin "P$2") (pinfunction "P$2_P$2") (pintype "bidirectional"))
      (node (ref "S212") (pin "P$3") (pinfunction "P$3_P$3") (pintype "bidirectional"))
      (node (ref "S212") (pin "P$4") (pinfunction "P$4_P$4") (pintype "bidirectional"))
      (node (ref "S212") (pin "P$5") (pinfunction "P$5_P$5") (pintype "bidirectional"))
    )
    (net (code "199") (name "Net-(S213-PadP$1)") (class "Default")
      (node (ref "S213") (pin "P$1") (pinfunction "P$1_P$1") (pintype "bidirectional"))
      (node (ref "S213") (pin "P$2") (pinfunction "P$2_P$2") (pintype "bidirectional"))
      (node (ref "S213") (pin "P$3") (pinfunction "P$3_P$3") (pintype "bidirectional"))
      (node (ref "S213") (pin "P$4") (pinfunction "P$4_P$4") (pintype "bidirectional"))
      (node (ref "S213") (pin "P$5") (pinfunction "P$5_P$5") (pintype "bidirectional"))
    )
    (net (code "200") (name "Net-(S214-PadP$1)") (class "Default")
      (node (ref "S214") (pin "P$1") (pinfunction "P$1_P$1") (pintype "bidirectional"))
      (node (ref "S214") (pin "P$2") (pinfunction "P$2_P$2") (pintype "bidirectional"))
      (node (ref "S214") (pin "P$3") (pinfunction "P$3_P$3") (pintype "bidirectional"))
      (node (ref "S214") (pin "P$4") (pinfunction "P$4_P$4") (pintype "bidirectional"))
      (node (ref "S214") (pin "P$5") (pinfunction "P$5_P$5") (pintype "bidirectional"))
    )
    (net (code "201") (name "Net-(S215-PadP$1)") (class "Default")
      (node (ref "S215") (pin "P$1") (pinfunction "P$1_P$1") (pintype "bidirectional"))
      (node (ref "S215") (pin "P$2") (pinfunction "P$2_P$2") (pintype "bidirectional"))
      (node (ref "S215") (pin "P$3") (pinfunction "P$3_P$3") (pintype "bidirectional"))
      (node (ref "S215") (pin "P$4") (pinfunction "P$4_P$4") (pintype "bidirectional"))
      (node (ref "S215") (pin "P$5") (pinfunction "P$5_P$5") (pintype "bidirectional"))
    )
    (net (code "202") (name "Net-(S216-PadP$1)") (class "Default")
      (node (ref "S216") (pin "P$1") (pinfunction "P$1_P$1") (pintype "bidirectional"))
      (node (ref "S216") (pin "P$2") (pinfunction "P$2_P$2") (pintype "bidirectional"))
      (node (ref "S216") (pin "P$3") (pinfunction "P$3_P$3") (pintype "bidirectional"))
      (node (ref "S216") (pin "P$4") (pinfunction "P$4_P$4") (pintype "bidirectional"))
      (node (ref "S216") (pin "P$5") (pinfunction "P$5_P$5") (pintype "bidirectional"))
    )
    (net (code "203") (name "Net-(S217-PadP$1)") (class "Default")
      (node (ref "S217") (pin "P$1") (pinfunction "P$1_P$1") (pintype "bidirectional"))
      (node (ref "S217") (pin "P$2") (pinfunction "P$2_P$2") (pintype "bidirectional"))
      (node (ref "S217") (pin "P$3") (pinfunction "P$3_P$3") (pintype "bidirectional"))
      (node (ref "S217") (pin "P$4") (pinfunction "P$4_P$4") (pintype "bidirectional"))
      (node (ref "S217") (pin "P$5") (pinfunction "P$5_P$5") (pintype "bidirectional"))
    )
    (net (code "204") (name "Net-(S218-PadP$1)") (class "Default")
      (node (ref "S218") (pin "P$1") (pinfunction "P$1_P$1") (pintype "bidirectional"))
      (node (ref "S218") (pin "P$2") (pinfunction "P$2_P$2") (pintype "bidirectional"))
      (node (ref "S218") (pin "P$3") (pinfunction "P$3_P$3") (pintype "bidirectional"))
      (node (ref "S218") (pin "P$4") (pinfunction "P$4_P$4") (pintype "bidirectional"))
      (node (ref "S218") (pin "P$5") (pinfunction "P$5_P$5") (pintype "bidirectional"))
    )
    (net (code "205") (name "Net-(S219-PadP$1)") (class "Default")
      (node (ref "S219") (pin "P$1") (pinfunction "P$1_P$1") (pintype "bidirectional"))
      (node (ref "S219") (pin "P$2") (pinfunction "P$2_P$2") (pintype "bidirectional"))
      (node (ref "S219") (pin "P$3") (pinfunction "P$3_P$3") (pintype "bidirectional"))
      (node (ref "S219") (pin "P$4") (pinfunction "P$4_P$4") (pintype "bidirectional"))
      (node (ref "S219") (pin "P$5") (pinfunction "P$5_P$5") (pintype "bidirectional"))
    )
    (net (code "206") (name "Net-(S220-PadP$1)") (class "Default")
      (node (ref "S220") (pin "P$1") (pinfunction "P$1_P$1") (pintype "bidirectional"))
      (node (ref "S220") (pin "P$2") (pinfunction "P$2_P$2") (pintype "bidirectional"))
      (node (ref "S220") (pin "P$3") (pinfunction "P$3_P$3") (pintype "bidirectional"))
      (node (ref "S220") (pin "P$4") (pinfunction "P$4_P$4") (pintype "bidirectional"))
      (node (ref "S220") (pin "P$5") (pinfunction "P$5_P$5") (pintype "bidirectional"))
    )
    (net (code "207") (name "Net-(S221-PadP$1)") (class "Default")
      (node (ref "S221") (pin "P$1") (pinfunction "P$1_P$1") (pintype "bidirectional"))
      (node (ref "S221") (pin "P$2") (pinfunction "P$2_P$2") (pintype "bidirectional"))
      (node (ref "S221") (pin "P$3") (pinfunction "P$3_P$3") (pintype "bidirectional"))
      (node (ref "S221") (pin "P$4") (pinfunction "P$4_P$4") (pintype "bidirectional"))
      (node (ref "S221") (pin "P$5") (pinfunction "P$5_P$5") (pintype "bidirectional"))
    )
    (net (code "208") (name "Net-(S222-PadP$1)") (class "Default")
      (node (ref "S222") (pin "P$1") (pinfunction "P$1_P$1") (pintype "bidirectional"))
      (node (ref "S222") (pin "P$2") (pinfunction "P$2_P$2") (pintype "bidirectional"))
      (node (ref "S222") (pin "P$3") (pinfunction "P$3_P$3") (pintype "bidirectional"))
      (node (ref "S222") (pin "P$4") (pinfunction "P$4_P$4") (pintype "bidirectional"))
      (node (ref "S222") (pin "P$5") (pinfunction "P$5_P$5") (pintype "bidirectional"))
    )
    (net (code "209") (name "Net-(S223-PadP$1)") (class "Default")
      (node (ref "S223") (pin "P$1") (pinfunction "P$1_P$1") (pintype "bidirectional"))
      (node (ref "S223") (pin "P$2") (pinfunction "P$2_P$2") (pintype "bidirectional"))
      (node (ref "S223") (pin "P$3") (pinfunction "P$3_P$3") (pintype "bidirectional"))
      (node (ref "S223") (pin "P$4") (pinfunction "P$4_P$4") (pintype "bidirectional"))
      (node (ref "S223") (pin "P$5") (pinfunction "P$5_P$5") (pintype "bidirectional"))
    )
    (net (code "210") (name "Net-(S224-PadP$1)") (class "Default")
      (node (ref "S224") (pin "P$1") (pinfunction "P$1_P$1") (pintype "bidirectional"))
      (node (ref "S224") (pin "P$2") (pinfunction "P$2_P$2") (pintype "bidirectional"))
      (node (ref "S224") (pin "P$3") (pinfunction "P$3_P$3") (pintype "bidirectional"))
      (node (ref "S224") (pin "P$4") (pinfunction "P$4_P$4") (pintype "bidirectional"))
      (node (ref "S224") (pin "P$5") (pinfunction "P$5_P$5") (pintype "bidirectional"))
    )
    (net (code "211") (name "Net-(S225-PadP$1)") (class "Default")
      (node (ref "S225") (pin "P$1") (pinfunction "P$1_P$1") (pintype "bidirectional"))
      (node (ref "S225") (pin "P$2") (pinfunction "P$2_P$2") (pintype "bidirectional"))
      (node (ref "S225") (pin "P$3") (pinfunction "P$3_P$3") (pintype "bidirectional"))
      (node (ref "S225") (pin "P$4") (pinfunction "P$4_P$4") (pintype "bidirectional"))
      (node (ref "S225") (pin "P$5") (pinfunction "P$5_P$5") (pintype "bidirectional"))
    )
    (net (code "212") (name "Net-(S226-PadP$1)") (class "Default")
      (node (ref "S226") (pin "P$1") (pinfunction "P$1_P$1") (pintype "bidirectional"))
      (node (ref "S226") (pin "P$2") (pinfunction "P$2_P$2") (pintype "bidirectional"))
      (node (ref "S226") (pin "P$3") (pinfunction "P$3_P$3") (pintype "bidirectional"))
      (node (ref "S226") (pin "P$4") (pinfunction "P$4_P$4") (pintype "bidirectional"))
      (node (ref "S226") (pin "P$5") (pinfunction "P$5_P$5") (pintype "bidirectional"))
    )
    (net (code "213") (name "Net-(SV2-Pad7)") (class "Default")
      (node (ref "SV2") (pin "7") (pinfunction "7_7") (pintype "passive"))
      (node (ref "SV2") (pin "8") (pinfunction "8_8") (pintype "passive"))
    )
    (net (code "214") (name "Net-(SV2-Pad10)") (class "Default")
      (node (ref "SV2") (pin "10") (pinfunction "10_10") (pintype "passive"))
      (node (ref "SV2") (pin "9") (pinfunction "9_9") (pintype "passive"))
    )
    (net (code "215") (name "Net-(SV2-Pad11)") (class "Default")
      (node (ref "SV2") (pin "11") (pinfunction "11_11") (pintype "passive"))
      (node (ref "SV2") (pin "12") (pinfunction "12_12") (pintype "passive"))
    )
    (net (code "216") (name "Net-(SV2-Pad15)") (class "Default")
      (node (ref "SV2") (pin "15") (pinfunction "15_15") (pintype "passive"))
      (node (ref "SV2") (pin "16") (pinfunction "16_16") (pintype "passive"))
    )
    (net (code "217") (name "Net-(SV2-Pad17)") (class "Default")
      (node (ref "SV2") (pin "17") (pinfunction "17_17") (pintype "passive"))
      (node (ref "SV2") (pin "18") (pinfunction "18_18") (pintype "passive"))
    )
    (net (code "218") (name "Net-(SV2-Pad21)") (class "Default")
      (node (ref "SV2") (pin "21") (pinfunction "21_21") (pintype "passive"))
      (node (ref "SV2") (pin "22") (pinfunction "22_22") (pintype "passive"))
    )
    (net (code "219") (name "Net-(SV2-Pad23)") (class "Default")
      (node (ref "SV2") (pin "23") (pinfunction "23_23") (pintype "passive"))
      (node (ref "SV2") (pin "24") (pinfunction "24_24") (pintype "passive"))
    )
    (net (code "220") (name "Net-(SV2-Pad25)") (class "Default")
      (node (ref "SV2") (pin "25") (pinfunction "25_25") (pintype "passive"))
      (node (ref "SV2") (pin "26") (pinfunction "26_26") (pintype "passive"))
    )
    (net (code "221") (name "Net-(SV2-Pad27)") (class "Default")
      (node (ref "SV2") (pin "27") (pinfunction "27_27") (pintype "passive"))
      (node (ref "SV2") (pin "28") (pinfunction "28_28") (pintype "passive"))
    )
    (net (code "222") (name "Net-(SV2-Pad31)") (class "Default")
      (node (ref "SV2") (pin "31") (pinfunction "31_31") (pintype "passive"))
      (node (ref "SV2") (pin "32") (pinfunction "32_32") (pintype "passive"))
    )
    (net (code "223") (name "Net-(SV2-Pad35)") (class "Default")
      (node (ref "SV2") (pin "35") (pinfunction "35_35") (pintype "passive"))
      (node (ref "SV2") (pin "36") (pinfunction "36_36") (pintype "passive"))
    )
    (net (code "224") (name "Net-(SV2-Pad37)") (class "Default")
      (node (ref "SV2") (pin "37") (pinfunction "37_37") (pintype "passive"))
      (node (ref "SV2") (pin "38") (pinfunction "38_38") (pintype "passive"))
    )
    (net (code "225") (name "Net-(SV2-Pad39)") (class "Default")
      (node (ref "SV2") (pin "39") (pinfunction "39_39") (pintype "passive"))
      (node (ref "SV2") (pin "40") (pinfunction "40_40") (pintype "passive"))
    )
    (net (code "226") (name "Net-(SV4-Pad1)") (class "Default")
      (node (ref "SV4") (pin "1") (pinfunction "1_1") (pintype "passive"))
      (node (ref "SV4") (pin "2") (pinfunction "2_2") (pintype "passive"))
    )
    (net (code "227") (name "Net-(SV4-Pad3)") (class "Default")
      (node (ref "SV4") (pin "3") (pinfunction "3_3") (pintype "passive"))
      (node (ref "SV4") (pin "4") (pinfunction "4_4") (pintype "passive"))
    )
    (net (code "228") (name "Net-(SV4-Pad5)") (class "Default")
      (node (ref "SV4") (pin "5") (pinfunction "5_5") (pintype "passive"))
      (node (ref "SV4") (pin "6") (pinfunction "6_6") (pintype "passive"))
    )
    (net (code "229") (name "Net-(SV4-Pad7)") (class "Default")
      (node (ref "SV4") (pin "7") (pinfunction "7_7") (pintype "passive"))
      (node (ref "SV4") (pin "8") (pinfunction "8_8") (pintype "passive"))
    )
    (net (code "230") (name "Net-(SV4-Pad11)") (class "Default")
      (node (ref "SV4") (pin "11") (pinfunction "11_11") (pintype "passive"))
      (node (ref "SV4") (pin "12") (pinfunction "12_12") (pintype "passive"))
    )
    (net (code "231") (name "Net-(SV4-Pad13)") (class "Default")
      (node (ref "SV4") (pin "13") (pinfunction "13_13") (pintype "passive"))
      (node (ref "SV4") (pin "14") (pinfunction "14_14") (pintype "passive"))
    )
    (net (code "232") (name "Net-(SV4-Pad15)") (class "Default")
      (node (ref "SV4") (pin "15") (pinfunction "15_15") (pintype "passive"))
      (node (ref "SV4") (pin "16") (pinfunction "16_16") (pintype "passive"))
    )
    (net (code "233") (name "Net-(SV4-Pad17)") (class "Default")
      (node (ref "SV4") (pin "17") (pinfunction "17_17") (pintype "passive"))
      (node (ref "SV4") (pin "18") (pinfunction "18_18") (pintype "passive"))
    )
    (net (code "234") (name "Net-(SV4-Pad19)") (class "Default")
      (node (ref "SV4") (pin "19") (pinfunction "19_19") (pintype "passive"))
      (node (ref "SV4") (pin "20") (pinfunction "20_20") (pintype "passive"))
    )
    (net (code "235") (name "Net-(SV4-Pad21)") (class "Default")
      (node (ref "SV4") (pin "21") (pinfunction "21_21") (pintype "passive"))
      (node (ref "SV4") (pin "22") (pinfunction "22_22") (pintype "passive"))
    )
    (net (code "236") (name "Net-(SV4-Pad23)") (class "Default")
      (node (ref "SV4") (pin "23") (pinfunction "23_23") (pintype "passive"))
      (node (ref "SV4") (pin "24") (pinfunction "24_24") (pintype "passive"))
    )
    (net (code "237") (name "Net-(SV4-Pad27)") (class "Default")
      (node (ref "SV4") (pin "27") (pinfunction "27_27") (pintype "passive"))
      (node (ref "SV4") (pin "28") (pinfunction "28_28") (pintype "passive"))
    )
    (net (code "238") (name "Net-(SV4-Pad29)") (class "Default")
      (node (ref "SV4") (pin "29") (pinfunction "29_29") (pintype "passive"))
      (node (ref "SV4") (pin "30") (pinfunction "30_30") (pintype "passive"))
    )
    (net (code "239") (name "Net-(SV4-Pad31)") (class "Default")
      (node (ref "SV4") (pin "31") (pinfunction "31_31") (pintype "passive"))
      (node (ref "SV4") (pin "32") (pinfunction "32_32") (pintype "passive"))
    )
    (net (code "240") (name "Net-(SV4-Pad33)") (class "Default")
      (node (ref "SV4") (pin "33") (pinfunction "33_33") (pintype "passive"))
      (node (ref "SV4") (pin "34") (pinfunction "34_34") (pintype "passive"))
    )
    (net (code "241") (name "Net-(SV4-Pad35)") (class "Default")
      (node (ref "SV4") (pin "35") (pinfunction "35_35") (pintype "passive"))
      (node (ref "SV4") (pin "36") (pinfunction "36_36") (pintype "passive"))
    )
    (net (code "242") (name "Net-(SV4-Pad37)") (class "Default")
      (node (ref "SV4") (pin "37") (pinfunction "37_37") (pintype "passive"))
      (node (ref "SV4") (pin "38") (pinfunction "38_38") (pintype "passive"))
    )
    (net (code "243") (name "Net-(SV5-Pad1)") (class "Default")
      (node (ref "SV5") (pin "1") (pinfunction "1_1") (pintype "passive"))
      (node (ref "SV5") (pin "2") (pinfunction "2_2") (pintype "passive"))
    )
    (net (code "244") (name "Net-(SV5-Pad3)") (class "Default")
      (node (ref "SV5") (pin "3") (pinfunction "3_3") (pintype "passive"))
      (node (ref "SV5") (pin "4") (pinfunction "4_4") (pintype "passive"))
    )
    (net (code "245") (name "Net-(SV5-Pad5)") (class "Default")
      (node (ref "SV5") (pin "5") (pinfunction "5_5") (pintype "passive"))
      (node (ref "SV5") (pin "6") (pinfunction "6_6") (pintype "passive"))
    )
    (net (code "246") (name "Net-(SV6-Pad5)") (class "Default")
      (node (ref "SV6") (pin "5") (pinfunction "5_5") (pintype "passive"))
      (node (ref "SV6") (pin "6") (pinfunction "6_6") (pintype "passive"))
    )
    (net (code "247") (name "Net-(T1-B)") (class "Default")
      (node (ref "R1") (pin "2") (pinfunction "2_2") (pintype "passive"))
      (node (ref "T1") (pin "1") (pinfunction "B_1") (pintype "passive"))
    )
    (net (code "248") (name "Net-(T1-C)") (class "Default")
      (node (ref "J4") (pin "P$1") (pinfunction "P$1_P$1") (pintype "bidirectional"))
      (node (ref "J4") (pin "P$2") (pinfunction "P$2_P$2") (pintype "bidirectional"))
      (node (ref "J4") (pin "P$3") (pinfunction "P$3_P$3") (pintype "bidirectional"))
      (node (ref "T1") (pin "2") (pinfunction "C_2") (pintype "passive"))
    )
    (net (code "249") (name "Net-(T2-B)") (class "Default")
      (node (ref "R2") (pin "2") (pinfunction "2_2") (pintype "passive"))
      (node (ref "T2") (pin "1") (pinfunction "B_1") (pintype "passive"))
    )
    (net (code "250") (name "Net-(T2-C)") (class "Default")
      (node (ref "J23") (pin "P$1") (pinfunction "P$1_P$1") (pintype "bidirectional"))
      (node (ref "J23") (pin "P$2") (pinfunction "P$2_P$2") (pintype "bidirectional"))
      (node (ref "J23") (pin "P$3") (pinfunction "P$3_P$3") (pintype "bidirectional"))
      (node (ref "T2") (pin "2") (pinfunction "C_2") (pintype "passive"))
    )
    (net (code "251") (name "Net-(U$1-P3_SCLK)") (class "Default")
      (node (ref "J125") (pin "P$1") (pinfunction "P$1_P$1") (pintype "bidirectional"))
      (node (ref "J125") (pin "P$2") (pinfunction "P$2_P$2") (pintype "bidirectional"))
      (node (ref "J125") (pin "P$3") (pinfunction "P$3_P$3") (pintype "bidirectional"))
      (node (ref "U$1") (pin "3") (pinfunction "P3_SCLK_3") (pintype "bidirectional"))
    )
    (net (code "252") (name "Net-(U$1-P4_SDA{slash}SPIMOSI)") (class "Default")
      (node (ref "J126") (pin "P$1") (pinfunction "P$1_P$1") (pintype "bidirectional"))
      (node (ref "J126") (pin "P$2") (pinfunction "P$2_P$2") (pintype "bidirectional"))
      (node (ref "J126") (pin "P$3") (pinfunction "P$3_P$3") (pintype "bidirectional"))
      (node (ref "U$1") (pin "4") (pinfunction "P4_SDA/SPIMOSI_4") (pintype "bidirectional"))
    )
    (net (code "253") (name "Net-(U$1-P5_EDA{slash}AUX-DA)") (class "Default")
      (node (ref "J127") (pin "P$1") (pinfunction "P$1_P$1") (pintype "bidirectional"))
      (node (ref "J127") (pin "P$2") (pinfunction "P$2_P$2") (pintype "bidirectional"))
      (node (ref "J127") (pin "P$3") (pinfunction "P$3_P$3") (pintype "bidirectional"))
      (node (ref "U$1") (pin "5") (pinfunction "P5_EDA/AUX-DA_5") (pintype "bidirectional"))
    )
    (net (code "254") (name "Net-(U$1-P6_ECL{slash}AUX-CL)") (class "Default")
      (node (ref "J128") (pin "P$1") (pinfunction "P$1_P$1") (pintype "bidirectional"))
      (node (ref "J128") (pin "P$2") (pinfunction "P$2_P$2") (pintype "bidirectional"))
      (node (ref "J128") (pin "P$3") (pinfunction "P$3_P$3") (pintype "bidirectional"))
      (node (ref "U$1") (pin "6") (pinfunction "P6_ECL/AUX-CL_6") (pintype "bidirectional"))
    )
    (net (code "255") (name "Net-(U$1-P7_ADO{slash}SPIMISO)") (class "Default")
      (node (ref "J129") (pin "P$1") (pinfunction "P$1_P$1") (pintype "bidirectional"))
      (node (ref "J129") (pin "P$2") (pinfunction "P$2_P$2") (pintype "bidirectional"))
      (node (ref "J129") (pin "P$3") (pinfunction "P$3_P$3") (pintype "bidirectional"))
      (node (ref "U$1") (pin "7") (pinfunction "P7_ADO/SPIMISO_7") (pintype "bidirectional"))
    )
    (net (code "256") (name "Net-(U$1-P8_INT)") (class "Default")
      (node (ref "J130") (pin "P$1") (pinfunction "P$1_P$1") (pintype "bidirectional"))
      (node (ref "J130") (pin "P$2") (pinfunction "P$2_P$2") (pintype "bidirectional"))
      (node (ref "J130") (pin "P$3") (pinfunction "P$3_P$3") (pintype "bidirectional"))
      (node (ref "U$1") (pin "8") (pinfunction "P8_INT_8") (pintype "bidirectional"))
    )
    (net (code "257") (name "Net-(U$1-P9_NCS)") (class "Default")
      (node (ref "J131") (pin "P$1") (pinfunction "P$1_P$1") (pintype "bidirectional"))
      (node (ref "J131") (pin "P$2") (pinfunction "P$2_P$2") (pintype "bidirectional"))
      (node (ref "J131") (pin "P$3") (pinfunction "P$3_P$3") (pintype "bidirectional"))
      (node (ref "U$1") (pin "9") (pinfunction "P9_NCS_9") (pintype "bidirectional"))
    )
    (net (code "258") (name "Net-(U$1-P10_FSYNC)") (class "Default")
      (node (ref "J132") (pin "P$1") (pinfunction "P$1_P$1") (pintype "bidirectional"))
      (node (ref "J132") (pin "P$2") (pinfunction "P$2_P$2") (pintype "bidirectional"))
      (node (ref "J132") (pin "P$3") (pinfunction "P$3_P$3") (pintype "bidirectional"))
      (node (ref "U$1") (pin "10") (pinfunction "P10_FSYNC_10") (pintype "bidirectional"))
    )
    (net (code "259") (name "Net-(U1-MODE)") (class "Default")
      (node (ref "JP2") (pin "1") (pinfunction "1_1") (pintype "passive"))
      (node (ref "R4") (pin "1") (pinfunction "1_1") (pintype "passive"))
      (node (ref "U1") (pin "14") (pinfunction "MODE_14") (pintype "bidirectional"))
    )
    (net (code "260") (name "Net-(U1-PHASE)") (class "Default")
      (node (ref "J196") (pin "P$1") (pinfunction "P$1_P$1") (pintype "bidirectional"))
      (node (ref "J196") (pin "P$2") (pinfunction "P$2_P$2") (pintype "bidirectional"))
      (node (ref "U1") (pin "7") (pinfunction "PHASE_7") (pintype "bidirectional"))
    )
    (net (code "261") (name "Net-(U1-RC)") (class "Default")
      (node (ref "C14") (pin "1") (pinfunction "1_1") (pintype "passive"))
      (node (ref "R3") (pin "2") (pinfunction "2_2") (pintype "passive"))
      (node (ref "U1") (pin "3") (pinfunction "RC_3") (pintype "bidirectional"))
    )
    (net (code "262") (name "Net-(U1-~{BRAKE})") (class "Default")
      (node (ref "R8") (pin "1") (pinfunction "1_1") (pintype "passive"))
      (node (ref "U1") (pin "1") (pinfunction "~{BRAKE}_1") (pintype "bidirectional"))
    )
    (net (code "263") (name "Net-(U2-CPH)") (class "Default")
      (node (ref "C19") (pin "2") (pinfunction "2_2") (pintype "passive"))
      (node (ref "U2") (pin "P$13") (pinfunction "CPH_P$13") (pintype "bidirectional"))
    )
    (net (code "264") (name "Net-(U2-CPL)") (class "Default")
      (node (ref "C19") (pin "1") (pinfunction "1_1") (pintype "passive"))
      (node (ref "U2") (pin "P$14") (pinfunction "CPL_P$14") (pintype "bidirectional"))
    )
    (net (code "265") (name "Net-(U2-IPROPI)") (class "Default")
      (node (ref "R41") (pin "1") (pinfunction "1_1") (pintype "passive"))
      (node (ref "U2") (pin "P$6") (pinfunction "IPROPI_P$6") (pintype "bidirectional"))
    )
    (net (code "266") (name "Net-(U2-NFAULT)") (class "Default")
      (node (ref "J78") (pin "P$1") (pinfunction "P$1_P$1") (pintype "bidirectional"))
      (node (ref "J78") (pin "P$2") (pinfunction "P$2_P$2") (pintype "bidirectional"))
      (node (ref "R42") (pin "2") (pinfunction "2_2") (pintype "passive"))
      (node (ref "U2") (pin "P$4") (pinfunction "NFAULT_P$4") (pintype "bidirectional"))
    )
    (net (code "267") (name "Net-(U2-VCP)") (class "Default")
      (node (ref "C17") (pin "1") (pinfunction "1_1") (pintype "passive"))
      (node (ref "U2") (pin "P$12") (pinfunction "VCP_P$12") (pintype "bidirectional"))
    )
    (net (code "268") (name "Net-(U2-VREF)") (class "Default")
      (node (ref "TRIMPOT1") (pin "3") (pinfunction "3_3") (pintype "passive"))
      (node (ref "TRIMPOT1") (pin "4") (pinfunction "4_4") (pintype "passive"))
      (node (ref "U2") (pin "P$5") (pinfunction "VREF_P$5") (pintype "bidirectional"))
    )
    (net (code "269") (name "Net-(U3-P1_OSCI)") (class "Default")
      (node (ref "Q1") (pin "2") (pinfunction "2_2") (pintype "passive"))
      (node (ref "U3") (pin "1") (pinfunction "P1_OSCI_1") (pintype "bidirectional"))
    )
    (net (code "270") (name "Net-(U3-P2_OSC0)") (class "Default")
      (node (ref "Q1") (pin "1") (pinfunction "1_1") (pintype "passive"))
      (node (ref "U3") (pin "2") (pinfunction "P2_OSC0_2") (pintype "bidirectional"))
    )
    (net (code "271") (name "Net-(U3-P3_VBACK)") (class "Default")
      (node (ref "G1") (pin "+") (pinfunction "+_+") (pintype "passive"))
      (node (ref "U3") (pin "3") (pinfunction "P3_VBACK_3") (pintype "bidirectional"))
    )
    (net (code "272") (name "Net-(U3-P7_IRQ)") (class "Default")
      (node (ref "J1") (pin "P$1") (pinfunction "P$1_P$1") (pintype "bidirectional"))
      (node (ref "J1") (pin "P$2") (pinfunction "P$2_P$2") (pintype "bidirectional"))
      (node (ref "J1") (pin "P$3") (pinfunction "P$3_P$3") (pintype "bidirectional"))
      (node (ref "U3") (pin "7") (pinfunction "P7_IRQ_7") (pintype "bidirectional"))
    )
    (net (code "273") (name "Net-(U4-CPH)") (class "Default")
      (node (ref "C24") (pin "2") (pinfunction "2_2") (pintype "passive"))
      (node (ref "U4") (pin "P$13") (pinfunction "CPH_P$13") (pintype "bidirectional"))
    )
    (net (code "274") (name "Net-(U4-CPL)") (class "Default")
      (node (ref "C24") (pin "1") (pinfunction "1_1") (pintype "passive"))
      (node (ref "U4") (pin "P$14") (pinfunction "CPL_P$14") (pintype "bidirectional"))
    )
    (net (code "275") (name "Net-(U4-IPROPI)") (class "Default")
      (node (ref "R43") (pin "1") (pinfunction "1_1") (pintype "passive"))
      (node (ref "U4") (pin "P$6") (pinfunction "IPROPI_P$6") (pintype "bidirectional"))
    )
    (net (code "276") (name "Net-(U4-NFAULT)") (class "Default")
      (node (ref "J81") (pin "P$1") (pinfunction "P$1_P$1") (pintype "bidirectional"))
      (node (ref "J81") (pin "P$2") (pinfunction "P$2_P$2") (pintype "bidirectional"))
      (node (ref "R44") (pin "2") (pinfunction "2_2") (pintype "passive"))
      (node (ref "U4") (pin "P$4") (pinfunction "NFAULT_P$4") (pintype "bidirectional"))
    )
    (net (code "277") (name "Net-(U4-VCP)") (class "Default")
      (node (ref "C23") (pin "1") (pinfunction "1_1") (pintype "passive"))
      (node (ref "U4") (pin "P$12") (pinfunction "VCP_P$12") (pintype "bidirectional"))
    )
    (net (code "278") (name "Net-(U4-VREF)") (class "Default")
      (node (ref "TRIMPOT2") (pin "3") (pinfunction "3_3") (pintype "passive"))
      (node (ref "TRIMPOT2") (pin "4") (pinfunction "4_4") (pintype "passive"))
      (node (ref "U4") (pin "P$5") (pinfunction "VREF_P$5") (pintype "bidirectional"))
    )
    (net (code "279") (name "Net-(U5-MODE)") (class "Default")
      (node (ref "JP3") (pin "1") (pinfunction "1_1") (pintype "passive"))
      (node (ref "R5") (pin "1") (pinfunction "1_1") (pintype "passive"))
      (node (ref "U5") (pin "14") (pinfunction "MODE_14") (pintype "bidirectional"))
    )
    (net (code "280") (name "Net-(U5-PHASE)") (class "Default")
      (node (ref "J197") (pin "P$1") (pinfunction "P$1_P$1") (pintype "bidirectional"))
      (node (ref "J197") (pin "P$2") (pinfunction "P$2_P$2") (pintype "bidirectional"))
      (node (ref "U5") (pin "7") (pinfunction "PHASE_7") (pintype "bidirectional"))
    )
    (net (code "281") (name "Net-(U5-RC)") (class "Default")
      (node (ref "C2") (pin "1") (pinfunction "1_1") (pintype "passive"))
      (node (ref "R7") (pin "2") (pinfunction "2_2") (pintype "passive"))
      (node (ref "U5") (pin "3") (pinfunction "RC_3") (pintype "bidirectional"))
    )
    (net (code "282") (name "Net-(U5-~{BRAKE})") (class "Default")
      (node (ref "R6") (pin "1") (pinfunction "1_1") (pintype "passive"))
      (node (ref "U5") (pin "1") (pinfunction "~{BRAKE}_1") (pintype "bidirectional"))
    )
    (net (code "283") (name "Net-(U6-IN2)") (class "Default")
      (node (ref "SV10") (pin "2") (pinfunction "2_2") (pintype "passive"))
      (node (ref "U6") (pin "P$2") (pinfunction "IN2_P$2") (pintype "bidirectional"))
    )
    (net (code "284") (name "Net-(U6-IN3)") (class "Default")
      (node (ref "SV10") (pin "3") (pinfunction "3_3") (pintype "passive"))
      (node (ref "U6") (pin "P$3") (pinfunction "IN3_P$3") (pintype "bidirectional"))
    )
    (net (code "285") (name "Net-(U6-OUT1)") (class "Default")
      (node (ref "SV9") (pin "1") (pinfunction "1_1") (pintype "passive"))
      (node (ref "U6") (pin "P$7") (pinfunction "OUT1_P$7") (pintype "bidirectional"))
    )
    (net (code "286") (name "Net-(U6-OUT3)") (class "Default")
      (node (ref "SV9") (pin "3") (pinfunction "3_3") (pintype "passive"))
      (node (ref "U6") (pin "P$5") (pinfunction "OUT3_P$5") (pintype "bidirectional"))
    )
    (net (code "287") (name "Net-(U7-~{HOLD})") (class "Default")
      (node (ref "R25") (pin "1") (pinfunction "1_1") (pintype "passive"))
      (node (ref "U7") (pin "7") (pinfunction "~{HOLD}_7") (pintype "bidirectional"))
    )
    (net (code "288") (name "POWER") (class "Default")
      (node (ref "B2") (pin "P$1") (pinfunction "BAT+_P$1") (pintype "bidirectional"))
      (node (ref "C1") (pin "+") (pinfunction "+_+") (pintype "passive"))
      (node (ref "C12") (pin "+") (pinfunction "+_+") (pintype "passive"))
      (node (ref "C13") (pin "+") (pinfunction "+_+") (pintype "passive"))
      (node (ref "C15") (pin "+") (pinfunction "+_+") (pintype "passive"))
      (node (ref "C16") (pin "1") (pinfunction "1_1") (pintype "passive"))
      (node (ref "C17") (pin "2") (pinfunction "2_2") (pintype "passive"))
      (node (ref "C20") (pin "+") (pinfunction "+_+") (pintype "passive"))
      (node (ref "C22") (pin "1") (pinfunction "1_1") (pintype "passive"))
      (node (ref "C23") (pin "2") (pinfunction "2_2") (pintype "passive"))
      (node (ref "C25") (pin "+") (pinfunction "+_+") (pintype "passive"))
      (node (ref "C27") (pin "+") (pinfunction "+_+") (pintype "passive"))
      (node (ref "C28") (pin "+") (pinfunction "+_+") (pintype "passive"))
      (node (ref "DCDC3.3V") (pin "1") (pinfunction "1_1") (pintype "passive"))
      (node (ref "DCDC5V") (pin "1") (pinfunction "1_1") (pintype "passive"))
      (node (ref "J5") (pin "1") (pinfunction "1_1") (pintype "passive"))
      (node (ref "POWER") (pin "2") (pinfunction "2_2") (pintype "passive"))
      (node (ref "S141") (pin "P$1") (pinfunction "P$1_P$1") (pintype "bidirectional"))
      (node (ref "S141") (pin "P$2") (pinfunction "P$2_P$2") (pintype "bidirectional"))
      (node (ref "S141") (pin "P$3") (pinfunction "P$3_P$3") (pintype "bidirectional"))
      (node (ref "S141") (pin "P$4") (pinfunction "P$4_P$4") (pintype "bidirectional"))
      (node (ref "S141") (pin "P$5") (pinfunction "P$5_P$5") (pintype "bidirectional"))
      (node (ref "U1") (pin "16") (pinfunction "VBB_16") (pintype "bidirectional"))
      (node (ref "U1") (pin "9") (pinfunction "VBB_9") (pintype "bidirectional"))
      (node (ref "U2") (pin "P$11") (pinfunction "VM_P$11") (pintype "bidirectional"))
      (node (ref "U4") (pin "P$11") (pinfunction "VM_P$11") (pintype "bidirectional"))
      (node (ref "U5") (pin "16") (pinfunction "VBB_16") (pintype "bidirectional"))
      (node (ref "U5") (pin "9") (pinfunction "VBB_9") (pintype "bidirectional"))
    )
    (net (code "289") (name "RESET") (class "Default")
      (node (ref "J98") (pin "P$1") (pinfunction "P$1_P$1") (pintype "bidirectional"))
      (node (ref "J98") (pin "P$2") (pinfunction "P$2_P$2") (pintype "bidirectional"))
      (node (ref "J98") (pin "P$3") (pinfunction "P$3_P$3") (pintype "bidirectional"))
      (node (ref "L1") (pin "P$16") (pinfunction "RST_P$16") (pintype "bidirectional"))
    )
    (net (code "290") (name "RESET_2") (class "Default")
      (node (ref "J157") (pin "P$1") (pinfunction "P$1_P$1") (pintype "bidirectional"))
      (node (ref "J157") (pin "P$2") (pinfunction "P$2_P$2") (pintype "bidirectional"))
      (node (ref "J157") (pin "P$3") (pinfunction "P$3_P$3") (pintype "bidirectional"))
      (node (ref "L1") (pin "P$56") (pinfunction "RST_2_P$56") (pintype "bidirectional"))
    )
    (net (code "291") (name "SCL") (class "Default")
      (node (ref "J2") (pin "P$1") (pinfunction "P$1_P$1") (pintype "bidirectional"))
      (node (ref "J2") (pin "P$2") (pinfunction "P$2_P$2") (pintype "bidirectional"))
      (node (ref "J2") (pin "P$3") (pinfunction "P$3_P$3") (pintype "bidirectional"))
      (node (ref "U3") (pin "6") (pinfunction "P6_SCL_6") (pintype "bidirectional"))
    )
    (net (code "292") (name "SDA") (class "Default")
      (node (ref "J3") (pin "P$1") (pinfunction "P$1_P$1") (pintype "bidirectional"))
      (node (ref "J3") (pin "P$2") (pinfunction "P$2_P$2") (pintype "bidirectional"))
      (node (ref "J3") (pin "P$3") (pinfunction "P$3_P$3") (pintype "bidirectional"))
      (node (ref "U3") (pin "5") (pinfunction "P5_SDA_5") (pintype "bidirectional"))
    )
    (net (code "293") (name "VCC") (class "Default")
      (node (ref "C10") (pin "1") (pinfunction "1_1") (pintype "passive"))
      (node (ref "C3") (pin "1") (pinfunction "1_1") (pintype "passive"))
      (node (ref "C4") (pin "1") (pinfunction "1_1") (pintype "passive"))
      (node (ref "C6") (pin "1") (pinfunction "1_1") (pintype "passive"))
      (node (ref "C9") (pin "1") (pinfunction "1_1") (pintype "passive"))
      (node (ref "DCDC3.3V") (pin "3") (pinfunction "3_3") (pintype "passive"))
      (node (ref "ETH1") (pin "P$10") (pinfunction "3V3_1_P$10") (pintype "bidirectional"))
      (node (ref "ETH1") (pin "P$11") (pinfunction "3V3_2_P$11") (pintype "bidirectional"))
      (node (ref "IC1") (pin "14") (pinfunction "VCC_14") (pintype "power_in"))
      (node (ref "IC2") (pin "14") (pinfunction "VCC_14") (pintype "power_in"))
      (node (ref "IC3") (pin "14") (pinfunction "VCC_14") (pintype "power_in"))
      (node (ref "J10") (pin "P$1") (pinfunction "P$1_P$1") (pintype "bidirectional"))
      (node (ref "J10") (pin "P$2") (pinfunction "P$2_P$2") (pintype "bidirectional"))
      (node (ref "J10") (pin "P$3") (pinfunction "P$3_P$3") (pintype "bidirectional"))
      (node (ref "J123") (pin "P$1") (pinfunction "P$1_P$1") (pintype "bidirectional"))
      (node (ref "J123") (pin "P$2") (pinfunction "P$2_P$2") (pintype "bidirectional"))
      (node (ref "J123") (pin "P$3") (pinfunction "P$3_P$3") (pintype "bidirectional"))
      (node (ref "J177") (pin "P$1") (pinfunction "P$1_P$1") (pintype "bidirectional"))
      (node (ref "J177") (pin "P$2") (pinfunction "P$2_P$2") (pintype "bidirectional"))
      (node (ref "J177") (pin "P$3") (pinfunction "P$3_P$3") (pintype "bidirectional"))
      (node (ref "L1") (pin "P$1") (pinfunction "3.3V_1_P$1") (pintype "bidirectional"))
      (node (ref "L1") (pin "P$41") (pinfunction "3.3V_2_P$41") (pintype "bidirectional"))
      (node (ref "R10") (pin "1") (pinfunction "1_1") (pintype "passive"))
      (node (ref "R11") (pin "2") (pinfunction "2_2") (pintype "passive"))
      (node (ref "R12") (pin "2") (pinfunction "2_2") (pintype "passive"))
      (node (ref "R13") (pin "2") (pinfunction "2_2") (pintype "passive"))
      (node (ref "R14") (pin "2") (pinfunction "2_2") (pintype "passive"))
      (node (ref "R15") (pin "2") (pinfunction "2_2") (pintype "passive"))
      (node (ref "R16") (pin "2") (pinfunction "2_2") (pintype "passive"))
      (node (ref "R17") (pin "2") (pinfunction "2_2") (pintype "passive"))
      (node (ref "R18") (pin "2") (pinfunction "2_2") (pintype "passive"))
      (node (ref "R19") (pin "2") (pinfunction "2_2") (pintype "passive"))
      (node (ref "R20") (pin "2") (pinfunction "2_2") (pintype "passive"))
      (node (ref "R21") (pin "2") (pinfunction "2_2") (pintype "passive"))
      (node (ref "R22") (pin "2") (pinfunction "2_2") (pintype "passive"))
      (node (ref "R23") (pin "2") (pinfunction "2_2") (pintype "passive"))
      (node (ref "R24") (pin "2") (pinfunction "2_2") (pintype "passive"))
      (node (ref "R25") (pin "2") (pinfunction "2_2") (pintype "passive"))
      (node (ref "R27") (pin "2") (pinfunction "2_2") (pintype "passive"))
      (node (ref "R28") (pin "2") (pinfunction "2_2") (pintype "passive"))
      (node (ref "R29") (pin "2") (pinfunction "2_2") (pintype "passive"))
      (node (ref "R30") (pin "2") (pinfunction "2_2") (pintype "passive"))
      (node (ref "R31") (pin "2") (pinfunction "2_2") (pintype "passive"))
      (node (ref "R4") (pin "2") (pinfunction "2_2") (pintype "passive"))
      (node (ref "R42") (pin "1") (pinfunction "1_1") (pintype "passive"))
      (node (ref "R44") (pin "1") (pinfunction "1_1") (pintype "passive"))
      (node (ref "R5") (pin "2") (pinfunction "2_2") (pintype "passive"))
      (node (ref "R6") (pin "2") (pinfunction "2_2") (pintype "passive"))
      (node (ref "R8") (pin "2") (pinfunction "2_2") (pintype "passive"))
      (node (ref "R9") (pin "1") (pinfunction "1_1") (pintype "passive"))
      (node (ref "S50") (pin "P$1") (pinfunction "P$1_P$1") (pintype "bidirectional"))
      (node (ref "S50") (pin "P$10") (pinfunction "P$10_P$10") (pintype "bidirectional"))
      (node (ref "S50") (pin "P$2") (pinfunction "P$2_P$2") (pintype "bidirectional"))
      (node (ref "S50") (pin "P$3") (pinfunction "P$3_P$3") (pintype "bidirectional"))
      (node (ref "S50") (pin "P$4") (pinfunction "P$4_P$4") (pintype "bidirectional"))
      (node (ref "S50") (pin "P$5") (pinfunction "P$5_P$5") (pintype "bidirectional"))
      (node (ref "S50") (pin "P$6") (pinfunction "P$6_P$6") (pintype "bidirectional"))
      (node (ref "S50") (pin "P$7") (pinfunction "P$7_P$7") (pintype "bidirectional"))
      (node (ref "S50") (pin "P$8") (pinfunction "P$8_P$8") (pintype "bidirectional"))
      (node (ref "S50") (pin "P$9") (pinfunction "P$9_P$9") (pintype "bidirectional"))
      (node (ref "S53") (pin "P$1") (pinfunction "P$1_P$1") (pintype "bidirectional"))
      (node (ref "S53") (pin "P$10") (pinfunction "P$10_P$10") (pintype "bidirectional"))
      (node (ref "S53") (pin "P$2") (pinfunction "P$2_P$2") (pintype "bidirectional"))
      (node (ref "S53") (pin "P$3") (pinfunction "P$3_P$3") (pintype "bidirectional"))
      (node (ref "S53") (pin "P$4") (pinfunction "P$4_P$4") (pintype "bidirectional"))
      (node (ref "S53") (pin "P$5") (pinfunction "P$5_P$5") (pintype "bidirectional"))
      (node (ref "S53") (pin "P$6") (pinfunction "P$6_P$6") (pintype "bidirectional"))
      (node (ref "S53") (pin "P$7") (pinfunction "P$7_P$7") (pintype "bidirectional"))
      (node (ref "S53") (pin "P$8") (pinfunction "P$8_P$8") (pintype "bidirectional"))
      (node (ref "S53") (pin "P$9") (pinfunction "P$9_P$9") (pintype "bidirectional"))
      (node (ref "S58") (pin "P$1") (pinfunction "P$1_P$1") (pintype "bidirectional"))
      (node (ref "S58") (pin "P$10") (pinfunction "P$10_P$10") (pintype "bidirectional"))
      (node (ref "S58") (pin "P$2") (pinfunction "P$2_P$2") (pintype "bidirectional"))
      (node (ref "S58") (pin "P$3") (pinfunction "P$3_P$3") (pintype "bidirectional"))
      (node (ref "S58") (pin "P$4") (pinfunction "P$4_P$4") (pintype "bidirectional"))
      (node (ref "S58") (pin "P$5") (pinfunction "P$5_P$5") (pintype "bidirectional"))
      (node (ref "S58") (pin "P$6") (pinfunction "P$6_P$6") (pintype "bidirectional"))
      (node (ref "S58") (pin "P$7") (pinfunction "P$7_P$7") (pintype "bidirectional"))
      (node (ref "S58") (pin "P$8") (pinfunction "P$8_P$8") (pintype "bidirectional"))
      (node (ref "S58") (pin "P$9") (pinfunction "P$9_P$9") (pintype "bidirectional"))
      (node (ref "SV11") (pin "2") (pinfunction "2_2") (pintype "passive"))
      (node (ref "SV12") (pin "2") (pinfunction "2_2") (pintype "passive"))
      (node (ref "SV13") (pin "3") (pinfunction "3_3") (pintype "passive"))
      (node (ref "SV13") (pin "7") (pinfunction "7_7") (pintype "passive"))
      (node (ref "SV6") (pin "1") (pinfunction "1_1") (pintype "passive"))
      (node (ref "SV6") (pin "2") (pinfunction "2_2") (pintype "passive"))
      (node (ref "TRIMPOT1") (pin "1") (pinfunction "1_1") (pintype "passive"))
      (node (ref "TRIMPOT1") (pin "2") (pinfunction "2_2") (pintype "passive"))
      (node (ref "TRIMPOT2") (pin "1") (pinfunction "1_1") (pintype "passive"))
      (node (ref "TRIMPOT2") (pin "2") (pinfunction "2_2") (pintype "passive"))
      (node (ref "U$1") (pin "1") (pinfunction "P1_VCC_1") (pintype "bidirectional"))
      (node (ref "U1") (pin "2") (pinfunction "REF_2") (pintype "bidirectional"))
      (node (ref "U1") (pin "6") (pinfunction "VCC_6") (pintype "bidirectional"))
      (node (ref "U3") (pin "8") (pinfunction "P8_VCC_8") (pintype "bidirectional"))
      (node (ref "U5") (pin "2") (pinfunction "REF_2") (pintype "bidirectional"))
      (node (ref "U5") (pin "6") (pinfunction "VCC_6") (pintype "bidirectional"))
      (node (ref "U6") (pin "P$8") (pinfunction "V+_P$8") (pintype "bidirectional"))
      (node (ref "U7") (pin "8") (pinfunction "VCC_8") (pintype "bidirectional"))
    )
    (net (code "294") (name "unconnected-(ETH1-NC-PadP$9)") (class "Default")
      (node (ref "ETH1") (pin "P$9") (pinfunction "NC_P$9") (pintype "bidirectional"))
    )
    (net (code "295") (name "unconnected-(G1-+-Pad+@1)") (class "Default")
      (node (ref "G1") (pin "+@1") (pinfunction "+_+@1") (pintype "passive"))
    )
    (net (code "296") (name "unconnected-(J8-PadP$1)") (class "Default")
      (node (ref "J8") (pin "P$1") (pinfunction "P$1_P$1") (pintype "bidirectional"))
    )
    (net (code "297") (name "unconnected-(J8-PadP$2)") (class "Default")
      (node (ref "J8") (pin "P$2") (pinfunction "P$2_P$2") (pintype "bidirectional"))
    )
    (net (code "298") (name "unconnected-(SV12-Pad3)") (class "Default")
      (node (ref "SV12") (pin "3") (pinfunction "3_3") (pintype "passive"))
    )
    (net (code "299") (name "unconnected-(SV12-Pad5)") (class "Default")
      (node (ref "SV12") (pin "5") (pinfunction "5_5") (pintype "passive"))
    )
    (net (code "300") (name "unconnected-(SV13-Pad4)") (class "Default")
      (node (ref "SV13") (pin "4") (pinfunction "4_4") (pintype "passive"))
    )
    (net (code "301") (name "unconnected-(SV13-Pad6)") (class "Default")
      (node (ref "SV13") (pin "6") (pinfunction "6_6") (pintype "passive"))
    )
    (net (code "302") (name "unconnected-(U7-DNU-Pad3)") (class "Default")
      (node (ref "U7") (pin "3") (pinfunction "DNU_3") (pintype "bidirectional"))
    )
  )
)
